# Sheet1.net
KiCad netlist of a schematic drawn in Altium Designer
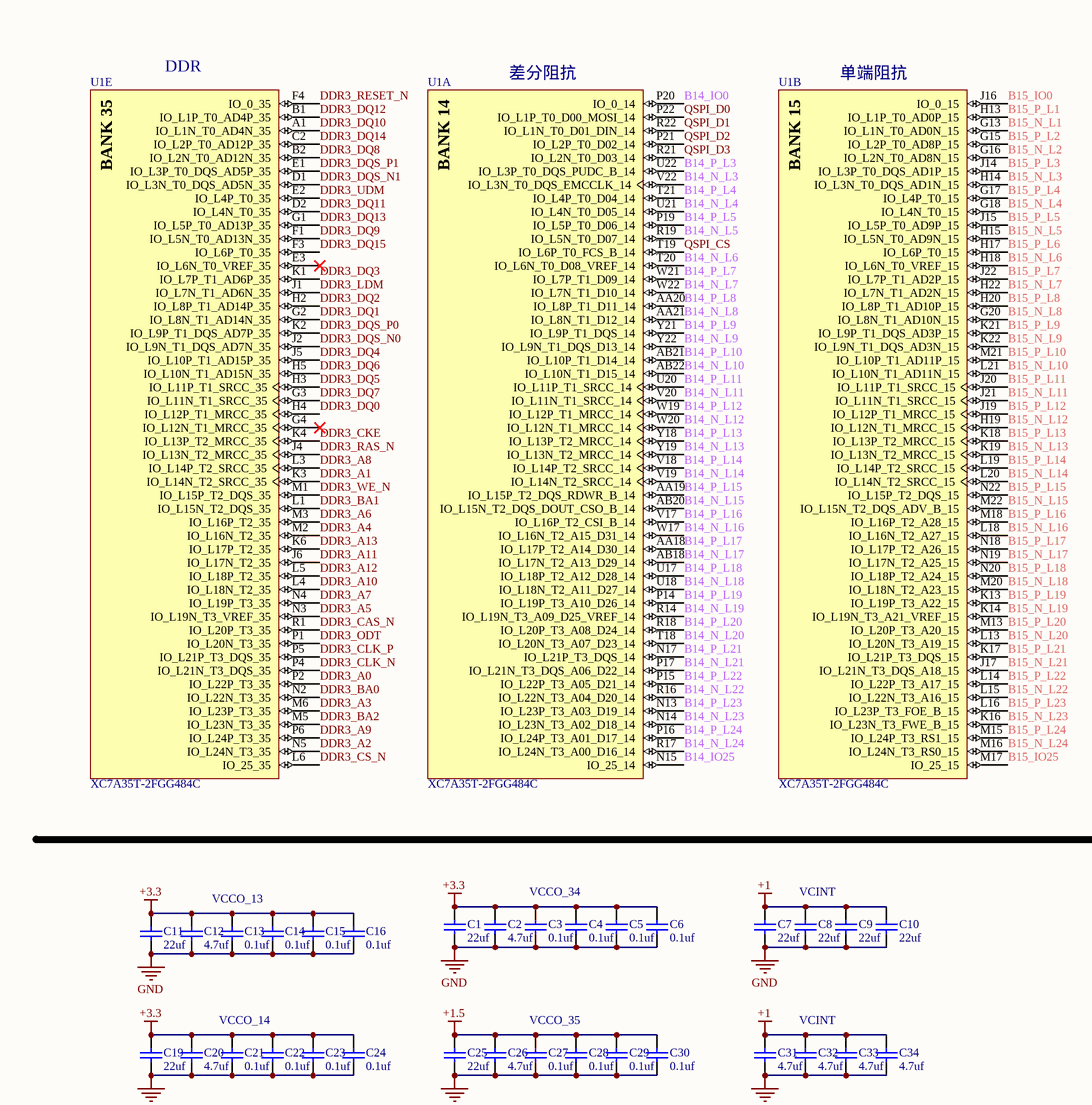
[diagram p0: Sheet1.SchDoc, top left]
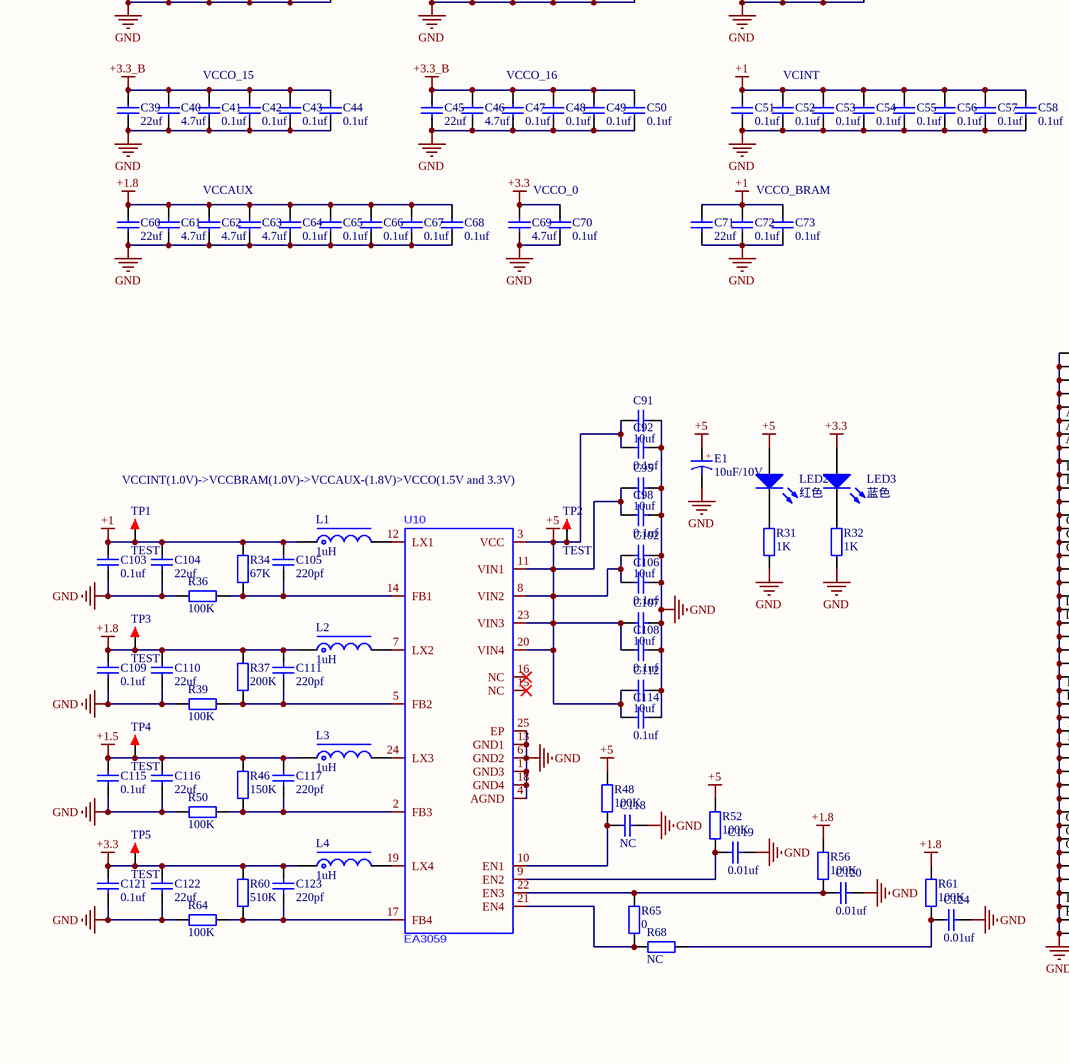
[diagram p1: Sheet1.SchDoc, bottom left]
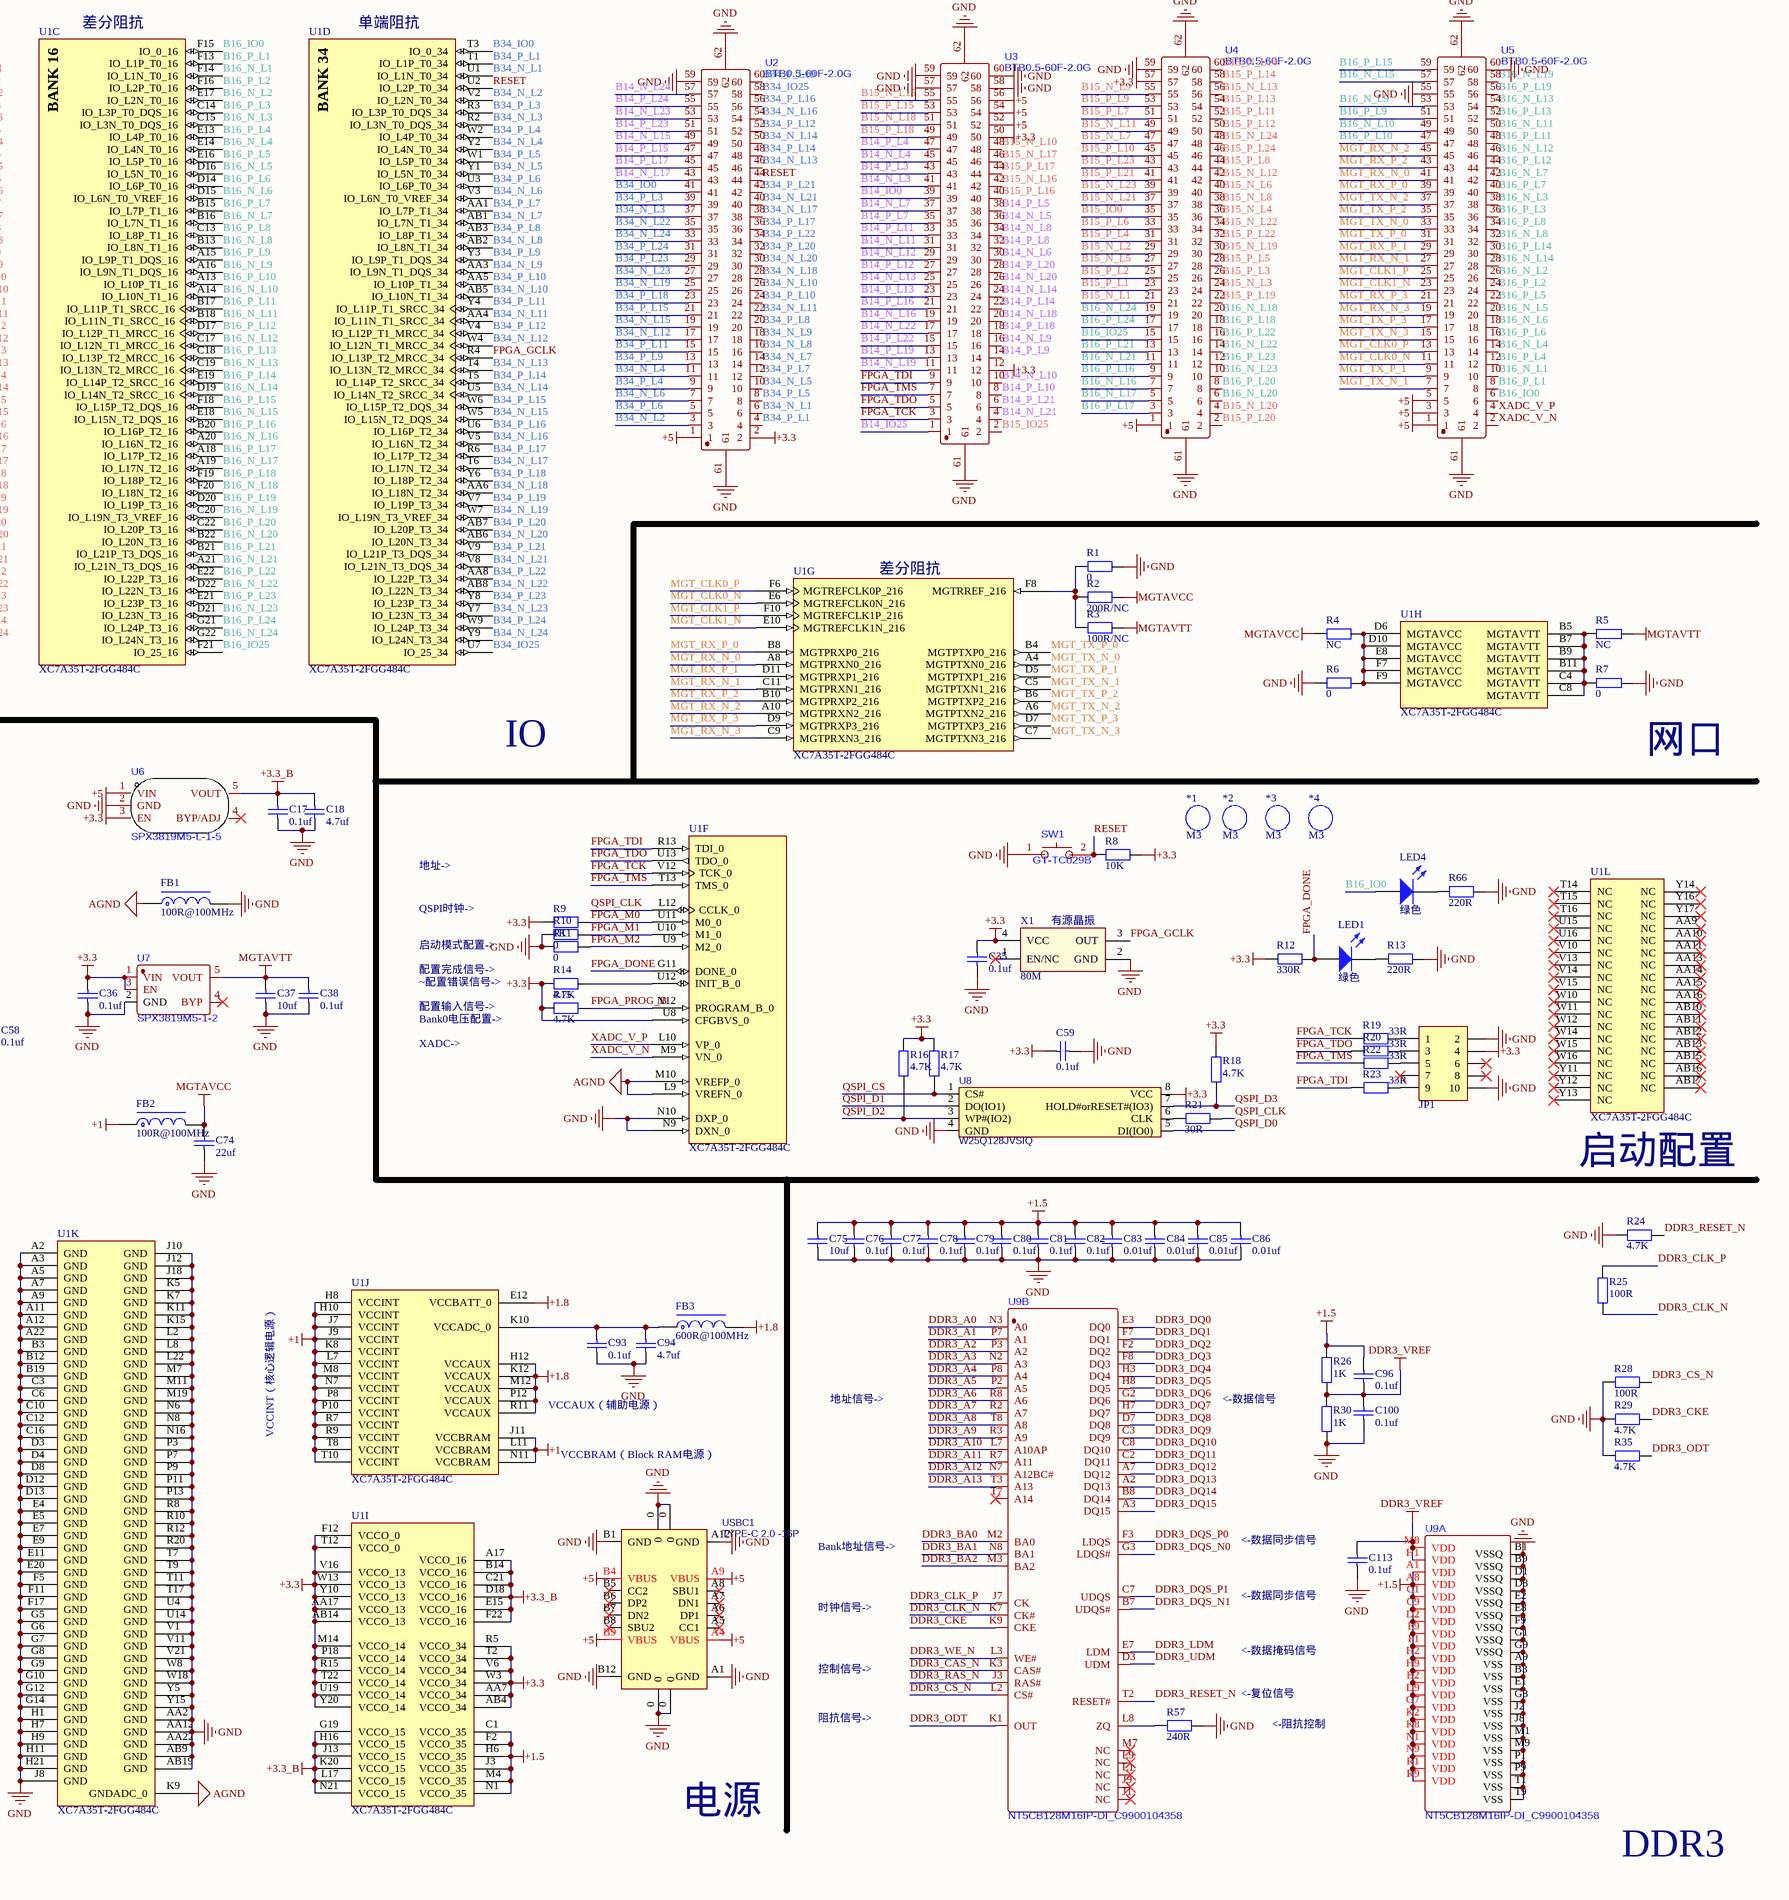
[diagram p2: Sheet1.SchDoc, bottom right]

(export (version "E")
  (design (tool "Eeschema 10.0.6"))
  (components
    (comp (ref "*1")
      (value "M3")
      (footprint "PCB1:M3 125X200")
      (description "铜柱孔")
      (libsource (lib "xc7a35t") (part "M3"))
    )
    (comp (ref "*2")
      (value "M3")
      (footprint "PCB1:M3 125X200")
      (description "铜柱孔")
      (libsource (lib "xc7a35t") (part "M3"))
    )
    (comp (ref "*3")
      (value "M3")
      (footprint "PCB1:M3 125X200")
      (description "铜柱孔")
      (libsource (lib "xc7a35t") (part "M3"))
    )
    (comp (ref "*4")
      (value "M3")
      (footprint "PCB1:M3 125X200")
      (description "铜柱孔")
      (libsource (lib "xc7a35t") (part "M3"))
    )
    (comp (ref "C1")
      (value "22uf")
      (footprint "PCB1:C0603_L")
      (description "贴片电容/MLCC电容")
      (libsource (lib "xc7a35t") (part "C"))
    )
    (comp (ref "C2")
      (value "4.7uf")
      (footprint "PCB1:C0402_L")
      (description "贴片电容/MLCC电容")
      (libsource (lib "xc7a35t") (part "C"))
    )
    (comp (ref "C3")
      (value "0.1uf")
      (footprint "PCB1:C0402_L")
      (description "贴片电容/MLCC电容")
      (libsource (lib "xc7a35t") (part "C"))
    )
    (comp (ref "C4")
      (value "0.1uf")
      (footprint "PCB1:C0402_L")
      (description "贴片电容/MLCC电容")
      (libsource (lib "xc7a35t") (part "C"))
    )
    (comp (ref "C5")
      (value "0.1uf")
      (footprint "PCB1:C0402_L")
      (description "贴片电容/MLCC电容")
      (libsource (lib "xc7a35t") (part "C"))
    )
    (comp (ref "C6")
      (value "0.1uf")
      (footprint "PCB1:C0402_L")
      (description "贴片电容/MLCC电容")
      (libsource (lib "xc7a35t") (part "C"))
    )
    (comp (ref "C7")
      (value "22uf")
      (footprint "PCB1:C0603_L")
      (description "贴片电容/MLCC电容")
      (libsource (lib "xc7a35t") (part "C"))
    )
    (comp (ref "C8")
      (value "22uf")
      (footprint "PCB1:C0603_L")
      (description "贴片电容/MLCC电容")
      (libsource (lib "xc7a35t") (part "C"))
    )
    (comp (ref "C9")
      (value "22uf")
      (footprint "PCB1:C0603_L")
      (description "贴片电容/MLCC电容")
      (libsource (lib "xc7a35t") (part "C"))
    )
    (comp (ref "C10")
      (value "22uf")
      (footprint "PCB1:C0603_L")
      (description "贴片电容/MLCC电容")
      (libsource (lib "xc7a35t") (part "C"))
    )
    (comp (ref "C11")
      (value "22uf")
      (footprint "PCB1:C0603_L")
      (description "贴片电容/MLCC电容")
      (libsource (lib "xc7a35t") (part "C"))
    )
    (comp (ref "C12")
      (value "4.7uf")
      (footprint "PCB1:C0402_L")
      (description "贴片电容/MLCC电容")
      (libsource (lib "xc7a35t") (part "C"))
    )
    (comp (ref "C13")
      (value "0.1uf")
      (footprint "PCB1:C0402_L")
      (description "贴片电容/MLCC电容")
      (libsource (lib "xc7a35t") (part "C"))
    )
    (comp (ref "C14")
      (value "0.1uf")
      (footprint "PCB1:C0402_L")
      (description "贴片电容/MLCC电容")
      (libsource (lib "xc7a35t") (part "C"))
    )
    (comp (ref "C15")
      (value "0.1uf")
      (footprint "PCB1:C0402_L")
      (description "贴片电容/MLCC电容")
      (libsource (lib "xc7a35t") (part "C"))
    )
    (comp (ref "C16")
      (value "0.1uf")
      (footprint "PCB1:C0402_L")
      (description "贴片电容/MLCC电容")
      (libsource (lib "xc7a35t") (part "C"))
    )
    (comp (ref "C17")
      (value "0.1uf")
      (footprint "PCB1:C0402_L")
      (description "贴片电容/MLCC电容")
      (libsource (lib "xc7a35t") (part "C"))
    )
    (comp (ref "C18")
      (value "4.7uf")
      (footprint "PCB1:C0402_L")
      (description "贴片电容/MLCC电容")
      (libsource (lib "xc7a35t") (part "C"))
    )
    (comp (ref "C19")
      (value "22uf")
      (footprint "PCB1:C0603_L")
      (description "贴片电容/MLCC电容")
      (libsource (lib "xc7a35t") (part "C"))
    )
    (comp (ref "C20")
      (value "4.7uf")
      (footprint "PCB1:C0402_L")
      (description "贴片电容/MLCC电容")
      (libsource (lib "xc7a35t") (part "C"))
    )
    (comp (ref "C21")
      (value "0.1uf")
      (footprint "PCB1:C0402_L")
      (description "贴片电容/MLCC电容")
      (libsource (lib "xc7a35t") (part "C"))
    )
    (comp (ref "C22")
      (value "0.1uf")
      (footprint "PCB1:C0402_L")
      (description "贴片电容/MLCC电容")
      (libsource (lib "xc7a35t") (part "C"))
    )
    (comp (ref "C23")
      (value "0.1uf")
      (footprint "PCB1:C0402_L")
      (description "贴片电容/MLCC电容")
      (libsource (lib "xc7a35t") (part "C"))
    )
    (comp (ref "C24")
      (value "0.1uf")
      (footprint "PCB1:C0402_L")
      (description "贴片电容/MLCC电容")
      (libsource (lib "xc7a35t") (part "C"))
    )
    (comp (ref "C25")
      (value "22uf")
      (footprint "PCB1:C0603_L")
      (description "贴片电容/MLCC电容")
      (libsource (lib "xc7a35t") (part "C"))
    )
    (comp (ref "C26")
      (value "4.7uf")
      (footprint "PCB1:C0402_L")
      (description "贴片电容/MLCC电容")
      (libsource (lib "xc7a35t") (part "C"))
    )
    (comp (ref "C27")
      (value "0.1uf")
      (footprint "PCB1:C0402_L")
      (description "贴片电容/MLCC电容")
      (libsource (lib "xc7a35t") (part "C"))
    )
    (comp (ref "C28")
      (value "0.1uf")
      (footprint "PCB1:C0402_L")
      (description "贴片电容/MLCC电容")
      (libsource (lib "xc7a35t") (part "C"))
    )
    (comp (ref "C29")
      (value "0.1uf")
      (footprint "PCB1:C0402_L")
      (description "贴片电容/MLCC电容")
      (libsource (lib "xc7a35t") (part "C"))
    )
    (comp (ref "C30")
      (value "0.1uf")
      (footprint "PCB1:C0402_L")
      (description "贴片电容/MLCC电容")
      (libsource (lib "xc7a35t") (part "C"))
    )
    (comp (ref "C31")
      (value "4.7uf")
      (footprint "PCB1:C0402_L")
      (description "贴片电容/MLCC电容")
      (libsource (lib "xc7a35t") (part "C"))
    )
    (comp (ref "C32")
      (value "4.7uf")
      (footprint "PCB1:C0402_L")
      (description "贴片电容/MLCC电容")
      (libsource (lib "xc7a35t") (part "C"))
    )
    (comp (ref "C33")
      (value "4.7uf")
      (footprint "PCB1:C0402_L")
      (description "贴片电容/MLCC电容")
      (libsource (lib "xc7a35t") (part "C"))
    )
    (comp (ref "C34")
      (value "4.7uf")
      (footprint "PCB1:C0402_L")
      (description "贴片电容/MLCC电容")
      (libsource (lib "xc7a35t") (part "C"))
    )
    (comp (ref "C35")
      (value "0.1uf")
      (footprint "PCB1:C0402_L")
      (description "贴片电容/MLCC电容")
      (libsource (lib "xc7a35t") (part "C"))
    )
    (comp (ref "C36")
      (value "0.1uf")
      (footprint "PCB1:C0402_L")
      (description "贴片电容/MLCC电容")
      (libsource (lib "xc7a35t") (part "C"))
    )
    (comp (ref "C37")
      (value "10uf")
      (footprint "PCB1:C0603_L")
      (description "贴片电容/MLCC电容")
      (libsource (lib "xc7a35t") (part "C"))
    )
    (comp (ref "C38")
      (value "0.1uf")
      (footprint "PCB1:C0402_L")
      (description "贴片电容/MLCC电容")
      (libsource (lib "xc7a35t") (part "C"))
    )
    (comp (ref "C39")
      (value "22uf")
      (footprint "PCB1:C0603_L")
      (description "贴片电容/MLCC电容")
      (libsource (lib "xc7a35t") (part "C"))
    )
    (comp (ref "C40")
      (value "4.7uf")
      (footprint "PCB1:C0402_L")
      (description "贴片电容/MLCC电容")
      (libsource (lib "xc7a35t") (part "C"))
    )
    (comp (ref "C41")
      (value "0.1uf")
      (footprint "PCB1:C0402_L")
      (description "贴片电容/MLCC电容")
      (libsource (lib "xc7a35t") (part "C"))
    )
    (comp (ref "C42")
      (value "0.1uf")
      (footprint "PCB1:C0402_L")
      (description "贴片电容/MLCC电容")
      (libsource (lib "xc7a35t") (part "C"))
    )
    (comp (ref "C43")
      (value "0.1uf")
      (footprint "PCB1:C0402_L")
      (description "贴片电容/MLCC电容")
      (libsource (lib "xc7a35t") (part "C"))
    )
    (comp (ref "C44")
      (value "0.1uf")
      (footprint "PCB1:C0402_L")
      (description "贴片电容/MLCC电容")
      (libsource (lib "xc7a35t") (part "C"))
    )
    (comp (ref "C45")
      (value "22uf")
      (footprint "PCB1:C0603_L")
      (description "贴片电容/MLCC电容")
      (libsource (lib "xc7a35t") (part "C"))
    )
    (comp (ref "C46")
      (value "4.7uf")
      (footprint "PCB1:C0402_L")
      (description "贴片电容/MLCC电容")
      (libsource (lib "xc7a35t") (part "C"))
    )
    (comp (ref "C47")
      (value "0.1uf")
      (footprint "PCB1:C0402_L")
      (description "贴片电容/MLCC电容")
      (libsource (lib "xc7a35t") (part "C"))
    )
    (comp (ref "C48")
      (value "0.1uf")
      (footprint "PCB1:C0402_L")
      (description "贴片电容/MLCC电容")
      (libsource (lib "xc7a35t") (part "C"))
    )
    (comp (ref "C49")
      (value "0.1uf")
      (footprint "PCB1:C0402_L")
      (description "贴片电容/MLCC电容")
      (libsource (lib "xc7a35t") (part "C"))
    )
    (comp (ref "C50")
      (value "0.1uf")
      (footprint "PCB1:C0402_L")
      (description "贴片电容/MLCC电容")
      (libsource (lib "xc7a35t") (part "C"))
    )
    (comp (ref "C51")
      (value "0.1uf")
      (footprint "PCB1:C0402_L")
      (description "贴片电容/MLCC电容")
      (libsource (lib "xc7a35t") (part "C"))
    )
    (comp (ref "C52")
      (value "0.1uf")
      (footprint "PCB1:C0402_L")
      (description "贴片电容/MLCC电容")
      (libsource (lib "xc7a35t") (part "C"))
    )
    (comp (ref "C53")
      (value "0.1uf")
      (footprint "PCB1:C0402_L")
      (description "贴片电容/MLCC电容")
      (libsource (lib "xc7a35t") (part "C"))
    )
    (comp (ref "C54")
      (value "0.1uf")
      (footprint "PCB1:C0402_L")
      (description "贴片电容/MLCC电容")
      (libsource (lib "xc7a35t") (part "C"))
    )
    (comp (ref "C55")
      (value "0.1uf")
      (footprint "PCB1:C0402_L")
      (description "贴片电容/MLCC电容")
      (libsource (lib "xc7a35t") (part "C"))
    )
    (comp (ref "C56")
      (value "0.1uf")
      (footprint "PCB1:C0402_L")
      (description "贴片电容/MLCC电容")
      (libsource (lib "xc7a35t") (part "C"))
    )
    (comp (ref "C57")
      (value "0.1uf")
      (footprint "PCB1:C0402_L")
      (description "贴片电容/MLCC电容")
      (libsource (lib "xc7a35t") (part "C"))
    )
    (comp (ref "C58")
      (value "0.1uf")
      (footprint "PCB1:C0402_L")
      (description "贴片电容/MLCC电容")
      (libsource (lib "xc7a35t") (part "C"))
    )
    (comp (ref "C59")
      (value "0.1uf")
      (footprint "PCB1:C0402_L")
      (description "贴片电容/MLCC电容")
      (libsource (lib "xc7a35t") (part "C"))
    )
    (comp (ref "C60")
      (value "22uf")
      (footprint "PCB1:C0603_L")
      (description "贴片电容/MLCC电容")
      (libsource (lib "xc7a35t") (part "C"))
    )
    (comp (ref "C61")
      (value "4.7uf")
      (footprint "PCB1:C0402_L")
      (description "贴片电容/MLCC电容")
      (libsource (lib "xc7a35t") (part "C"))
    )
    (comp (ref "C62")
      (value "4.7uf")
      (footprint "PCB1:C0402_L")
      (description "贴片电容/MLCC电容")
      (libsource (lib "xc7a35t") (part "C"))
    )
    (comp (ref "C63")
      (value "4.7uf")
      (footprint "PCB1:C0402_L")
      (description "贴片电容/MLCC电容")
      (libsource (lib "xc7a35t") (part "C"))
    )
    (comp (ref "C64")
      (value "0.1uf")
      (footprint "PCB1:C0402_L")
      (description "贴片电容/MLCC电容")
      (libsource (lib "xc7a35t") (part "C"))
    )
    (comp (ref "C65")
      (value "0.1uf")
      (footprint "PCB1:C0402_L")
      (description "贴片电容/MLCC电容")
      (libsource (lib "xc7a35t") (part "C"))
    )
    (comp (ref "C66")
      (value "0.1uf")
      (footprint "PCB1:C0402_L")
      (description "贴片电容/MLCC电容")
      (libsource (lib "xc7a35t") (part "C"))
    )
    (comp (ref "C67")
      (value "0.1uf")
      (footprint "PCB1:C0402_L")
      (description "贴片电容/MLCC电容")
      (libsource (lib "xc7a35t") (part "C"))
    )
    (comp (ref "C68")
      (value "0.1uf")
      (footprint "PCB1:C0402_L")
      (description "贴片电容/MLCC电容")
      (libsource (lib "xc7a35t") (part "C"))
    )
    (comp (ref "C69")
      (value "4.7uf")
      (footprint "PCB1:C0402_L")
      (description "贴片电容/MLCC电容")
      (libsource (lib "xc7a35t") (part "C"))
    )
    (comp (ref "C70")
      (value "0.1uf")
      (footprint "PCB1:C0402_L")
      (description "贴片电容/MLCC电容")
      (libsource (lib "xc7a35t") (part "C"))
    )
    (comp (ref "C71")
      (value "22uf")
      (footprint "PCB1:C0603_L")
      (description "贴片电容/MLCC电容")
      (libsource (lib "xc7a35t") (part "C"))
    )
    (comp (ref "C72")
      (value "0.1uf")
      (footprint "PCB1:C0402_L")
      (description "贴片电容/MLCC电容")
      (libsource (lib "xc7a35t") (part "C"))
    )
    (comp (ref "C73")
      (value "0.1uf")
      (footprint "PCB1:C0402_L")
      (description "贴片电容/MLCC电容")
      (libsource (lib "xc7a35t") (part "C"))
    )
    (comp (ref "C74")
      (value "22uf")
      (footprint "PCB1:C0603_L")
      (description "贴片电容/MLCC电容")
      (libsource (lib "xc7a35t") (part "C"))
    )
    (comp (ref "C75")
      (value "10uf")
      (footprint "PCB1:C0603_L")
      (description "贴片电容/MLCC电容")
      (libsource (lib "xc7a35t") (part "C"))
    )
    (comp (ref "C76")
      (value "0.1uf")
      (footprint "PCB1:C0402_L")
      (description "贴片电容/MLCC电容")
      (libsource (lib "xc7a35t") (part "C"))
    )
    (comp (ref "C77")
      (value "0.1uf")
      (footprint "PCB1:C0402_L")
      (description "贴片电容/MLCC电容")
      (libsource (lib "xc7a35t") (part "C"))
    )
    (comp (ref "C78")
      (value "0.1uf")
      (footprint "PCB1:C0402_L")
      (description "贴片电容/MLCC电容")
      (libsource (lib "xc7a35t") (part "C"))
    )
    (comp (ref "C79")
      (value "0.1uf")
      (footprint "PCB1:C0402_L")
      (description "贴片电容/MLCC电容")
      (libsource (lib "xc7a35t") (part "C"))
    )
    (comp (ref "C80")
      (value "0.1uf")
      (footprint "PCB1:C0402_L")
      (description "贴片电容/MLCC电容")
      (libsource (lib "xc7a35t") (part "C"))
    )
    (comp (ref "C81")
      (value "0.1uf")
      (footprint "PCB1:C0402_L")
      (description "贴片电容/MLCC电容")
      (libsource (lib "xc7a35t") (part "C"))
    )
    (comp (ref "C82")
      (value "0.1uf")
      (footprint "PCB1:C0402_L")
      (description "贴片电容/MLCC电容")
      (libsource (lib "xc7a35t") (part "C"))
    )
    (comp (ref "C83")
      (value "0.01uf")
      (footprint "PCB1:C0402_L")
      (description "贴片电容/MLCC电容")
      (libsource (lib "xc7a35t") (part "C"))
    )
    (comp (ref "C84")
      (value "0.01uf")
      (footprint "PCB1:C0402_L")
      (description "贴片电容/MLCC电容")
      (libsource (lib "xc7a35t") (part "C"))
    )
    (comp (ref "C85")
      (value "0.01uf")
      (footprint "PCB1:C0402_L")
      (description "贴片电容/MLCC电容")
      (libsource (lib "xc7a35t") (part "C"))
    )
    (comp (ref "C86")
      (value "0.01uf")
      (footprint "PCB1:C0402_L")
      (description "贴片电容/MLCC电容")
      (libsource (lib "xc7a35t") (part "C"))
    )
    (comp (ref "C91")
      (value "10uf")
      (footprint "PCB1:C0603_L")
      (description "贴片电容/MLCC电容")
      (libsource (lib "xc7a35t") (part "C"))
    )
    (comp (ref "C92")
      (value "0.1uf")
      (footprint "PCB1:C0402_L")
      (description "贴片电容/MLCC电容")
      (libsource (lib "xc7a35t") (part "C"))
    )
    (comp (ref "C93")
      (value "0.1uf")
      (footprint "PCB1:C0402_L")
      (description "贴片电容/MLCC电容")
      (libsource (lib "xc7a35t") (part "C"))
    )
    (comp (ref "C94")
      (value "4.7uf")
      (footprint "PCB1:C0402_L")
      (description "贴片电容/MLCC电容")
      (libsource (lib "xc7a35t") (part "C"))
    )
    (comp (ref "C95")
      (value "10uf")
      (footprint "PCB1:C0603_L")
      (description "贴片电容/MLCC电容")
      (libsource (lib "xc7a35t") (part "C"))
    )
    (comp (ref "C96")
      (value "0.1uf")
      (footprint "PCB1:C0402_L")
      (description "贴片电容/MLCC电容")
      (libsource (lib "xc7a35t") (part "C"))
    )
    (comp (ref "C98")
      (value "0.1uf")
      (footprint "PCB1:C0402_L")
      (description "贴片电容/MLCC电容")
      (libsource (lib "xc7a35t") (part "C"))
    )
    (comp (ref "C100")
      (value "0.1uf")
      (footprint "PCB1:C0402_L")
      (description "贴片电容/MLCC电容")
      (libsource (lib "xc7a35t") (part "C"))
    )
    (comp (ref "C102")
      (value "10uf")
      (footprint "PCB1:C0603_L")
      (description "贴片电容/MLCC电容")
      (libsource (lib "xc7a35t") (part "C"))
    )
    (comp (ref "C103")
      (value "0.1uf")
      (footprint "PCB1:C0402_L")
      (description "贴片电容/MLCC电容")
      (libsource (lib "xc7a35t") (part "C"))
    )
    (comp (ref "C104")
      (value "22uf")
      (footprint "PCB1:C0603_L")
      (description "贴片电容/MLCC电容")
      (libsource (lib "xc7a35t") (part "C"))
    )
    (comp (ref "C105")
      (value "220pf")
      (footprint "PCB1:C0402_L")
      (description "贴片电容/MLCC电容")
      (libsource (lib "xc7a35t") (part "C"))
    )
    (comp (ref "C106")
      (value "0.1uf")
      (footprint "PCB1:C0402_L")
      (description "贴片电容/MLCC电容")
      (libsource (lib "xc7a35t") (part "C"))
    )
    (comp (ref "C107")
      (value "10uf")
      (footprint "PCB1:C0603_L")
      (description "贴片电容/MLCC电容")
      (libsource (lib "xc7a35t") (part "C"))
    )
    (comp (ref "C108")
      (value "0.1uf")
      (footprint "PCB1:C0402_L")
      (description "贴片电容/MLCC电容")
      (libsource (lib "xc7a35t") (part "C"))
    )
    (comp (ref "C109")
      (value "0.1uf")
      (footprint "PCB1:C0402_L")
      (description "贴片电容/MLCC电容")
      (libsource (lib "xc7a35t") (part "C"))
    )
    (comp (ref "C110")
      (value "22uf")
      (footprint "PCB1:C0603_L")
      (description "贴片电容/MLCC电容")
      (libsource (lib "xc7a35t") (part "C"))
    )
    (comp (ref "C111")
      (value "220pf")
      (footprint "PCB1:C0402_L")
      (description "贴片电容/MLCC电容")
      (libsource (lib "xc7a35t") (part "C"))
    )
    (comp (ref "C112")
      (value "10uf")
      (footprint "PCB1:C0603_L")
      (description "贴片电容/MLCC电容")
      (libsource (lib "xc7a35t") (part "C"))
    )
    (comp (ref "C113")
      (value "0.1uf")
      (footprint "PCB1:C0402_L")
      (description "贴片电容/MLCC电容")
      (libsource (lib "xc7a35t") (part "C"))
    )
    (comp (ref "C114")
      (value "0.1uf")
      (footprint "PCB1:C0402_L")
      (description "贴片电容/MLCC电容")
      (libsource (lib "xc7a35t") (part "C"))
    )
    (comp (ref "C115")
      (value "0.1uf")
      (footprint "PCB1:C0402_L")
      (description "贴片电容/MLCC电容")
      (libsource (lib "xc7a35t") (part "C"))
    )
    (comp (ref "C116")
      (value "22uf")
      (footprint "PCB1:C0603_L")
      (description "贴片电容/MLCC电容")
      (libsource (lib "xc7a35t") (part "C"))
    )
    (comp (ref "C117")
      (value "220pf")
      (footprint "PCB1:C0402_L")
      (description "贴片电容/MLCC电容")
      (libsource (lib "xc7a35t") (part "C"))
    )
    (comp (ref "C118")
      (value "NC")
      (footprint "PCB1:C0402_L")
      (description "贴片电容/MLCC电容")
      (libsource (lib "xc7a35t") (part "C"))
    )
    (comp (ref "C119")
      (value "0.01uf")
      (footprint "PCB1:C0402_L")
      (description "贴片电容/MLCC电容")
      (libsource (lib "xc7a35t") (part "C"))
    )
    (comp (ref "C120")
      (value "0.01uf")
      (footprint "PCB1:C0402_L")
      (description "贴片电容/MLCC电容")
      (libsource (lib "xc7a35t") (part "C"))
    )
    (comp (ref "C121")
      (value "0.1uf")
      (footprint "PCB1:C0402_L")
      (description "贴片电容/MLCC电容")
      (libsource (lib "xc7a35t") (part "C"))
    )
    (comp (ref "C122")
      (value "22uf")
      (footprint "PCB1:C0603_L")
      (description "贴片电容/MLCC电容")
      (libsource (lib "xc7a35t") (part "C"))
    )
    (comp (ref "C123")
      (value "220pf")
      (footprint "PCB1:C0402_L")
      (description "贴片电容/MLCC电容")
      (libsource (lib "xc7a35t") (part "C"))
    )
    (comp (ref "C124")
      (value "0.01uf")
      (footprint "PCB1:C0402_L")
      (description "贴片电容/MLCC电容")
      (libsource (lib "xc7a35t") (part "C"))
    )
    (comp (ref "E1")
      (value "10uF/10V")
      (footprint "PCB1:CE D(6.3*7.7)")
      (description "贴片电解电容")
      (libsource (lib "xc7a35t") (part "CE_SMD"))
    )
    (comp (ref "FB1")
      (value "100R@100MHz")
      (footprint "PCB1:FB0603")
      (description "贴片磁珠")
      (libsource (lib "xc7a35t") (part "FB"))
    )
    (comp (ref "FB2")
      (value "100R@100MHz")
      (footprint "PCB1:FB0603")
      (description "贴片磁珠")
      (libsource (lib "xc7a35t") (part "FB"))
    )
    (comp (ref "FB3")
      (value "600R@100MHz")
      (footprint "PCB1:FB0603")
      (description "贴片磁珠")
      (libsource (lib "xc7a35t") (part "FB"))
    )
    (comp (ref "JP1")
      (value "Header 5X2")
      (footprint "PCB1:PHD2.0-LI-2x5P")
      (description "5*2P接插件")
      (libsource (lib "xc7a35t") (part "Header 5X2"))
    )
    (comp (ref "L1")
      (value "1uH")
      (footprint "PCB1:CD43")
      (description "CD系列贴片线绕功率电感")
      (libsource (lib "xc7a35t") (part "L-SMD"))
    )
    (comp (ref "L2")
      (value "1uH")
      (footprint "PCB1:CD43")
      (description "CD系列贴片线绕功率电感")
      (libsource (lib "xc7a35t") (part "L-SMD"))
    )
    (comp (ref "L3")
      (value "1uH")
      (footprint "PCB1:CD43")
      (description "CD系列贴片线绕功率电感")
      (libsource (lib "xc7a35t") (part "L-SMD"))
    )
    (comp (ref "L4")
      (value "1uH")
      (footprint "PCB1:CD43")
      (description "CD系列贴片线绕功率电感")
      (libsource (lib "xc7a35t") (part "L-SMD"))
    )
    (comp (ref "LED1")
      (value "绿色")
      (footprint "PCB1:LED0805_G")
      (description "贴片LED")
      (libsource (lib "xc7a35t") (part "LED"))
    )
    (comp (ref "LED2")
      (value "红色")
      (footprint "PCB1:LED0805_G")
      (description "贴片LED")
      (libsource (lib "xc7a35t") (part "LED"))
    )
    (comp (ref "LED3")
      (value "蓝色")
      (footprint "PCB1:LED0805_G")
      (description "贴片LED")
      (libsource (lib "xc7a35t") (part "LED"))
    )
    (comp (ref "LED4")
      (value "绿色")
      (footprint "PCB1:LED0805_G")
      (description "贴片LED")
      (libsource (lib "xc7a35t") (part "LED"))
    )
    (comp (ref "R1")
      (value "0")
      (footprint "PCB1:R0402_L")
      (description "贴片电阻")
      (libsource (lib "xc7a35t") (part "R"))
    )
    (comp (ref "R2")
      (value "200R/NC")
      (footprint "PCB1:R0402_L")
      (description "贴片电阻")
      (libsource (lib "xc7a35t") (part "R"))
    )
    (comp (ref "R3")
      (value "100R/NC")
      (footprint "PCB1:R0402_L")
      (description "贴片电阻")
      (libsource (lib "xc7a35t") (part "R"))
    )
    (comp (ref "R4")
      (value "NC")
      (footprint "PCB1:R0603_L")
      (description "贴片电阻")
      (libsource (lib "xc7a35t") (part "R"))
    )
    (comp (ref "R5")
      (value "NC")
      (footprint "PCB1:R0603_L")
      (description "贴片电阻")
      (libsource (lib "xc7a35t") (part "R"))
    )
    (comp (ref "R6")
      (value "0")
      (footprint "PCB1:R0603_L")
      (description "贴片电阻")
      (libsource (lib "xc7a35t") (part "R"))
    )
    (comp (ref "R7")
      (value "0")
      (footprint "PCB1:R0603_L")
      (description "贴片电阻")
      (libsource (lib "xc7a35t") (part "R"))
    )
    (comp (ref "R8")
      (value "10K")
      (footprint "PCB1:R0402_L")
      (description "贴片电阻")
      (libsource (lib "xc7a35t") (part "R"))
    )
    (comp (ref "R9")
      (value "1K")
      (footprint "PCB1:R0402_L")
      (description "贴片电阻")
      (libsource (lib "xc7a35t") (part "R"))
    )
    (comp (ref "R10")
      (value "0")
      (footprint "PCB1:R0402_L")
      (description "贴片电阻")
      (libsource (lib "xc7a35t") (part "R"))
    )
    (comp (ref "R11")
      (value "0")
      (footprint "PCB1:R0402_L")
      (description "贴片电阻")
      (libsource (lib "xc7a35t") (part "R"))
    )
    (comp (ref "R12")
      (value "330R")
      (footprint "PCB1:R0402_L")
      (description "贴片电阻")
      (libsource (lib "xc7a35t") (part "R"))
    )
    (comp (ref "R13")
      (value "220R")
      (footprint "PCB1:R0402_L")
      (description "贴片电阻")
      (libsource (lib "xc7a35t") (part "R"))
    )
    (comp (ref "R14")
      (value "4.7K")
      (footprint "PCB1:R0402_L")
      (description "贴片电阻")
      (libsource (lib "xc7a35t") (part "R"))
    )
    (comp (ref "R15")
      (value "4.7K")
      (footprint "PCB1:R0402_L")
      (description "贴片电阻")
      (libsource (lib "xc7a35t") (part "R"))
    )
    (comp (ref "R16")
      (value "4.7K")
      (footprint "PCB1:R0402_L")
      (description "贴片电阻")
      (libsource (lib "xc7a35t") (part "R"))
    )
    (comp (ref "R17")
      (value "4.7K")
      (footprint "PCB1:R0402_L")
      (description "贴片电阻")
      (libsource (lib "xc7a35t") (part "R"))
    )
    (comp (ref "R18")
      (value "4.7K")
      (footprint "PCB1:R0402_L")
      (description "贴片电阻")
      (libsource (lib "xc7a35t") (part "R"))
    )
    (comp (ref "R19")
      (value "33R")
      (footprint "PCB1:R0402_L")
      (description "贴片电阻")
      (libsource (lib "xc7a35t") (part "R"))
    )
    (comp (ref "R20")
      (value "33R")
      (footprint "PCB1:R0402_L")
      (description "贴片电阻")
      (libsource (lib "xc7a35t") (part "R"))
    )
    (comp (ref "R21")
      (value "30R")
      (footprint "PCB1:R0402_L")
      (description "贴片电阻")
      (libsource (lib "xc7a35t") (part "R"))
    )
    (comp (ref "R22")
      (value "33R")
      (footprint "PCB1:R0402_L")
      (description "贴片电阻")
      (libsource (lib "xc7a35t") (part "R"))
    )
    (comp (ref "R23")
      (value "33R")
      (footprint "PCB1:R0402_L")
      (description "贴片电阻")
      (libsource (lib "xc7a35t") (part "R"))
    )
    (comp (ref "R24")
      (value "4.7K")
      (footprint "PCB1:R0402_L")
      (description "贴片电阻")
      (libsource (lib "xc7a35t") (part "R"))
    )
    (comp (ref "R25")
      (value "100R")
      (footprint "PCB1:R0402_L")
      (description "贴片电阻")
      (libsource (lib "xc7a35t") (part "R"))
    )
    (comp (ref "R26")
      (value "1K")
      (footprint "PCB1:R0402_L")
      (description "贴片电阻")
      (libsource (lib "xc7a35t") (part "R"))
    )
    (comp (ref "R28")
      (value "100R")
      (footprint "PCB1:R0402_L")
      (description "贴片电阻")
      (libsource (lib "xc7a35t") (part "R"))
    )
    (comp (ref "R29")
      (value "4.7K")
      (footprint "PCB1:R0402_L")
      (description "贴片电阻")
      (libsource (lib "xc7a35t") (part "R"))
    )
    (comp (ref "R30")
      (value "1K")
      (footprint "PCB1:R0402_L")
      (description "贴片电阻")
      (libsource (lib "xc7a35t") (part "R"))
    )
    (comp (ref "R31")
      (value "1K")
      (footprint "PCB1:R0402_L")
      (description "贴片电阻")
      (libsource (lib "xc7a35t") (part "R"))
    )
    (comp (ref "R32")
      (value "1K")
      (footprint "PCB1:R0402_L")
      (description "贴片电阻")
      (libsource (lib "xc7a35t") (part "R"))
    )
    (comp (ref "R34")
      (value "67K")
      (footprint "PCB1:R0402_L")
      (description "贴片电阻")
      (libsource (lib "xc7a35t") (part "R"))
    )
    (comp (ref "R35")
      (value "4.7K")
      (footprint "PCB1:R0402_L")
      (description "贴片电阻")
      (libsource (lib "xc7a35t") (part "R"))
    )
    (comp (ref "R36")
      (value "100K")
      (footprint "PCB1:R0402_L")
      (description "贴片电阻")
      (libsource (lib "xc7a35t") (part "R"))
    )
    (comp (ref "R37")
      (value "200K")
      (footprint "PCB1:R0402_L")
      (description "贴片电阻")
      (libsource (lib "xc7a35t") (part "R"))
    )
    (comp (ref "R39")
      (value "100K")
      (footprint "PCB1:R0402_L")
      (description "贴片电阻")
      (libsource (lib "xc7a35t") (part "R"))
    )
    (comp (ref "R46")
      (value "150K")
      (footprint "PCB1:R0402_L")
      (description "贴片电阻")
      (libsource (lib "xc7a35t") (part "R"))
    )
    (comp (ref "R48")
      (value "100K")
      (footprint "PCB1:R0402_L")
      (description "贴片电阻")
      (libsource (lib "xc7a35t") (part "R"))
    )
    (comp (ref "R50")
      (value "100K")
      (footprint "PCB1:R0402_L")
      (description "贴片电阻")
      (libsource (lib "xc7a35t") (part "R"))
    )
    (comp (ref "R52")
      (value "100K")
      (footprint "PCB1:R0402_L")
      (description "贴片电阻")
      (libsource (lib "xc7a35t") (part "R"))
    )
    (comp (ref "R56")
      (value "100K")
      (footprint "PCB1:R0402_L")
      (description "贴片电阻")
      (libsource (lib "xc7a35t") (part "R"))
    )
    (comp (ref "R57")
      (value "240R")
      (footprint "PCB1:R0402_L")
      (description "贴片电阻")
      (libsource (lib "xc7a35t") (part "R"))
    )
    (comp (ref "R60")
      (value "510K")
      (footprint "PCB1:R0402_L")
      (description "贴片电阻")
      (libsource (lib "xc7a35t") (part "R"))
    )
    (comp (ref "R61")
      (value "100K")
      (footprint "PCB1:R0402_L")
      (description "贴片电阻")
      (libsource (lib "xc7a35t") (part "R"))
    )
    (comp (ref "R64")
      (value "100K")
      (footprint "PCB1:R0402_L")
      (description "贴片电阻")
      (libsource (lib "xc7a35t") (part "R"))
    )
    (comp (ref "R65")
      (value "0")
      (footprint "PCB1:R0402_L")
      (description "贴片电阻")
      (libsource (lib "xc7a35t") (part "R"))
    )
    (comp (ref "R66")
      (value "220R")
      (footprint "PCB1:R0402_L")
      (description "贴片电阻")
      (libsource (lib "xc7a35t") (part "R"))
    )
    (comp (ref "R68")
      (value "NC")
      (footprint "PCB1:R0402_L")
      (description "贴片电阻")
      (libsource (lib "xc7a35t") (part "R"))
    )
    (comp (ref "SW1")
      (value "GT-TC029B")
      (footprint "PCB1:SW-SMD_L3.9-W2.9-P4.15-LS5.0")
      (libsource (lib "xc7a35t") (part "GT-TC029B-H020-L1N"))
    )
    (comp (ref "TP1")
      (value "TEST")
      (footprint "PCB1:TEST 1.6")
      (description "测试点")
      (libsource (lib "xc7a35t") (part "TEST"))
    )
    (comp (ref "TP2")
      (value "TEST")
      (footprint "PCB1:TEST 1.6")
      (description "测试点")
      (libsource (lib "xc7a35t") (part "TEST"))
    )
    (comp (ref "TP3")
      (value "TEST")
      (footprint "PCB1:TEST 1.6")
      (description "测试点")
      (libsource (lib "xc7a35t") (part "TEST"))
    )
    (comp (ref "TP4")
      (value "TEST")
      (footprint "PCB1:TEST 1.6")
      (description "测试点")
      (libsource (lib "xc7a35t") (part "TEST"))
    )
    (comp (ref "TP5")
      (value "TEST")
      (footprint "PCB1:TEST 1.6")
      (description "测试点")
      (libsource (lib "xc7a35t") (part "TEST"))
    )
    (comp (ref "U1")
      (value "XC7A35T-2FGG484C")
      (footprint "PCB1:FGG484")
      (description "Artix-7 FPGA, 250 User I/Os, 4 GTP, 484-Ball BGA, Speed Grade 2, Commercial Grade, Pb-Free")
      (libsource (lib "xc7a35t") (part "XC7A35T-2FGG484C"))
    )
    (comp (ref "U2")
      (value "BTB0.5-60F-2.0G")
      (footprint "PCB1:CONN-SMD_60P-P0.50_BTB0.5-60F-2.0G")
      (libsource (lib "xc7a35t") (part "BTB0.5-60F-2.0G"))
    )
    (comp (ref "U3")
      (value "BTB0.5-60F-2.0G")
      (footprint "PCB1:CONN-SMD_60P-P0.50_BTB0.5-60F-2.0G")
      (libsource (lib "xc7a35t") (part "BTB0.5-60F-2.0G"))
    )
    (comp (ref "U4")
      (value "BTB0.5-60F-2.0G")
      (footprint "PCB1:CONN-SMD_60P-P0.50_BTB0.5-60F-2.0G")
      (libsource (lib "xc7a35t") (part "BTB0.5-60F-2.0G"))
    )
    (comp (ref "U5")
      (value "BTB0.5-60F-2.0G")
      (footprint "PCB1:CONN-SMD_60P-P0.50_BTB0.5-60F-2.0G")
      (libsource (lib "xc7a35t") (part "BTB0.5-60F-2.0G"))
    )
    (comp (ref "U6")
      (value "SPX3819M5-L-1-5")
      (footprint "PCB1:SPX3819M5-L-1-5")
      (libsource (lib "xc7a35t") (part "SPX3819M5-L-1-5"))
    )
    (comp (ref "U7")
      (value "SPX3819M5-1-2")
      (footprint "PCB1:SOT-23-5_L2.9-W1.6-P0.95-LS2.8-BR")
      (libsource (lib "xc7a35t") (part "SPX3819M5-1-2"))
    )
    (comp (ref "U8")
      (value "W25Q128JVSIQ")
      (footprint "PCB1:SOIC-8W")
      (description "SPI FLASH")
      (libsource (lib "xc7a35t") (part "W25Q128"))
    )
    (comp (ref "U9")
      (value "NT5CB128M16IP-DI_C9900104358")
      (footprint "PCB1:TFBGA-96_L13.0-W8.0-R16-C6-P0.80-TL")
      (libsource (lib "xc7a35t") (part "NT5CB128M16IP-DI_C9900104358"))
    )
    (comp (ref "U10")
      (value "EA3059")
      (footprint "PCB1:QFN24 4X4_M")
      (libsource (lib "xc7a35t") (part "EA3059"))
    )
    (comp (ref "USBC1")
      (value "TYPE-C 2.0 -16P")
      (footprint "PCB1:USB-C-SMD_16P")
      (description "USB2.0_Type-C_16Pin母座")
      (libsource (lib "xc7a35t") (part "USB2.0_Type-C_16Pin"))
    )
    (comp (ref "X1")
      (value "80M")
      (footprint "PCB1:OSC-3225-4P")
      (description "4脚有源晶振(振荡器)")
      (libsource (lib "xc7a35t") (part "XTAL-ACT-4P"))
    )
  )
  (nets
    (net (code "1") (name "+1") (class "Default")
      (node (ref "C10") (pin "1") (pinfunction "1_1") (pintype "passive"))
      (node (ref "C103") (pin "1") (pinfunction "1_1") (pintype "passive"))
      (node (ref "C104") (pin "1") (pinfunction "1_1") (pintype "passive"))
      (node (ref "C105") (pin "1") (pinfunction "1_1") (pintype "passive"))
      (node (ref "C31") (pin "1") (pinfunction "1_1") (pintype "passive"))
      (node (ref "C32") (pin "1") (pinfunction "1_1") (pintype "passive"))
      (node (ref "C33") (pin "1") (pinfunction "1_1") (pintype "passive"))
      (node (ref "C34") (pin "1") (pinfunction "1_1") (pintype "passive"))
      (node (ref "C51") (pin "1") (pinfunction "1_1") (pintype "passive"))
      (node (ref "C52") (pin "1") (pinfunction "1_1") (pintype "passive"))
      (node (ref "C53") (pin "1") (pinfunction "1_1") (pintype "passive"))
      (node (ref "C54") (pin "1") (pinfunction "1_1") (pintype "passive"))
      (node (ref "C55") (pin "1") (pinfunction "1_1") (pintype "passive"))
      (node (ref "C56") (pin "1") (pinfunction "1_1") (pintype "passive"))
      (node (ref "C57") (pin "1") (pinfunction "1_1") (pintype "passive"))
      (node (ref "C58") (pin "1") (pinfunction "1_1") (pintype "passive"))
      (node (ref "C7") (pin "1") (pinfunction "1_1") (pintype "passive"))
      (node (ref "C71") (pin "1") (pinfunction "1_1") (pintype "passive"))
      (node (ref "C72") (pin "1") (pinfunction "1_1") (pintype "passive"))
      (node (ref "C73") (pin "1") (pinfunction "1_1") (pintype "passive"))
      (node (ref "C8") (pin "1") (pinfunction "1_1") (pintype "passive"))
      (node (ref "C9") (pin "1") (pinfunction "1_1") (pintype "passive"))
      (node (ref "FB2") (pin "1") (pinfunction "1_1") (pintype "passive"))
      (node (ref "L1") (pin "1") (pinfunction "1_1") (pintype "passive"))
      (node (ref "R34") (pin "2") (pinfunction "2_2") (pintype "passive"))
      (node (ref "TP1") (pin "1") (pinfunction "1_1") (pintype "passive"))
      (node (ref "U1") (pin "H10") (pinfunction "VCCINT_H10") (pintype "power_in"))
      (node (ref "U1") (pin "H8") (pinfunction "VCCINT_H8") (pintype "power_in"))
      (node (ref "U1") (pin "J11") (pinfunction "VCCBRAM_J11") (pintype "power_in"))
      (node (ref "U1") (pin "J7") (pinfunction "VCCINT_J7") (pintype "power_in"))
      (node (ref "U1") (pin "J9") (pinfunction "VCCINT_J9") (pintype "power_in"))
      (node (ref "U1") (pin "K8") (pinfunction "VCCINT_K8") (pintype "power_in"))
      (node (ref "U1") (pin "L11") (pinfunction "VCCBRAM_L11") (pintype "power_in"))
      (node (ref "U1") (pin "L7") (pinfunction "VCCINT_L7") (pintype "power_in"))
      (node (ref "U1") (pin "M8") (pinfunction "VCCINT_M8") (pintype "power_in"))
      (node (ref "U1") (pin "N11") (pinfunction "VCCBRAM_N11") (pintype "power_in"))
      (node (ref "U1") (pin "N7") (pinfunction "VCCINT_N7") (pintype "power_in"))
      (node (ref "U1") (pin "P10") (pinfunction "VCCINT_P10") (pintype "power_in"))
      (node (ref "U1") (pin "P8") (pinfunction "VCCINT_P8") (pintype "power_in"))
      (node (ref "U1") (pin "R7") (pinfunction "VCCINT_R7") (pintype "power_in"))
      (node (ref "U1") (pin "R9") (pinfunction "VCCINT_R9") (pintype "power_in"))
      (node (ref "U1") (pin "T10") (pinfunction "VCCINT_T10") (pintype "power_in"))
      (node (ref "U1") (pin "T8") (pinfunction "VCCINT_T8") (pintype "power_in"))
    )
    (net (code "2") (name "+1.5") (class "Default")
      (node (ref "C115") (pin "1") (pinfunction "1_1") (pintype "passive"))
      (node (ref "C116") (pin "1") (pinfunction "1_1") (pintype "passive"))
      (node (ref "C117") (pin "1") (pinfunction "1_1") (pintype "passive"))
      (node (ref "C25") (pin "1") (pinfunction "1_1") (pintype "passive"))
      (node (ref "C26") (pin "1") (pinfunction "1_1") (pintype "passive"))
      (node (ref "C27") (pin "1") (pinfunction "1_1") (pintype "passive"))
      (node (ref "C28") (pin "1") (pinfunction "1_1") (pintype "passive"))
      (node (ref "C29") (pin "1") (pinfunction "1_1") (pintype "passive"))
      (node (ref "C30") (pin "1") (pinfunction "1_1") (pintype "passive"))
      (node (ref "C75") (pin "1") (pinfunction "1_1") (pintype "passive"))
      (node (ref "C76") (pin "2") (pinfunction "2_2") (pintype "passive"))
      (node (ref "C77") (pin "2") (pinfunction "2_2") (pintype "passive"))
      (node (ref "C78") (pin "2") (pinfunction "2_2") (pintype "passive"))
      (node (ref "C79") (pin "2") (pinfunction "2_2") (pintype "passive"))
      (node (ref "C80") (pin "2") (pinfunction "2_2") (pintype "passive"))
      (node (ref "C81") (pin "2") (pinfunction "2_2") (pintype "passive"))
      (node (ref "C82") (pin "2") (pinfunction "2_2") (pintype "passive"))
      (node (ref "C83") (pin "2") (pinfunction "2_2") (pintype "passive"))
      (node (ref "C84") (pin "2") (pinfunction "2_2") (pintype "passive"))
      (node (ref "C85") (pin "2") (pinfunction "2_2") (pintype "passive"))
      (node (ref "C86") (pin "2") (pinfunction "2_2") (pintype "passive"))
      (node (ref "C96") (pin "2") (pinfunction "2_2") (pintype "passive"))
      (node (ref "L3") (pin "1") (pinfunction "1_1") (pintype "passive"))
      (node (ref "R26") (pin "2") (pinfunction "2_2") (pintype "passive"))
      (node (ref "R46") (pin "2") (pinfunction "2_2") (pintype "passive"))
      (node (ref "TP4") (pin "1") (pinfunction "1_1") (pintype "passive"))
      (node (ref "U1") (pin "C1") (pinfunction "VCCO_35_C1") (pintype "power_in"))
      (node (ref "U1") (pin "F2") (pinfunction "VCCO_35_F2") (pintype "power_in"))
      (node (ref "U1") (pin "H6") (pinfunction "VCCO_35_H6") (pintype "power_in"))
      (node (ref "U1") (pin "J3") (pinfunction "VCCO_35_J3") (pintype "power_in"))
      (node (ref "U1") (pin "M4") (pinfunction "VCCO_35_M4") (pintype "power_in"))
      (node (ref "U1") (pin "N1") (pinfunction "VCCO_35_N1") (pintype "power_in"))
      (node (ref "U9") (pin "A1") (pinfunction "VDD_A1") (pintype "passive"))
      (node (ref "U9") (pin "A8") (pinfunction "VDD_A8") (pintype "passive"))
      (node (ref "U9") (pin "B2") (pinfunction "VDD_B2") (pintype "passive"))
      (node (ref "U9") (pin "C1") (pinfunction "VDD_C1") (pintype "passive"))
      (node (ref "U9") (pin "C9") (pinfunction "VDD_C9") (pintype "passive"))
      (node (ref "U9") (pin "D2") (pinfunction "VDD_D2") (pintype "passive"))
      (node (ref "U9") (pin "D9") (pinfunction "VDD_D9") (pintype "passive"))
      (node (ref "U9") (pin "E9") (pinfunction "VDD_E9") (pintype "passive"))
      (node (ref "U9") (pin "F1") (pinfunction "VDD_F1") (pintype "passive"))
      (node (ref "U9") (pin "G7") (pinfunction "VDD_G7") (pintype "passive"))
      (node (ref "U9") (pin "H2") (pinfunction "VDD_H2") (pintype "passive"))
      (node (ref "U9") (pin "H9") (pinfunction "VDD_H9") (pintype "passive"))
      (node (ref "U9") (pin "K2") (pinfunction "VDD_K2") (pintype "passive"))
      (node (ref "U9") (pin "K8") (pinfunction "VDD_K8") (pintype "passive"))
      (node (ref "U9") (pin "N1") (pinfunction "VDD_N1") (pintype "passive"))
      (node (ref "U9") (pin "N9") (pinfunction "VDD_N9") (pintype "passive"))
      (node (ref "U9") (pin "R1") (pinfunction "VDD_R1") (pintype "passive"))
      (node (ref "U9") (pin "R9") (pinfunction "VDD_R9") (pintype "passive"))
    )
    (net (code "3") (name "+1.8") (class "Default")
      (node (ref "C109") (pin "1") (pinfunction "1_1") (pintype "passive"))
      (node (ref "C110") (pin "1") (pinfunction "1_1") (pintype "passive"))
      (node (ref "C111") (pin "1") (pinfunction "1_1") (pintype "passive"))
      (node (ref "C60") (pin "1") (pinfunction "1_1") (pintype "passive"))
      (node (ref "C61") (pin "1") (pinfunction "1_1") (pintype "passive"))
      (node (ref "C62") (pin "1") (pinfunction "1_1") (pintype "passive"))
      (node (ref "C63") (pin "1") (pinfunction "1_1") (pintype "passive"))
      (node (ref "C64") (pin "1") (pinfunction "1_1") (pintype "passive"))
      (node (ref "C65") (pin "1") (pinfunction "1_1") (pintype "passive"))
      (node (ref "C66") (pin "1") (pinfunction "1_1") (pintype "passive"))
      (node (ref "C67") (pin "1") (pinfunction "1_1") (pintype "passive"))
      (node (ref "C68") (pin "1") (pinfunction "1_1") (pintype "passive"))
      (node (ref "FB3") (pin "2") (pinfunction "2_2") (pintype "passive"))
      (node (ref "L2") (pin "1") (pinfunction "1_1") (pintype "passive"))
      (node (ref "R37") (pin "2") (pinfunction "2_2") (pintype "passive"))
      (node (ref "R56") (pin "2") (pinfunction "2_2") (pintype "passive"))
      (node (ref "R61") (pin "2") (pinfunction "2_2") (pintype "passive"))
      (node (ref "TP3") (pin "1") (pinfunction "1_1") (pintype "passive"))
      (node (ref "U1") (pin "E12") (pinfunction "VCCBATT_0_E12") (pintype "power_in"))
      (node (ref "U1") (pin "H12") (pinfunction "VCCAUX_H12") (pintype "power_in"))
      (node (ref "U1") (pin "K12") (pinfunction "VCCAUX_K12") (pintype "power_in"))
      (node (ref "U1") (pin "M12") (pinfunction "VCCAUX_M12") (pintype "power_in"))
      (node (ref "U1") (pin "P12") (pinfunction "VCCAUX_P12") (pintype "power_in"))
      (node (ref "U1") (pin "R11") (pinfunction "VCCAUX_R11") (pintype "power_in"))
    )
    (net (code "4") (name "+3.3") (class "Default")
      (node (ref "C1") (pin "1") (pinfunction "1_1") (pintype "passive"))
      (node (ref "C11") (pin "1") (pinfunction "1_1") (pintype "passive"))
      (node (ref "C12") (pin "1") (pinfunction "1_1") (pintype "passive"))
      (node (ref "C121") (pin "1") (pinfunction "1_1") (pintype "passive"))
      (node (ref "C122") (pin "1") (pinfunction "1_1") (pintype "passive"))
      (node (ref "C123") (pin "1") (pinfunction "1_1") (pintype "passive"))
      (node (ref "C13") (pin "1") (pinfunction "1_1") (pintype "passive"))
      (node (ref "C14") (pin "1") (pinfunction "1_1") (pintype "passive"))
      (node (ref "C15") (pin "1") (pinfunction "1_1") (pintype "passive"))
      (node (ref "C16") (pin "1") (pinfunction "1_1") (pintype "passive"))
      (node (ref "C19") (pin "1") (pinfunction "1_1") (pintype "passive"))
      (node (ref "C2") (pin "1") (pinfunction "1_1") (pintype "passive"))
      (node (ref "C20") (pin "1") (pinfunction "1_1") (pintype "passive"))
      (node (ref "C21") (pin "1") (pinfunction "1_1") (pintype "passive"))
      (node (ref "C22") (pin "1") (pinfunction "1_1") (pintype "passive"))
      (node (ref "C23") (pin "1") (pinfunction "1_1") (pintype "passive"))
      (node (ref "C24") (pin "1") (pinfunction "1_1") (pintype "passive"))
      (node (ref "C3") (pin "1") (pinfunction "1_1") (pintype "passive"))
      (node (ref "C35") (pin "2") (pinfunction "2_2") (pintype "passive"))
      (node (ref "C36") (pin "2") (pinfunction "2_2") (pintype "passive"))
      (node (ref "C4") (pin "1") (pinfunction "1_1") (pintype "passive"))
      (node (ref "C5") (pin "1") (pinfunction "1_1") (pintype "passive"))
      (node (ref "C59") (pin "1") (pinfunction "1_1") (pintype "passive"))
      (node (ref "C6") (pin "1") (pinfunction "1_1") (pintype "passive"))
      (node (ref "C69") (pin "1") (pinfunction "1_1") (pintype "passive"))
      (node (ref "C70") (pin "1") (pinfunction "1_1") (pintype "passive"))
      (node (ref "JP1") (pin "4") (pinfunction "4_4") (pintype "passive"))
      (node (ref "L4") (pin "1") (pinfunction "1_1") (pintype "passive"))
      (node (ref "LED3") (pin "1") (pinfunction "A_1") (pintype "passive"))
      (node (ref "R12") (pin "1") (pinfunction "1_1") (pintype "passive"))
      (node (ref "R14") (pin "1") (pinfunction "1_1") (pintype "passive"))
      (node (ref "R15") (pin "1") (pinfunction "1_1") (pintype "passive"))
      (node (ref "R16") (pin "2") (pinfunction "2_2") (pintype "passive"))
      (node (ref "R17") (pin "2") (pinfunction "2_2") (pintype "passive"))
      (node (ref "R18") (pin "2") (pinfunction "2_2") (pintype "passive"))
      (node (ref "R60") (pin "2") (pinfunction "2_2") (pintype "passive"))
      (node (ref "R8") (pin "2") (pinfunction "2_2") (pintype "passive"))
      (node (ref "R9") (pin "1") (pinfunction "1_1") (pintype "passive"))
      (node (ref "TP5") (pin "1") (pinfunction "1_1") (pintype "passive"))
      (node (ref "U1") (pin "AA17") (pinfunction "VCCO_13_AA17") (pintype "power_in"))
      (node (ref "U1") (pin "AA7") (pinfunction "VCCO_34_AA7") (pintype "power_in"))
      (node (ref "U1") (pin "AB14") (pinfunction "VCCO_13_AB14") (pintype "power_in"))
      (node (ref "U1") (pin "AB4") (pinfunction "VCCO_34_AB4") (pintype "power_in"))
      (node (ref "U1") (pin "F12") (pinfunction "VCCO_0_F12") (pintype "power_in"))
      (node (ref "U1") (pin "M14") (pinfunction "VCCO_14_M14") (pintype "power_in"))
      (node (ref "U1") (pin "P18") (pinfunction "VCCO_14_P18") (pintype "power_in"))
      (node (ref "U1") (pin "R15") (pinfunction "VCCO_14_R15") (pintype "power_in"))
      (node (ref "U1") (pin "R5") (pinfunction "VCCO_34_R5") (pintype "power_in"))
      (node (ref "U1") (pin "T12") (pinfunction "VCCO_0_T12") (pintype "power_in"))
      (node (ref "U1") (pin "T2") (pinfunction "VCCO_34_T2") (pintype "power_in"))
      (node (ref "U1") (pin "T22") (pinfunction "VCCO_14_T22") (pintype "power_in"))
      (node (ref "U1") (pin "U19") (pinfunction "VCCO_14_U19") (pintype "power_in"))
      (node (ref "U1") (pin "U8") (pinfunction "CFGBVS_0_U8") (pintype "input"))
      (node (ref "U1") (pin "V16") (pinfunction "VCCO_13_V16") (pintype "power_in"))
      (node (ref "U1") (pin "V6") (pinfunction "VCCO_34_V6") (pintype "power_in"))
      (node (ref "U1") (pin "W13") (pinfunction "VCCO_13_W13") (pintype "power_in"))
      (node (ref "U1") (pin "W3") (pinfunction "VCCO_34_W3") (pintype "power_in"))
      (node (ref "U1") (pin "Y10") (pinfunction "VCCO_13_Y10") (pintype "power_in"))
      (node (ref "U1") (pin "Y20") (pinfunction "VCCO_14_Y20") (pintype "power_in"))
      (node (ref "U2") (pin "2") (pinfunction "2_2") (pintype "passive"))
      (node (ref "U3") (pin "12") (pinfunction "12_12") (pintype "passive"))
      (node (ref "U3") (pin "50") (pinfunction "50_50") (pintype "passive"))
      (node (ref "U4") (pin "57") (pinfunction "57_57") (pintype "passive"))
      (node (ref "U6") (pin "3") (pinfunction "EN_3") (pintype "passive"))
      (node (ref "U7") (pin "1") (pinfunction "VIN_1") (pintype "passive"))
      (node (ref "U7") (pin "3") (pinfunction "EN_3") (pintype "passive"))
      (node (ref "U8") (pin "8") (pinfunction "VCC_8") (pintype "passive"))
      (node (ref "X1") (pin "4") (pinfunction "VCC_4") (pintype "passive"))
    )
    (net (code "5") (name "+3.3_B") (class "Default")
      (node (ref "C17") (pin "1") (pinfunction "1_1") (pintype "passive"))
      (node (ref "C18") (pin "1") (pinfunction "1_1") (pintype "passive"))
      (node (ref "C39") (pin "1") (pinfunction "1_1") (pintype "passive"))
      (node (ref "C40") (pin "1") (pinfunction "1_1") (pintype "passive"))
      (node (ref "C41") (pin "1") (pinfunction "1_1") (pintype "passive"))
      (node (ref "C42") (pin "1") (pinfunction "1_1") (pintype "passive"))
      (node (ref "C43") (pin "1") (pinfunction "1_1") (pintype "passive"))
      (node (ref "C44") (pin "1") (pinfunction "1_1") (pintype "passive"))
      (node (ref "C45") (pin "1") (pinfunction "1_1") (pintype "passive"))
      (node (ref "C46") (pin "1") (pinfunction "1_1") (pintype "passive"))
      (node (ref "C47") (pin "1") (pinfunction "1_1") (pintype "passive"))
      (node (ref "C48") (pin "1") (pinfunction "1_1") (pintype "passive"))
      (node (ref "C49") (pin "1") (pinfunction "1_1") (pintype "passive"))
      (node (ref "C50") (pin "1") (pinfunction "1_1") (pintype "passive"))
      (node (ref "U1") (pin "A17") (pinfunction "VCCO_16_A17") (pintype "power_in"))
      (node (ref "U1") (pin "B14") (pinfunction "VCCO_16_B14") (pintype "power_in"))
      (node (ref "U1") (pin "C21") (pinfunction "VCCO_16_C21") (pintype "power_in"))
      (node (ref "U1") (pin "D18") (pinfunction "VCCO_16_D18") (pintype "power_in"))
      (node (ref "U1") (pin "E15") (pinfunction "VCCO_16_E15") (pintype "power_in"))
      (node (ref "U1") (pin "F22") (pinfunction "VCCO_16_F22") (pintype "power_in"))
      (node (ref "U1") (pin "G19") (pinfunction "VCCO_15_G19") (pintype "power_in"))
      (node (ref "U1") (pin "H16") (pinfunction "VCCO_15_H16") (pintype "power_in"))
      (node (ref "U1") (pin "J13") (pinfunction "VCCO_15_J13") (pintype "power_in"))
      (node (ref "U1") (pin "K20") (pinfunction "VCCO_15_K20") (pintype "power_in"))
      (node (ref "U1") (pin "L17") (pinfunction "VCCO_15_L17") (pintype "power_in"))
      (node (ref "U1") (pin "N21") (pinfunction "VCCO_15_N21") (pintype "power_in"))
      (node (ref "U6") (pin "5") (pinfunction "VOUT_5") (pintype "passive"))
    )
    (net (code "6") (name "+5") (class "Default")
      (node (ref "C102") (pin "2") (pinfunction "2_2") (pintype "passive"))
      (node (ref "C106") (pin "2") (pinfunction "2_2") (pintype "passive"))
      (node (ref "C107") (pin "2") (pinfunction "2_2") (pintype "passive"))
      (node (ref "C108") (pin "2") (pinfunction "2_2") (pintype "passive"))
      (node (ref "C112") (pin "2") (pinfunction "2_2") (pintype "passive"))
      (node (ref "C114") (pin "2") (pinfunction "2_2") (pintype "passive"))
      (node (ref "C91") (pin "2") (pinfunction "2_2") (pintype "passive"))
      (node (ref "C92") (pin "2") (pinfunction "2_2") (pintype "passive"))
      (node (ref "C95") (pin "2") (pinfunction "2_2") (pintype "passive"))
      (node (ref "C98") (pin "2") (pinfunction "2_2") (pintype "passive"))
      (node (ref "E1") (pin "1") (pinfunction "1_1") (pintype "passive"))
      (node (ref "LED2") (pin "1") (pinfunction "A_1") (pintype "passive"))
      (node (ref "R48") (pin "2") (pinfunction "2_2") (pintype "passive"))
      (node (ref "R52") (pin "2") (pinfunction "2_2") (pintype "passive"))
      (node (ref "TP2") (pin "1") (pinfunction "1_1") (pintype "passive"))
      (node (ref "U10") (pin "11") (pinfunction "VIN1_11") (pintype "passive"))
      (node (ref "U10") (pin "20") (pinfunction "VIN4_20") (pintype "passive"))
      (node (ref "U10") (pin "23") (pinfunction "VIN3_23") (pintype "passive"))
      (node (ref "U10") (pin "3") (pinfunction "VCC_3") (pintype "passive"))
      (node (ref "U10") (pin "8") (pinfunction "VIN2_8") (pintype "passive"))
      (node (ref "U2") (pin "1") (pinfunction "1_1") (pintype "passive"))
      (node (ref "U3") (pin "52") (pinfunction "52_52") (pintype "passive"))
      (node (ref "U3") (pin "54") (pinfunction "54_54") (pintype "passive"))
      (node (ref "U3") (pin "56") (pinfunction "56_56") (pintype "passive"))
      (node (ref "U4") (pin "1") (pinfunction "1_1") (pintype "passive"))
      (node (ref "U5") (pin "1") (pinfunction "1_1") (pintype "passive"))
      (node (ref "U5") (pin "3") (pinfunction "3_3") (pintype "passive"))
      (node (ref "U5") (pin "5") (pinfunction "5_5") (pintype "passive"))
      (node (ref "U6") (pin "1") (pinfunction "VIN_1") (pintype "passive"))
      (node (ref "USBC1") (pin "A4") (pinfunction "VBUS_A4") (pintype "passive"))
      (node (ref "USBC1") (pin "A9") (pinfunction "VBUS_A9") (pintype "passive"))
      (node (ref "USBC1") (pin "B4") (pinfunction "VBUS_B4") (pintype "passive"))
      (node (ref "USBC1") (pin "B9") (pinfunction "VBUS_B9") (pintype "passive"))
    )
    (net (code "7") (name "/B14_IO0") (class "Default")
      (node (ref "U1") (pin "P20") (pinfunction "IO_0_14_P20") (pintype "bidirectional"))
      (node (ref "U3") (pin "39") (pinfunction "39_39") (pintype "passive"))
    )
    (net (code "8") (name "/B14_IO25") (class "Default")
      (node (ref "U1") (pin "N15") (pinfunction "IO_25_14_N15") (pintype "bidirectional"))
      (node (ref "U3") (pin "1") (pinfunction "1_1") (pintype "passive"))
    )
    (net (code "9") (name "/B14_N_L3") (class "Default")
      (node (ref "U1") (pin "V22") (pinfunction "IO_L3N_T0_DQS_EMCCLK_14_V22") (pintype "bidirectional"))
      (node (ref "U3") (pin "41") (pinfunction "41_41") (pintype "passive"))
    )
    (net (code "10") (name "/B14_N_L4") (class "Default")
      (node (ref "U1") (pin "U21") (pinfunction "IO_L4N_T0_D05_14_U21") (pintype "bidirectional"))
      (node (ref "U3") (pin "45") (pinfunction "45_45") (pintype "passive"))
    )
    (net (code "11") (name "/B14_N_L5") (class "Default")
      (node (ref "U1") (pin "R19") (pinfunction "IO_L5N_T0_D07_14_R19") (pintype "bidirectional"))
      (node (ref "U3") (pin "36") (pinfunction "36_36") (pintype "passive"))
    )
    (net (code "12") (name "/B14_N_L6") (class "Default")
      (node (ref "U1") (pin "T20") (pinfunction "IO_L6N_T0_D08_VREF_14_T20") (pintype "bidirectional"))
      (node (ref "U3") (pin "30") (pinfunction "30_30") (pintype "passive"))
    )
    (net (code "13") (name "/B14_N_L7") (class "Default")
      (node (ref "U1") (pin "W22") (pinfunction "IO_L7N_T1_D10_14_W22") (pintype "bidirectional"))
      (node (ref "U3") (pin "37") (pinfunction "37_37") (pintype "passive"))
    )
    (net (code "14") (name "/B14_N_L8") (class "Default")
      (node (ref "U1") (pin "AA21") (pinfunction "IO_L8N_T1_D12_14_AA21") (pintype "bidirectional"))
      (node (ref "U3") (pin "34") (pinfunction "34_34") (pintype "passive"))
    )
    (net (code "15") (name "/B14_N_L9") (class "Default")
      (node (ref "U1") (pin "Y22") (pinfunction "IO_L9N_T1_DQS_D13_14_Y22") (pintype "bidirectional"))
      (node (ref "U3") (pin "16") (pinfunction "16_16") (pintype "passive"))
    )
    (net (code "16") (name "/B14_N_L10") (class "Default")
      (node (ref "U1") (pin "AB22") (pinfunction "IO_L10N_T1_D15_14_AB22") (pintype "bidirectional"))
      (node (ref "U3") (pin "10") (pinfunction "10_10") (pintype "passive"))
    )
    (net (code "17") (name "/B14_N_L11") (class "Default")
      (node (ref "U1") (pin "V20") (pinfunction "IO_L11N_T1_SRCC_14_V20") (pintype "bidirectional"))
      (node (ref "U3") (pin "31") (pinfunction "31_31") (pintype "passive"))
    )
    (net (code "18") (name "/B14_N_L12") (class "Default")
      (node (ref "U1") (pin "W20") (pinfunction "IO_L12N_T1_MRCC_14_W20") (pintype "bidirectional"))
      (node (ref "U3") (pin "29") (pinfunction "29_29") (pintype "passive"))
    )
    (net (code "19") (name "/B14_N_L13") (class "Default")
      (node (ref "U1") (pin "Y19") (pinfunction "IO_L13N_T2_MRCC_14_Y19") (pintype "bidirectional"))
      (node (ref "U3") (pin "25") (pinfunction "25_25") (pintype "passive"))
    )
    (net (code "20") (name "/B14_N_L14") (class "Default")
      (node (ref "U1") (pin "V19") (pinfunction "IO_L14N_T2_SRCC_14_V19") (pintype "bidirectional"))
      (node (ref "U3") (pin "24") (pinfunction "24_24") (pintype "passive"))
    )
    (net (code "21") (name "/B14_N_L15") (class "Default")
      (node (ref "U1") (pin "AB20") (pinfunction "IO_L15N_T2_DQS_DOUT_CSO_B_14_AB20") (pintype "bidirectional"))
      (node (ref "U2") (pin "49") (pinfunction "49_49") (pintype "passive"))
    )
    (net (code "22") (name "/B14_N_L16") (class "Default")
      (node (ref "U1") (pin "W17") (pinfunction "IO_L16N_T2_A15_D31_14_W17") (pintype "bidirectional"))
      (node (ref "U3") (pin "19") (pinfunction "19_19") (pintype "passive"))
    )
    (net (code "23") (name "/B14_N_L17") (class "Default")
      (node (ref "U1") (pin "AB18") (pinfunction "IO_L17N_T2_A13_D29_14_AB18") (pintype "bidirectional"))
      (node (ref "U2") (pin "43") (pinfunction "43_43") (pintype "passive"))
    )
    (net (code "24") (name "/B14_N_L18") (class "Default")
      (node (ref "U1") (pin "U18") (pinfunction "IO_L18N_T2_A11_D27_14_U18") (pintype "bidirectional"))
      (node (ref "U3") (pin "20") (pinfunction "20_20") (pintype "passive"))
    )
    (net (code "25") (name "/B14_N_L19") (class "Default")
      (node (ref "U1") (pin "R14") (pinfunction "IO_L19N_T3_A09_D25_VREF_14_R14") (pintype "bidirectional"))
      (node (ref "U3") (pin "11") (pinfunction "11_11") (pintype "passive"))
    )
    (net (code "26") (name "/B14_N_L20") (class "Default")
      (node (ref "U1") (pin "T18") (pinfunction "IO_L20N_T3_A07_D23_14_T18") (pintype "bidirectional"))
      (node (ref "U3") (pin "26") (pinfunction "26_26") (pintype "passive"))
    )
    (net (code "27") (name "/B14_N_L21") (class "Default")
      (node (ref "U1") (pin "P17") (pinfunction "IO_L21N_T3_DQS_A06_D22_14_P17") (pintype "bidirectional"))
      (node (ref "U3") (pin "4") (pinfunction "4_4") (pintype "passive"))
    )
    (net (code "28") (name "/B14_N_L22") (class "Default")
      (node (ref "U1") (pin "R16") (pinfunction "IO_L22N_T3_A04_D20_14_R16") (pintype "bidirectional"))
      (node (ref "U3") (pin "17") (pinfunction "17_17") (pintype "passive"))
    )
    (net (code "29") (name "/B14_N_L23") (class "Default")
      (node (ref "U1") (pin "N14") (pinfunction "IO_L23N_T3_A02_D18_14_N14") (pintype "bidirectional"))
      (node (ref "U2") (pin "53") (pinfunction "53_53") (pintype "passive"))
    )
    (net (code "30") (name "/B14_N_L24") (class "Default")
      (node (ref "U1") (pin "R17") (pinfunction "IO_L24N_T3_A00_D16_14_R17") (pintype "bidirectional"))
      (node (ref "U2") (pin "57") (pinfunction "57_57") (pintype "passive"))
    )
    (net (code "31") (name "/B14_P_L3") (class "Default")
      (node (ref "U1") (pin "U22") (pinfunction "IO_L3P_T0_DQS_PUDC_B_14_U22") (pintype "bidirectional"))
      (node (ref "U3") (pin "43") (pinfunction "43_43") (pintype "passive"))
    )
    (net (code "32") (name "/B14_P_L4") (class "Default")
      (node (ref "U1") (pin "T21") (pinfunction "IO_L4P_T0_D04_14_T21") (pintype "bidirectional"))
      (node (ref "U3") (pin "47") (pinfunction "47_47") (pintype "passive"))
    )
    (net (code "33") (name "/B14_P_L5") (class "Default")
      (node (ref "U1") (pin "P19") (pinfunction "IO_L5P_T0_D06_14_P19") (pintype "bidirectional"))
      (node (ref "U3") (pin "38") (pinfunction "38_38") (pintype "passive"))
    )
    (net (code "34") (name "/B14_P_L7") (class "Default")
      (node (ref "U1") (pin "W21") (pinfunction "IO_L7P_T1_D09_14_W21") (pintype "bidirectional"))
      (node (ref "U3") (pin "35") (pinfunction "35_35") (pintype "passive"))
    )
    (net (code "35") (name "/B14_P_L8") (class "Default")
      (node (ref "U1") (pin "AA20") (pinfunction "IO_L8P_T1_D11_14_AA20") (pintype "bidirectional"))
      (node (ref "U3") (pin "32") (pinfunction "32_32") (pintype "passive"))
    )
    (net (code "36") (name "/B14_P_L9") (class "Default")
      (node (ref "U1") (pin "Y21") (pinfunction "IO_L9P_T1_DQS_14_Y21") (pintype "bidirectional"))
      (node (ref "U3") (pin "14") (pinfunction "14_14") (pintype "passive"))
    )
    (net (code "37") (name "/B14_P_L10") (class "Default")
      (node (ref "U1") (pin "AB21") (pinfunction "IO_L10P_T1_D14_14_AB21") (pintype "bidirectional"))
      (node (ref "U3") (pin "8") (pinfunction "8_8") (pintype "passive"))
    )
    (net (code "38") (name "/B14_P_L11") (class "Default")
      (node (ref "U1") (pin "U20") (pinfunction "IO_L11P_T1_SRCC_14_U20") (pintype "bidirectional"))
      (node (ref "U3") (pin "33") (pinfunction "33_33") (pintype "passive"))
    )
    (net (code "39") (name "/B14_P_L12") (class "Default")
      (node (ref "U1") (pin "W19") (pinfunction "IO_L12P_T1_MRCC_14_W19") (pintype "bidirectional"))
      (node (ref "U3") (pin "27") (pinfunction "27_27") (pintype "passive"))
    )
    (net (code "40") (name "/B14_P_L13") (class "Default")
      (node (ref "U1") (pin "Y18") (pinfunction "IO_L13P_T2_MRCC_14_Y18") (pintype "bidirectional"))
      (node (ref "U3") (pin "23") (pinfunction "23_23") (pintype "passive"))
    )
    (net (code "41") (name "/B14_P_L14") (class "Default")
      (node (ref "U1") (pin "V18") (pinfunction "IO_L14P_T2_SRCC_14_V18") (pintype "bidirectional"))
      (node (ref "U3") (pin "22") (pinfunction "22_22") (pintype "passive"))
    )
    (net (code "42") (name "/B14_P_L15") (class "Default")
      (node (ref "U1") (pin "AA19") (pinfunction "IO_L15P_T2_DQS_RDWR_B_14_AA19") (pintype "bidirectional"))
      (node (ref "U2") (pin "47") (pinfunction "47_47") (pintype "passive"))
    )
    (net (code "43") (name "/B14_P_L16") (class "Default")
      (node (ref "U1") (pin "V17") (pinfunction "IO_L16P_T2_CSI_B_14_V17") (pintype "bidirectional"))
      (node (ref "U3") (pin "21") (pinfunction "21_21") (pintype "passive"))
    )
    (net (code "44") (name "/B14_P_L17") (class "Default")
      (node (ref "U1") (pin "AA18") (pinfunction "IO_L17P_T2_A14_D30_14_AA18") (pintype "bidirectional"))
      (node (ref "U2") (pin "45") (pinfunction "45_45") (pintype "passive"))
    )
    (net (code "45") (name "/B14_P_L18") (class "Default")
      (node (ref "U1") (pin "U17") (pinfunction "IO_L18P_T2_A12_D28_14_U17") (pintype "bidirectional"))
      (node (ref "U3") (pin "18") (pinfunction "18_18") (pintype "passive"))
    )
    (net (code "46") (name "/B14_P_L19") (class "Default")
      (node (ref "U1") (pin "P14") (pinfunction "IO_L19P_T3_A10_D26_14_P14") (pintype "bidirectional"))
      (node (ref "U3") (pin "13") (pinfunction "13_13") (pintype "passive"))
    )
    (net (code "47") (name "/B14_P_L20") (class "Default")
      (node (ref "U1") (pin "R18") (pinfunction "IO_L20P_T3_A08_D24_14_R18") (pintype "bidirectional"))
      (node (ref "U3") (pin "28") (pinfunction "28_28") (pintype "passive"))
    )
    (net (code "48") (name "/B14_P_L21") (class "Default")
      (node (ref "U1") (pin "N17") (pinfunction "IO_L21P_T3_DQS_14_N17") (pintype "bidirectional"))
      (node (ref "U3") (pin "6") (pinfunction "6_6") (pintype "passive"))
    )
    (net (code "49") (name "/B14_P_L22") (class "Default")
      (node (ref "U1") (pin "P15") (pinfunction "IO_L22P_T3_A05_D21_14_P15") (pintype "bidirectional"))
      (node (ref "U3") (pin "15") (pinfunction "15_15") (pintype "passive"))
    )
    (net (code "50") (name "/B14_P_L23") (class "Default")
      (node (ref "U1") (pin "N13") (pinfunction "IO_L23P_T3_A03_D19_14_N13") (pintype "bidirectional"))
      (node (ref "U2") (pin "51") (pinfunction "51_51") (pintype "passive"))
    )
    (net (code "51") (name "/B14_P_L24") (class "Default")
      (node (ref "U1") (pin "P16") (pinfunction "IO_L24P_T3_A01_D17_14_P16") (pintype "bidirectional"))
      (node (ref "U2") (pin "55") (pinfunction "55_55") (pintype "passive"))
    )
    (net (code "52") (name "/B15_IO0") (class "Default")
      (node (ref "U1") (pin "J16") (pinfunction "IO_0_15_J16") (pintype "bidirectional"))
      (node (ref "U4") (pin "35") (pinfunction "35_35") (pintype "passive"))
    )
    (net (code "53") (name "/B15_IO25") (class "Default")
      (node (ref "U1") (pin "M17") (pinfunction "IO_25_15_M17") (pintype "bidirectional"))
      (node (ref "U3") (pin "2") (pinfunction "2_2") (pintype "passive"))
    )
    (net (code "54") (name "/B15_N_L1") (class "Default")
      (node (ref "U1") (pin "G13") (pinfunction "IO_L1N_T0_AD0N_15_G13") (pintype "bidirectional"))
      (node (ref "U4") (pin "21") (pinfunction "21_21") (pintype "passive"))
    )
    (net (code "55") (name "/B15_N_L2") (class "Default")
      (node (ref "U1") (pin "G16") (pinfunction "IO_L2N_T0_AD8N_15_G16") (pintype "bidirectional"))
      (node (ref "U4") (pin "29") (pinfunction "29_29") (pintype "passive"))
    )
    (net (code "56") (name "/B15_N_L3") (class "Default")
      (node (ref "U1") (pin "H14") (pinfunction "IO_L3N_T0_DQS_AD1N_15_H14") (pintype "bidirectional"))
      (node (ref "U4") (pin "24") (pinfunction "24_24") (pintype "passive"))
    )
    (net (code "57") (name "/B15_N_L4") (class "Default")
      (node (ref "U1") (pin "G18") (pinfunction "IO_L4N_T0_15_G18") (pintype "bidirectional"))
      (node (ref "U4") (pin "36") (pinfunction "36_36") (pintype "passive"))
    )
    (net (code "58") (name "/B15_N_L5") (class "Default")
      (node (ref "U1") (pin "H15") (pinfunction "IO_L5N_T0_AD9N_15_H15") (pintype "bidirectional"))
      (node (ref "U4") (pin "27") (pinfunction "27_27") (pintype "passive"))
    )
    (net (code "59") (name "/B15_N_L6") (class "Default")
      (node (ref "U1") (pin "H18") (pinfunction "IO_L6N_T0_VREF_15_H18") (pintype "bidirectional"))
      (node (ref "U4") (pin "40") (pinfunction "40_40") (pintype "passive"))
    )
    (net (code "60") (name "/B15_N_L7") (class "Default")
      (node (ref "U1") (pin "H22") (pinfunction "IO_L7N_T1_AD2N_15_H22") (pintype "bidirectional"))
      (node (ref "U4") (pin "47") (pinfunction "47_47") (pintype "passive"))
    )
    (net (code "61") (name "/B15_N_L8") (class "Default")
      (node (ref "U1") (pin "G20") (pinfunction "IO_L8N_T1_AD10N_15_G20") (pintype "bidirectional"))
      (node (ref "U4") (pin "38") (pinfunction "38_38") (pintype "passive"))
    )
    (net (code "62") (name "/B15_N_L9") (class "Default")
      (node (ref "U1") (pin "K22") (pinfunction "IO_L9N_T1_DQS_AD3N_15_K22") (pintype "bidirectional"))
      (node (ref "U4") (pin "55") (pinfunction "55_55") (pintype "passive"))
    )
    (net (code "63") (name "/B15_N_L10") (class "Default")
      (node (ref "U1") (pin "L21") (pinfunction "IO_L10N_T1_AD11N_15_L21") (pintype "bidirectional"))
      (node (ref "U3") (pin "48") (pinfunction "48_48") (pintype "passive"))
    )
    (net (code "64") (name "/B15_N_L11") (class "Default")
      (node (ref "U1") (pin "J21") (pinfunction "IO_L11N_T1_SRCC_15_J21") (pintype "bidirectional"))
      (node (ref "U4") (pin "49") (pinfunction "49_49") (pintype "passive"))
    )
    (net (code "65") (name "/B15_N_L12") (class "Default")
      (node (ref "U1") (pin "H19") (pinfunction "IO_L12N_T1_MRCC_15_H19") (pintype "bidirectional"))
      (node (ref "U4") (pin "42") (pinfunction "42_42") (pintype "passive"))
    )
    (net (code "66") (name "/B15_N_L13") (class "Default")
      (node (ref "U1") (pin "K19") (pinfunction "IO_L13N_T2_MRCC_15_K19") (pintype "bidirectional"))
      (node (ref "U4") (pin "56") (pinfunction "56_56") (pintype "passive"))
    )
    (net (code "67") (name "/B15_N_L14") (class "Default")
      (node (ref "U1") (pin "L20") (pinfunction "IO_L14N_T2_SRCC_15_L20") (pintype "bidirectional"))
      (node (ref "U4") (pin "60") (pinfunction "60_60") (pintype "passive"))
    )
    (net (code "68") (name "/B15_N_L15") (class "Default")
      (node (ref "U1") (pin "M22") (pinfunction "IO_L15N_T2_DQS_ADV_B_15_M22") (pintype "bidirectional"))
      (node (ref "U3") (pin "55") (pinfunction "55_55") (pintype "passive"))
    )
    (net (code "69") (name "/B15_N_L16") (class "Default")
      (node (ref "U1") (pin "L18") (pinfunction "IO_L16N_T2_A27_15_L18") (pintype "bidirectional"))
      (node (ref "U3") (pin "42") (pinfunction "42_42") (pintype "passive"))
    )
    (net (code "70") (name "/B15_N_L17") (class "Default")
      (node (ref "U1") (pin "N19") (pinfunction "IO_L17N_T2_A25_15_N19") (pintype "bidirectional"))
      (node (ref "U3") (pin "46") (pinfunction "46_46") (pintype "passive"))
    )
    (net (code "71") (name "/B15_N_L18") (class "Default")
      (node (ref "U1") (pin "M20") (pinfunction "IO_L18N_T2_A23_15_M20") (pintype "bidirectional"))
      (node (ref "U3") (pin "51") (pinfunction "51_51") (pintype "passive"))
    )
    (net (code "72") (name "/B15_N_L19") (class "Default")
      (node (ref "U1") (pin "K14") (pinfunction "IO_L19N_T3_A21_VREF_15_K14") (pintype "bidirectional"))
      (node (ref "U4") (pin "30") (pinfunction "30_30") (pintype "passive"))
    )
    (net (code "73") (name "/B15_N_L20") (class "Default")
      (node (ref "U1") (pin "L13") (pinfunction "IO_L20N_T3_A19_15_L13") (pintype "bidirectional"))
      (node (ref "U4") (pin "4") (pinfunction "4_4") (pintype "passive"))
    )
    (net (code "74") (name "/B15_N_L21") (class "Default")
      (node (ref "U1") (pin "J17") (pinfunction "IO_L21N_T3_DQS_A18_15_J17") (pintype "bidirectional"))
      (node (ref "U4") (pin "37") (pinfunction "37_37") (pintype "passive"))
    )
    (net (code "75") (name "/B15_N_L22") (class "Default")
      (node (ref "U1") (pin "L15") (pinfunction "IO_L22N_T3_A16_15_L15") (pintype "bidirectional"))
      (node (ref "U4") (pin "34") (pinfunction "34_34") (pintype "passive"))
    )
    (net (code "76") (name "/B15_N_L23") (class "Default")
      (node (ref "U1") (pin "K16") (pinfunction "IO_L23N_T3_FWE_B_15_K16") (pintype "bidirectional"))
      (node (ref "U4") (pin "39") (pinfunction "39_39") (pintype "passive"))
    )
    (net (code "77") (name "/B15_N_L24") (class "Default")
      (node (ref "U1") (pin "M16") (pinfunction "IO_L24N_T3_RS0_15_M16") (pintype "bidirectional"))
      (node (ref "U4") (pin "48") (pinfunction "48_48") (pintype "passive"))
    )
    (net (code "78") (name "/B15_P_L1") (class "Default")
      (node (ref "U1") (pin "H13") (pinfunction "IO_L1P_T0_AD0P_15_H13") (pintype "bidirectional"))
      (node (ref "U4") (pin "23") (pinfunction "23_23") (pintype "passive"))
    )
    (net (code "79") (name "/B15_P_L2") (class "Default")
      (node (ref "U1") (pin "G15") (pinfunction "IO_L2P_T0_AD8P_15_G15") (pintype "bidirectional"))
      (node (ref "U4") (pin "25") (pinfunction "25_25") (pintype "passive"))
    )
    (net (code "80") (name "/B15_P_L3") (class "Default")
      (node (ref "U1") (pin "J14") (pinfunction "IO_L3P_T0_DQS_AD1P_15_J14") (pintype "bidirectional"))
      (node (ref "U4") (pin "26") (pinfunction "26_26") (pintype "passive"))
    )
    (net (code "81") (name "/B15_P_L4") (class "Default")
      (node (ref "U1") (pin "G17") (pinfunction "IO_L4P_T0_15_G17") (pintype "bidirectional"))
      (node (ref "U4") (pin "31") (pinfunction "31_31") (pintype "passive"))
    )
    (net (code "82") (name "/B15_P_L5") (class "Default")
      (node (ref "U1") (pin "J15") (pinfunction "IO_L5P_T0_AD9P_15_J15") (pintype "bidirectional"))
      (node (ref "U4") (pin "28") (pinfunction "28_28") (pintype "passive"))
    )
    (net (code "83") (name "/B15_P_L6") (class "Default")
      (node (ref "U1") (pin "H17") (pinfunction "IO_L6P_T0_15_H17") (pintype "bidirectional"))
      (node (ref "U4") (pin "33") (pinfunction "33_33") (pintype "passive"))
    )
    (net (code "84") (name "/B15_P_L7") (class "Default")
      (node (ref "U1") (pin "J22") (pinfunction "IO_L7P_T1_AD2P_15_J22") (pintype "bidirectional"))
      (node (ref "U4") (pin "51") (pinfunction "51_51") (pintype "passive"))
    )
    (net (code "85") (name "/B15_P_L8") (class "Default")
      (node (ref "U1") (pin "H20") (pinfunction "IO_L8P_T1_AD10P_15_H20") (pintype "bidirectional"))
      (node (ref "U4") (pin "44") (pinfunction "44_44") (pintype "passive"))
    )
    (net (code "86") (name "/B15_P_L9") (class "Default")
      (node (ref "U1") (pin "K21") (pinfunction "IO_L9P_T1_DQS_AD3P_15_K21") (pintype "bidirectional"))
      (node (ref "U4") (pin "53") (pinfunction "53_53") (pintype "passive"))
    )
    (net (code "87") (name "/B15_P_L10") (class "Default")
      (node (ref "U1") (pin "M21") (pinfunction "IO_L10P_T1_AD11P_15_M21") (pintype "bidirectional"))
      (node (ref "U4") (pin "45") (pinfunction "45_45") (pintype "passive"))
    )
    (net (code "88") (name "/B15_P_L11") (class "Default")
      (node (ref "U1") (pin "J20") (pinfunction "IO_L11P_T1_SRCC_15_J20") (pintype "bidirectional"))
      (node (ref "U4") (pin "52") (pinfunction "52_52") (pintype "passive"))
    )
    (net (code "89") (name "/B15_P_L12") (class "Default")
      (node (ref "U1") (pin "J19") (pinfunction "IO_L12P_T1_MRCC_15_J19") (pintype "bidirectional"))
      (node (ref "U4") (pin "50") (pinfunction "50_50") (pintype "passive"))
    )
    (net (code "90") (name "/B15_P_L13") (class "Default")
      (node (ref "U1") (pin "K18") (pinfunction "IO_L13P_T2_MRCC_15_K18") (pintype "bidirectional"))
      (node (ref "U4") (pin "54") (pinfunction "54_54") (pintype "passive"))
    )
    (net (code "91") (name "/B15_P_L14") (class "Default")
      (node (ref "U1") (pin "L19") (pinfunction "IO_L14P_T2_SRCC_15_L19") (pintype "bidirectional"))
      (node (ref "U4") (pin "58") (pinfunction "58_58") (pintype "passive"))
    )
    (net (code "92") (name "/B15_P_L15") (class "Default")
      (node (ref "U1") (pin "N22") (pinfunction "IO_L15P_T2_DQS_15_N22") (pintype "bidirectional"))
      (node (ref "U3") (pin "53") (pinfunction "53_53") (pintype "passive"))
    )
    (net (code "93") (name "/B15_P_L16") (class "Default")
      (node (ref "U1") (pin "M18") (pinfunction "IO_L16P_T2_A28_15_M18") (pintype "bidirectional"))
      (node (ref "U3") (pin "40") (pinfunction "40_40") (pintype "passive"))
    )
    (net (code "94") (name "/B15_P_L17") (class "Default")
      (node (ref "U1") (pin "N18") (pinfunction "IO_L17P_T2_A26_15_N18") (pintype "bidirectional"))
      (node (ref "U3") (pin "44") (pinfunction "44_44") (pintype "passive"))
    )
    (net (code "95") (name "/B15_P_L18") (class "Default")
      (node (ref "U1") (pin "N20") (pinfunction "IO_L18P_T2_A24_15_N20") (pintype "bidirectional"))
      (node (ref "U3") (pin "49") (pinfunction "49_49") (pintype "passive"))
    )
    (net (code "96") (name "/B15_P_L19") (class "Default")
      (node (ref "U1") (pin "K13") (pinfunction "IO_L19P_T3_A22_15_K13") (pintype "bidirectional"))
      (node (ref "U4") (pin "22") (pinfunction "22_22") (pintype "passive"))
    )
    (net (code "97") (name "/B15_P_L20") (class "Default")
      (node (ref "U1") (pin "M13") (pinfunction "IO_L20P_T3_A20_15_M13") (pintype "bidirectional"))
      (node (ref "U4") (pin "2") (pinfunction "2_2") (pintype "passive"))
    )
    (net (code "98") (name "/B15_P_L21") (class "Default")
      (node (ref "U1") (pin "K17") (pinfunction "IO_L21P_T3_DQS_15_K17") (pintype "bidirectional"))
      (node (ref "U4") (pin "41") (pinfunction "41_41") (pintype "passive"))
    )
    (net (code "99") (name "/B15_P_L22") (class "Default")
      (node (ref "U1") (pin "L14") (pinfunction "IO_L22P_T3_A17_15_L14") (pintype "bidirectional"))
      (node (ref "U4") (pin "32") (pinfunction "32_32") (pintype "passive"))
    )
    (net (code "100") (name "/B15_P_L23") (class "Default")
      (node (ref "U1") (pin "L16") (pinfunction "IO_L23P_T3_FOE_B_15_L16") (pintype "bidirectional"))
      (node (ref "U4") (pin "43") (pinfunction "43_43") (pintype "passive"))
    )
    (net (code "101") (name "/B15_P_L24") (class "Default")
      (node (ref "U1") (pin "M15") (pinfunction "IO_L24P_T3_RS1_15_M15") (pintype "bidirectional"))
      (node (ref "U4") (pin "46") (pinfunction "46_46") (pintype "passive"))
    )
    (net (code "102") (name "/B16_IO0") (class "Default")
      (node (ref "LED4") (pin "1") (pinfunction "A_1") (pintype "passive"))
      (node (ref "U1") (pin "F15") (pinfunction "IO_0_16_F15") (pintype "bidirectional"))
      (node (ref "U5") (pin "6") (pinfunction "6_6") (pintype "passive"))
    )
    (net (code "103") (name "/B16_IO25") (class "Default")
      (node (ref "U1") (pin "F21") (pinfunction "IO_25_16_F21") (pintype "bidirectional"))
      (node (ref "U4") (pin "15") (pinfunction "15_15") (pintype "passive"))
    )
    (net (code "104") (name "/B16_N_L1") (class "Default")
      (node (ref "U1") (pin "F14") (pinfunction "IO_L1N_T0_16_F14") (pintype "bidirectional"))
      (node (ref "U5") (pin "10") (pinfunction "10_10") (pintype "passive"))
    )
    (net (code "105") (name "/B16_N_L2") (class "Default")
      (node (ref "U1") (pin "E17") (pinfunction "IO_L2N_T0_16_E17") (pintype "bidirectional"))
      (node (ref "U5") (pin "26") (pinfunction "26_26") (pintype "passive"))
    )
    (net (code "106") (name "/B16_N_L3") (class "Default")
      (node (ref "U1") (pin "C15") (pinfunction "IO_L3N_T0_DQS_16_C15") (pintype "bidirectional"))
      (node (ref "U5") (pin "38") (pinfunction "38_38") (pintype "passive"))
    )
    (net (code "107") (name "/B16_N_L4") (class "Default")
      (node (ref "U1") (pin "E14") (pinfunction "IO_L4N_T0_16_E14") (pintype "bidirectional"))
      (node (ref "U5") (pin "14") (pinfunction "14_14") (pintype "passive"))
    )
    (net (code "108") (name "/B16_N_L5") (class "Default")
      (node (ref "U1") (pin "D16") (pinfunction "IO_L5N_T0_16_D16") (pintype "bidirectional"))
      (node (ref "U5") (pin "20") (pinfunction "20_20") (pintype "passive"))
    )
    (net (code "109") (name "/B16_N_L6") (class "Default")
      (node (ref "U1") (pin "D15") (pinfunction "IO_L6N_T0_VREF_16_D15") (pintype "bidirectional"))
      (node (ref "U5") (pin "18") (pinfunction "18_18") (pintype "passive"))
    )
    (net (code "110") (name "/B16_N_L7") (class "Default")
      (node (ref "U1") (pin "B16") (pinfunction "IO_L7N_T1_16_B16") (pintype "bidirectional"))
      (node (ref "U5") (pin "42") (pinfunction "42_42") (pintype "passive"))
    )
    (net (code "111") (name "/B16_N_L8") (class "Default")
      (node (ref "U1") (pin "B13") (pinfunction "IO_L8N_T1_16_B13") (pintype "bidirectional"))
      (node (ref "U5") (pin "32") (pinfunction "32_32") (pintype "passive"))
    )
    (net (code "112") (name "/B16_N_L9") (class "Default")
      (node (ref "U1") (pin "A16") (pinfunction "IO_L9N_T1_DQS_16_A16") (pintype "bidirectional"))
      (node (ref "U5") (pin "53") (pinfunction "53_53") (pintype "passive"))
    )
    (net (code "113") (name "/B16_N_L10") (class "Default")
      (node (ref "U1") (pin "A14") (pinfunction "IO_L10N_T1_16_A14") (pintype "bidirectional"))
      (node (ref "U5") (pin "49") (pinfunction "49_49") (pintype "passive"))
    )
    (net (code "114") (name "/B16_N_L11") (class "Default")
      (node (ref "U1") (pin "B18") (pinfunction "IO_L11N_T1_SRCC_16_B18") (pintype "bidirectional"))
      (node (ref "U5") (pin "50") (pinfunction "50_50") (pintype "passive"))
    )
    (net (code "115") (name "/B16_N_L12") (class "Default")
      (node (ref "U1") (pin "C17") (pinfunction "IO_L12N_T1_MRCC_16_C17") (pintype "bidirectional"))
      (node (ref "U5") (pin "46") (pinfunction "46_46") (pintype "passive"))
    )
    (net (code "116") (name "/B16_N_L13") (class "Default")
      (node (ref "U1") (pin "C19") (pinfunction "IO_L13N_T2_MRCC_16_C19") (pintype "bidirectional"))
      (node (ref "U5") (pin "54") (pinfunction "54_54") (pintype "passive"))
    )
    (net (code "117") (name "/B16_N_L14") (class "Default")
      (node (ref "U1") (pin "D19") (pinfunction "IO_L14N_T2_SRCC_16_D19") (pintype "bidirectional"))
      (node (ref "U5") (pin "28") (pinfunction "28_28") (pintype "passive"))
    )
    (net (code "118") (name "/B16_N_L15") (class "Default")
      (node (ref "U1") (pin "E18") (pinfunction "IO_L15N_T2_DQS_16_E18") (pintype "bidirectional"))
      (node (ref "U5") (pin "57") (pinfunction "57_57") (pintype "passive"))
    )
    (net (code "119") (name "/B16_N_L16") (class "Default")
      (node (ref "U1") (pin "A20") (pinfunction "IO_L16N_T2_16_A20") (pintype "bidirectional"))
      (node (ref "U4") (pin "7") (pinfunction "7_7") (pintype "passive"))
    )
    (net (code "120") (name "/B16_N_L17") (class "Default")
      (node (ref "U1") (pin "A19") (pinfunction "IO_L17N_T2_16_A19") (pintype "bidirectional"))
      (node (ref "U4") (pin "5") (pinfunction "5_5") (pintype "passive"))
    )
    (net (code "121") (name "/B16_N_L18") (class "Default")
      (node (ref "U1") (pin "F20") (pinfunction "IO_L18N_T2_16_F20") (pintype "bidirectional"))
      (node (ref "U4") (pin "20") (pinfunction "20_20") (pintype "passive"))
    )
    (net (code "122") (name "/B16_N_L19") (class "Default")
      (node (ref "U1") (pin "C20") (pinfunction "IO_L19N_T3_VREF_16_C20") (pintype "bidirectional"))
      (node (ref "U5") (pin "58") (pinfunction "58_58") (pintype "passive"))
    )
    (net (code "123") (name "/B16_N_L20") (class "Default")
      (node (ref "U1") (pin "B22") (pinfunction "IO_L20N_T3_16_B22") (pintype "bidirectional"))
      (node (ref "U4") (pin "6") (pinfunction "6_6") (pintype "passive"))
    )
    (net (code "124") (name "/B16_N_L21") (class "Default")
      (node (ref "U1") (pin "A21") (pinfunction "IO_L21N_T3_DQS_16_A21") (pintype "bidirectional"))
      (node (ref "U4") (pin "11") (pinfunction "11_11") (pintype "passive"))
    )
    (net (code "125") (name "/B16_N_L22") (class "Default")
      (node (ref "U1") (pin "D22") (pinfunction "IO_L22N_T3_16_D22") (pintype "bidirectional"))
      (node (ref "U4") (pin "14") (pinfunction "14_14") (pintype "passive"))
    )
    (net (code "126") (name "/B16_N_L23") (class "Default")
      (node (ref "U1") (pin "D21") (pinfunction "IO_L23N_T3_16_D21") (pintype "bidirectional"))
      (node (ref "U4") (pin "10") (pinfunction "10_10") (pintype "passive"))
    )
    (net (code "127") (name "/B16_N_L24") (class "Default")
      (node (ref "U1") (pin "G22") (pinfunction "IO_L24N_T3_16_G22") (pintype "bidirectional"))
      (node (ref "U4") (pin "19") (pinfunction "19_19") (pintype "passive"))
    )
    (net (code "128") (name "/B16_P_L1") (class "Default")
      (node (ref "U1") (pin "F13") (pinfunction "IO_L1P_T0_16_F13") (pintype "bidirectional"))
      (node (ref "U5") (pin "8") (pinfunction "8_8") (pintype "passive"))
    )
    (net (code "129") (name "/B16_P_L2") (class "Default")
      (node (ref "U1") (pin "F16") (pinfunction "IO_L2P_T0_16_F16") (pintype "bidirectional"))
      (node (ref "U5") (pin "24") (pinfunction "24_24") (pintype "passive"))
    )
    (net (code "130") (name "/B16_P_L3") (class "Default")
      (node (ref "U1") (pin "C14") (pinfunction "IO_L3P_T0_DQS_16_C14") (pintype "bidirectional"))
      (node (ref "U5") (pin "36") (pinfunction "36_36") (pintype "passive"))
    )
    (net (code "131") (name "/B16_P_L4") (class "Default")
      (node (ref "U1") (pin "E13") (pinfunction "IO_L4P_T0_16_E13") (pintype "bidirectional"))
      (node (ref "U5") (pin "12") (pinfunction "12_12") (pintype "passive"))
    )
    (net (code "132") (name "/B16_P_L5") (class "Default")
      (node (ref "U1") (pin "E16") (pinfunction "IO_L5P_T0_16_E16") (pintype "bidirectional"))
      (node (ref "U5") (pin "22") (pinfunction "22_22") (pintype "passive"))
    )
    (net (code "133") (name "/B16_P_L6") (class "Default")
      (node (ref "U1") (pin "D14") (pinfunction "IO_L6P_T0_16_D14") (pintype "bidirectional"))
      (node (ref "U5") (pin "16") (pinfunction "16_16") (pintype "passive"))
    )
    (net (code "134") (name "/B16_P_L7") (class "Default")
      (node (ref "U1") (pin "B15") (pinfunction "IO_L7P_T1_16_B15") (pintype "bidirectional"))
      (node (ref "U5") (pin "40") (pinfunction "40_40") (pintype "passive"))
    )
    (net (code "135") (name "/B16_P_L8") (class "Default")
      (node (ref "U1") (pin "C13") (pinfunction "IO_L8P_T1_16_C13") (pintype "bidirectional"))
      (node (ref "U5") (pin "34") (pinfunction "34_34") (pintype "passive"))
    )
    (net (code "136") (name "/B16_P_L9") (class "Default")
      (node (ref "U1") (pin "A15") (pinfunction "IO_L9P_T1_DQS_16_A15") (pintype "bidirectional"))
      (node (ref "U5") (pin "51") (pinfunction "51_51") (pintype "passive"))
    )
    (net (code "137") (name "/B16_P_L10") (class "Default")
      (node (ref "U1") (pin "A13") (pinfunction "IO_L10P_T1_16_A13") (pintype "bidirectional"))
      (node (ref "U5") (pin "47") (pinfunction "47_47") (pintype "passive"))
    )
    (net (code "138") (name "/B16_P_L11") (class "Default")
      (node (ref "U1") (pin "B17") (pinfunction "IO_L11P_T1_SRCC_16_B17") (pintype "bidirectional"))
      (node (ref "U5") (pin "48") (pinfunction "48_48") (pintype "passive"))
    )
    (net (code "139") (name "/B16_P_L12") (class "Default")
      (node (ref "U1") (pin "D17") (pinfunction "IO_L12P_T1_MRCC_16_D17") (pintype "bidirectional"))
      (node (ref "U5") (pin "44") (pinfunction "44_44") (pintype "passive"))
    )
    (net (code "140") (name "/B16_P_L13") (class "Default")
      (node (ref "U1") (pin "C18") (pinfunction "IO_L13P_T2_MRCC_16_C18") (pintype "bidirectional"))
      (node (ref "U5") (pin "52") (pinfunction "52_52") (pintype "passive"))
    )
    (net (code "141") (name "/B16_P_L14") (class "Default")
      (node (ref "U1") (pin "E19") (pinfunction "IO_L14P_T2_SRCC_16_E19") (pintype "bidirectional"))
      (node (ref "U5") (pin "30") (pinfunction "30_30") (pintype "passive"))
    )
    (net (code "142") (name "/B16_P_L15") (class "Default")
      (node (ref "U1") (pin "F18") (pinfunction "IO_L15P_T2_DQS_16_F18") (pintype "bidirectional"))
      (node (ref "U5") (pin "59") (pinfunction "59_59") (pintype "passive"))
    )
    (net (code "143") (name "/B16_P_L16") (class "Default")
      (node (ref "U1") (pin "B20") (pinfunction "IO_L16P_T2_16_B20") (pintype "bidirectional"))
      (node (ref "U4") (pin "9") (pinfunction "9_9") (pintype "passive"))
    )
    (net (code "144") (name "/B16_P_L17") (class "Default")
      (node (ref "U1") (pin "A18") (pinfunction "IO_L17P_T2_16_A18") (pintype "bidirectional"))
      (node (ref "U4") (pin "3") (pinfunction "3_3") (pintype "passive"))
    )
    (net (code "145") (name "/B16_P_L18") (class "Default")
      (node (ref "U1") (pin "F19") (pinfunction "IO_L18P_T2_16_F19") (pintype "bidirectional"))
      (node (ref "U4") (pin "18") (pinfunction "18_18") (pintype "passive"))
    )
    (net (code "146") (name "/B16_P_L19") (class "Default")
      (node (ref "U1") (pin "D20") (pinfunction "IO_L19P_T3_16_D20") (pintype "bidirectional"))
      (node (ref "U5") (pin "56") (pinfunction "56_56") (pintype "passive"))
    )
    (net (code "147") (name "/B16_P_L20") (class "Default")
      (node (ref "U1") (pin "C22") (pinfunction "IO_L20P_T3_16_C22") (pintype "bidirectional"))
      (node (ref "U4") (pin "8") (pinfunction "8_8") (pintype "passive"))
    )
    (net (code "148") (name "/B16_P_L21") (class "Default")
      (node (ref "U1") (pin "B21") (pinfunction "IO_L21P_T3_DQS_16_B21") (pintype "bidirectional"))
      (node (ref "U4") (pin "13") (pinfunction "13_13") (pintype "passive"))
    )
    (net (code "149") (name "/B16_P_L22") (class "Default")
      (node (ref "U1") (pin "E22") (pinfunction "IO_L22P_T3_16_E22") (pintype "bidirectional"))
      (node (ref "U4") (pin "16") (pinfunction "16_16") (pintype "passive"))
    )
    (net (code "150") (name "/B16_P_L23") (class "Default")
      (node (ref "U1") (pin "E21") (pinfunction "IO_L23P_T3_16_E21") (pintype "bidirectional"))
      (node (ref "U4") (pin "12") (pinfunction "12_12") (pintype "passive"))
    )
    (net (code "151") (name "/B16_P_L24") (class "Default")
      (node (ref "U1") (pin "G21") (pinfunction "IO_L24P_T3_16_G21") (pintype "bidirectional"))
      (node (ref "U4") (pin "17") (pinfunction "17_17") (pintype "passive"))
    )
    (net (code "152") (name "/B34_IO0") (class "Default")
      (node (ref "U1") (pin "T3") (pinfunction "IO_0_34_T3") (pintype "bidirectional"))
      (node (ref "U2") (pin "41") (pinfunction "41_41") (pintype "passive"))
    )
    (net (code "153") (name "/B34_IO25") (class "Default")
      (node (ref "U1") (pin "U7") (pinfunction "IO_25_34_U7") (pintype "bidirectional"))
      (node (ref "U2") (pin "58") (pinfunction "58_58") (pintype "passive"))
    )
    (net (code "154") (name "/B34_N_L1") (class "Default")
      (node (ref "U1") (pin "U1") (pinfunction "IO_L1N_T0_34_U1") (pintype "bidirectional"))
      (node (ref "U2") (pin "6") (pinfunction "6_6") (pintype "passive"))
    )
    (net (code "155") (name "/B34_N_L2") (class "Default")
      (node (ref "U1") (pin "V2") (pinfunction "IO_L2N_T0_34_V2") (pintype "bidirectional"))
      (node (ref "U2") (pin "3") (pinfunction "3_3") (pintype "passive"))
    )
    (net (code "156") (name "/B34_N_L3") (class "Default")
      (node (ref "U1") (pin "R2") (pinfunction "IO_L3N_T0_DQS_34_R2") (pintype "bidirectional"))
      (node (ref "U2") (pin "37") (pinfunction "37_37") (pintype "passive"))
    )
    (net (code "157") (name "/B34_N_L4") (class "Default")
      (node (ref "U1") (pin "Y2") (pinfunction "IO_L4N_T0_34_Y2") (pintype "bidirectional"))
      (node (ref "U2") (pin "11") (pinfunction "11_11") (pintype "passive"))
    )
    (net (code "158") (name "/B34_N_L5") (class "Default")
      (node (ref "U1") (pin "Y1") (pinfunction "IO_L5N_T0_34_Y1") (pintype "bidirectional"))
      (node (ref "U2") (pin "10") (pinfunction "10_10") (pintype "passive"))
    )
    (net (code "159") (name "/B34_N_L6") (class "Default")
      (node (ref "U1") (pin "V3") (pinfunction "IO_L6N_T0_VREF_34_V3") (pintype "bidirectional"))
      (node (ref "U2") (pin "7") (pinfunction "7_7") (pintype "passive"))
    )
    (net (code "160") (name "/B34_N_L7") (class "Default")
      (node (ref "U1") (pin "AB1") (pinfunction "IO_L7N_T1_34_AB1") (pintype "bidirectional"))
      (node (ref "U2") (pin "14") (pinfunction "14_14") (pintype "passive"))
    )
    (net (code "161") (name "/B34_N_L8") (class "Default")
      (node (ref "U1") (pin "AB2") (pinfunction "IO_L8N_T1_34_AB2") (pintype "bidirectional"))
      (node (ref "U2") (pin "16") (pinfunction "16_16") (pintype "passive"))
    )
    (net (code "162") (name "/B34_N_L9") (class "Default")
      (node (ref "U1") (pin "AA3") (pinfunction "IO_L9N_T1_DQS_34_AA3") (pintype "bidirectional"))
      (node (ref "U2") (pin "18") (pinfunction "18_18") (pintype "passive"))
    )
    (net (code "163") (name "/B34_N_L10") (class "Default")
      (node (ref "U1") (pin "AB5") (pinfunction "IO_L10N_T1_34_AB5") (pintype "bidirectional"))
      (node (ref "U2") (pin "26") (pinfunction "26_26") (pintype "passive"))
    )
    (net (code "164") (name "/B34_N_L11") (class "Default")
      (node (ref "U1") (pin "AA4") (pinfunction "IO_L11N_T1_SRCC_34_AA4") (pintype "bidirectional"))
      (node (ref "U2") (pin "22") (pinfunction "22_22") (pintype "passive"))
    )
    (net (code "165") (name "/B34_N_L12") (class "Default")
      (node (ref "U1") (pin "W4") (pinfunction "IO_L12N_T1_MRCC_34_W4") (pintype "bidirectional"))
      (node (ref "U2") (pin "17") (pinfunction "17_17") (pintype "passive"))
    )
    (net (code "166") (name "/B34_N_L13") (class "Default")
      (node (ref "U1") (pin "T4") (pinfunction "IO_L13N_T2_MRCC_34_T4") (pintype "bidirectional"))
      (node (ref "U2") (pin "46") (pinfunction "46_46") (pintype "passive"))
    )
    (net (code "167") (name "/B34_N_L14") (class "Default")
      (node (ref "U1") (pin "U5") (pinfunction "IO_L14N_T2_SRCC_34_U5") (pintype "bidirectional"))
      (node (ref "U2") (pin "50") (pinfunction "50_50") (pintype "passive"))
    )
    (net (code "168") (name "/B34_N_L15") (class "Default")
      (node (ref "U1") (pin "W5") (pinfunction "IO_L15N_T2_DQS_34_W5") (pintype "bidirectional"))
      (node (ref "U2") (pin "19") (pinfunction "19_19") (pintype "passive"))
    )
    (net (code "169") (name "/B34_N_L16") (class "Default")
      (node (ref "U1") (pin "V5") (pinfunction "IO_L16N_T2_34_V5") (pintype "bidirectional"))
      (node (ref "U2") (pin "54") (pinfunction "54_54") (pintype "passive"))
    )
    (net (code "170") (name "/B34_N_L17") (class "Default")
      (node (ref "U1") (pin "T6") (pinfunction "IO_L17N_T2_34_T6") (pintype "bidirectional"))
      (node (ref "U2") (pin "38") (pinfunction "38_38") (pintype "passive"))
    )
    (net (code "171") (name "/B34_N_L18") (class "Default")
      (node (ref "U1") (pin "AA6") (pinfunction "IO_L18N_T2_34_AA6") (pintype "bidirectional"))
      (node (ref "U2") (pin "28") (pinfunction "28_28") (pintype "passive"))
    )
    (net (code "172") (name "/B34_N_L19") (class "Default")
      (node (ref "U1") (pin "W7") (pinfunction "IO_L19N_T3_VREF_34_W7") (pintype "bidirectional"))
      (node (ref "U2") (pin "25") (pinfunction "25_25") (pintype "passive"))
    )
    (net (code "173") (name "/B34_N_L20") (class "Default")
      (node (ref "U1") (pin "AB6") (pinfunction "IO_L20N_T3_34_AB6") (pintype "bidirectional"))
      (node (ref "U2") (pin "30") (pinfunction "30_30") (pintype "passive"))
    )
    (net (code "174") (name "/B34_N_L21") (class "Default")
      (node (ref "U1") (pin "V8") (pinfunction "IO_L21N_T3_DQS_34_V8") (pintype "bidirectional"))
      (node (ref "U2") (pin "40") (pinfunction "40_40") (pintype "passive"))
    )
    (net (code "175") (name "/B34_N_L22") (class "Default")
      (node (ref "U1") (pin "AB8") (pinfunction "IO_L22N_T3_34_AB8") (pintype "bidirectional"))
      (node (ref "U2") (pin "35") (pinfunction "35_35") (pintype "passive"))
    )
    (net (code "176") (name "/B34_N_L23") (class "Default")
      (node (ref "U1") (pin "Y7") (pinfunction "IO_L23N_T3_34_Y7") (pintype "bidirectional"))
      (node (ref "U2") (pin "27") (pinfunction "27_27") (pintype "passive"))
    )
    (net (code "177") (name "/B34_N_L24") (class "Default")
      (node (ref "U1") (pin "Y9") (pinfunction "IO_L24N_T3_34_Y9") (pintype "bidirectional"))
      (node (ref "U2") (pin "33") (pinfunction "33_33") (pintype "passive"))
    )
    (net (code "178") (name "/B34_P_L1") (class "Default")
      (node (ref "U1") (pin "T1") (pinfunction "IO_L1P_T0_34_T1") (pintype "bidirectional"))
      (node (ref "U2") (pin "4") (pinfunction "4_4") (pintype "passive"))
    )
    (net (code "179") (name "/B34_P_L3") (class "Default")
      (node (ref "U1") (pin "R3") (pinfunction "IO_L3P_T0_DQS_34_R3") (pintype "bidirectional"))
      (node (ref "U2") (pin "39") (pinfunction "39_39") (pintype "passive"))
    )
    (net (code "180") (name "/B34_P_L4") (class "Default")
      (node (ref "U1") (pin "W2") (pinfunction "IO_L4P_T0_34_W2") (pintype "bidirectional"))
      (node (ref "U2") (pin "9") (pinfunction "9_9") (pintype "passive"))
    )
    (net (code "181") (name "/B34_P_L5") (class "Default")
      (node (ref "U1") (pin "W1") (pinfunction "IO_L5P_T0_34_W1") (pintype "bidirectional"))
      (node (ref "U2") (pin "8") (pinfunction "8_8") (pintype "passive"))
    )
    (net (code "182") (name "/B34_P_L6") (class "Default")
      (node (ref "U1") (pin "U3") (pinfunction "IO_L6P_T0_34_U3") (pintype "bidirectional"))
      (node (ref "U2") (pin "5") (pinfunction "5_5") (pintype "passive"))
    )
    (net (code "183") (name "/B34_P_L7") (class "Default")
      (node (ref "U1") (pin "AA1") (pinfunction "IO_L7P_T1_34_AA1") (pintype "bidirectional"))
      (node (ref "U2") (pin "12") (pinfunction "12_12") (pintype "passive"))
    )
    (net (code "184") (name "/B34_P_L8") (class "Default")
      (node (ref "U1") (pin "AB3") (pinfunction "IO_L8P_T1_34_AB3") (pintype "bidirectional"))
      (node (ref "U2") (pin "20") (pinfunction "20_20") (pintype "passive"))
    )
    (net (code "185") (name "/B34_P_L9") (class "Default")
      (node (ref "U1") (pin "Y3") (pinfunction "IO_L9P_T1_DQS_34_Y3") (pintype "bidirectional"))
      (node (ref "U2") (pin "13") (pinfunction "13_13") (pintype "passive"))
    )
    (net (code "186") (name "/B34_P_L10") (class "Default")
      (node (ref "U1") (pin "AA5") (pinfunction "IO_L10P_T1_34_AA5") (pintype "bidirectional"))
      (node (ref "U2") (pin "24") (pinfunction "24_24") (pintype "passive"))
    )
    (net (code "187") (name "/B34_P_L11") (class "Default")
      (node (ref "U1") (pin "Y4") (pinfunction "IO_L11P_T1_SRCC_34_Y4") (pintype "bidirectional"))
      (node (ref "U2") (pin "15") (pinfunction "15_15") (pintype "passive"))
    )
    (net (code "188") (name "/B34_P_L12") (class "Default")
      (node (ref "U1") (pin "V4") (pinfunction "IO_L12P_T1_MRCC_34_V4") (pintype "bidirectional"))
      (node (ref "U2") (pin "52") (pinfunction "52_52") (pintype "passive"))
    )
    (net (code "189") (name "/B34_P_L14") (class "Default")
      (node (ref "U1") (pin "T5") (pinfunction "IO_L14P_T2_SRCC_34_T5") (pintype "bidirectional"))
      (node (ref "U2") (pin "48") (pinfunction "48_48") (pintype "passive"))
    )
    (net (code "190") (name "/B34_P_L15") (class "Default")
      (node (ref "U1") (pin "W6") (pinfunction "IO_L15P_T2_DQS_34_W6") (pintype "bidirectional"))
      (node (ref "U2") (pin "21") (pinfunction "21_21") (pintype "passive"))
    )
    (net (code "191") (name "/B34_P_L16") (class "Default")
      (node (ref "U1") (pin "U6") (pinfunction "IO_L16P_T2_34_U6") (pintype "bidirectional"))
      (node (ref "U2") (pin "56") (pinfunction "56_56") (pintype "passive"))
    )
    (net (code "192") (name "/B34_P_L17") (class "Default")
      (node (ref "U1") (pin "R6") (pinfunction "IO_L17P_T2_34_R6") (pintype "bidirectional"))
      (node (ref "U2") (pin "36") (pinfunction "36_36") (pintype "passive"))
    )
    (net (code "193") (name "/B34_P_L18") (class "Default")
      (node (ref "U1") (pin "Y6") (pinfunction "IO_L18P_T2_34_Y6") (pintype "bidirectional"))
      (node (ref "U2") (pin "23") (pinfunction "23_23") (pintype "passive"))
    )
    (net (code "194") (name "/B34_P_L19") (class "Default")
      (node (ref "U1") (pin "V7") (pinfunction "IO_L19P_T3_34_V7") (pintype "bidirectional"))
      (node (ref "U2") (pin "60") (pinfunction "60_60") (pintype "passive"))
    )
    (net (code "195") (name "/B34_P_L20") (class "Default")
      (node (ref "U1") (pin "AB7") (pinfunction "IO_L20P_T3_34_AB7") (pintype "bidirectional"))
      (node (ref "U2") (pin "32") (pinfunction "32_32") (pintype "passive"))
    )
    (net (code "196") (name "/B34_P_L21") (class "Default")
      (node (ref "U1") (pin "V9") (pinfunction "IO_L21P_T3_DQS_34_V9") (pintype "bidirectional"))
      (node (ref "U2") (pin "42") (pinfunction "42_42") (pintype "passive"))
    )
    (net (code "197") (name "/B34_P_L22") (class "Default")
      (node (ref "U1") (pin "AA8") (pinfunction "IO_L22P_T3_34_AA8") (pintype "bidirectional"))
      (node (ref "U2") (pin "34") (pinfunction "34_34") (pintype "passive"))
    )
    (net (code "198") (name "/B34_P_L23") (class "Default")
      (node (ref "U1") (pin "Y8") (pinfunction "IO_L23P_T3_34_Y8") (pintype "bidirectional"))
      (node (ref "U2") (pin "29") (pinfunction "29_29") (pintype "passive"))
    )
    (net (code "199") (name "/B34_P_L24") (class "Default")
      (node (ref "U1") (pin "W9") (pinfunction "IO_L24P_T3_34_W9") (pintype "bidirectional"))
      (node (ref "U2") (pin "31") (pinfunction "31_31") (pintype "passive"))
    )
    (net (code "200") (name "/DDR3_A0") (class "Default")
      (node (ref "U1") (pin "P2") (pinfunction "IO_L22P_T3_35_P2") (pintype "bidirectional"))
      (node (ref "U9") (pin "N3") (pinfunction "A0_N3") (pintype "passive"))
    )
    (net (code "201") (name "/DDR3_A1") (class "Default")
      (node (ref "U1") (pin "K3") (pinfunction "IO_L14N_T2_SRCC_35_K3") (pintype "bidirectional"))
      (node (ref "U9") (pin "P7") (pinfunction "A1_P7") (pintype "passive"))
    )
    (net (code "202") (name "/DDR3_A2") (class "Default")
      (node (ref "U1") (pin "N5") (pinfunction "IO_L24N_T3_35_N5") (pintype "bidirectional"))
      (node (ref "U9") (pin "P3") (pinfunction "A2_P3") (pintype "passive"))
    )
    (net (code "203") (name "/DDR3_A3") (class "Default")
      (node (ref "U1") (pin "M6") (pinfunction "IO_L23P_T3_35_M6") (pintype "bidirectional"))
      (node (ref "U9") (pin "N2") (pinfunction "A3_N2") (pintype "passive"))
    )
    (net (code "204") (name "/DDR3_A4") (class "Default")
      (node (ref "U1") (pin "M2") (pinfunction "IO_L16N_T2_35_M2") (pintype "bidirectional"))
      (node (ref "U9") (pin "P8") (pinfunction "A4_P8") (pintype "passive"))
    )
    (net (code "205") (name "/DDR3_A5") (class "Default")
      (node (ref "U1") (pin "N3") (pinfunction "IO_L19N_T3_VREF_35_N3") (pintype "bidirectional"))
      (node (ref "U9") (pin "P2") (pinfunction "A5_P2") (pintype "passive"))
    )
    (net (code "206") (name "/DDR3_A6") (class "Default")
      (node (ref "U1") (pin "M3") (pinfunction "IO_L16P_T2_35_M3") (pintype "bidirectional"))
      (node (ref "U9") (pin "R8") (pinfunction "A6_R8") (pintype "passive"))
    )
    (net (code "207") (name "/DDR3_A7") (class "Default")
      (node (ref "U1") (pin "N4") (pinfunction "IO_L19P_T3_35_N4") (pintype "bidirectional"))
      (node (ref "U9") (pin "R2") (pinfunction "A7_R2") (pintype "passive"))
    )
    (net (code "208") (name "/DDR3_A8") (class "Default")
      (node (ref "U1") (pin "L3") (pinfunction "IO_L14P_T2_SRCC_35_L3") (pintype "bidirectional"))
      (node (ref "U9") (pin "T8") (pinfunction "A8_T8") (pintype "passive"))
    )
    (net (code "209") (name "/DDR3_A9") (class "Default")
      (node (ref "U1") (pin "P6") (pinfunction "IO_L24P_T3_35_P6") (pintype "bidirectional"))
      (node (ref "U9") (pin "R3") (pinfunction "A9_R3") (pintype "passive"))
    )
    (net (code "210") (name "/DDR3_A10") (class "Default")
      (node (ref "U1") (pin "L4") (pinfunction "IO_L18N_T2_35_L4") (pintype "bidirectional"))
      (node (ref "U9") (pin "L7") (pinfunction "A10AP_L7") (pintype "passive"))
    )
    (net (code "211") (name "/DDR3_A11") (class "Default")
      (node (ref "U1") (pin "J6") (pinfunction "IO_L17N_T2_35_J6") (pintype "bidirectional"))
      (node (ref "U9") (pin "R7") (pinfunction "A11_R7") (pintype "passive"))
    )
    (net (code "212") (name "/DDR3_A12") (class "Default")
      (node (ref "U1") (pin "L5") (pinfunction "IO_L18P_T2_35_L5") (pintype "bidirectional"))
      (node (ref "U9") (pin "N7") (pinfunction "A12BC#_N7") (pintype "passive"))
    )
    (net (code "213") (name "/DDR3_A13") (class "Default")
      (node (ref "U1") (pin "K6") (pinfunction "IO_L17P_T2_35_K6") (pintype "bidirectional"))
      (node (ref "U9") (pin "T3") (pinfunction "A13_T3") (pintype "passive"))
    )
    (net (code "214") (name "/DDR3_BA0") (class "Default")
      (node (ref "U1") (pin "N2") (pinfunction "IO_L22N_T3_35_N2") (pintype "bidirectional"))
      (node (ref "U9") (pin "M2") (pinfunction "BA0_M2") (pintype "passive"))
    )
    (net (code "215") (name "/DDR3_BA1") (class "Default")
      (node (ref "U1") (pin "L1") (pinfunction "IO_L15N_T2_DQS_35_L1") (pintype "bidirectional"))
      (node (ref "U9") (pin "N8") (pinfunction "BA1_N8") (pintype "passive"))
    )
    (net (code "216") (name "/DDR3_BA2") (class "Default")
      (node (ref "U1") (pin "M5") (pinfunction "IO_L23N_T3_35_M5") (pintype "bidirectional"))
      (node (ref "U9") (pin "M3") (pinfunction "BA2_M3") (pintype "passive"))
    )
    (net (code "217") (name "/DDR3_CAS_N") (class "Default")
      (node (ref "U1") (pin "R1") (pinfunction "IO_L20P_T3_35_R1") (pintype "bidirectional"))
      (node (ref "U9") (pin "K3") (pinfunction "CAS#_K3") (pintype "passive"))
    )
    (net (code "218") (name "/DDR3_CKE") (class "Default")
      (node (ref "R29") (pin "1") (pinfunction "1_1") (pintype "passive"))
      (node (ref "U1") (pin "K4") (pinfunction "IO_L13P_T2_MRCC_35_K4") (pintype "bidirectional"))
      (node (ref "U9") (pin "K9") (pinfunction "CKE_K9") (pintype "passive"))
    )
    (net (code "219") (name "/DDR3_CLK_N") (class "Default")
      (node (ref "R25") (pin "1") (pinfunction "1_1") (pintype "passive"))
      (node (ref "U1") (pin "P4") (pinfunction "IO_L21N_T3_DQS_35_P4") (pintype "bidirectional"))
      (node (ref "U9") (pin "K7") (pinfunction "CK#_K7") (pintype "passive"))
    )
    (net (code "220") (name "/DDR3_CLK_P") (class "Default")
      (node (ref "R25") (pin "2") (pinfunction "2_2") (pintype "passive"))
      (node (ref "U1") (pin "P5") (pinfunction "IO_L21P_T3_DQS_35_P5") (pintype "bidirectional"))
      (node (ref "U9") (pin "J7") (pinfunction "CK_J7") (pintype "passive"))
    )
    (net (code "221") (name "/DDR3_CS_N") (class "Default")
      (node (ref "R28") (pin "1") (pinfunction "1_1") (pintype "passive"))
      (node (ref "U1") (pin "L6") (pinfunction "IO_25_35_L6") (pintype "bidirectional"))
      (node (ref "U9") (pin "L2") (pinfunction "CS#_L2") (pintype "passive"))
    )
    (net (code "222") (name "/DDR3_DQ0") (class "Default")
      (node (ref "U1") (pin "H4") (pinfunction "IO_L12P_T1_MRCC_35_H4") (pintype "bidirectional"))
      (node (ref "U9") (pin "E3") (pinfunction "DQ0_E3") (pintype "passive"))
    )
    (net (code "223") (name "/DDR3_DQ1") (class "Default")
      (node (ref "U1") (pin "G2") (pinfunction "IO_L8N_T1_AD14N_35_G2") (pintype "bidirectional"))
      (node (ref "U9") (pin "F7") (pinfunction "DQ1_F7") (pintype "passive"))
    )
    (net (code "224") (name "/DDR3_DQ2") (class "Default")
      (node (ref "U1") (pin "H2") (pinfunction "IO_L8P_T1_AD14P_35_H2") (pintype "bidirectional"))
      (node (ref "U9") (pin "F2") (pinfunction "DQ2_F2") (pintype "passive"))
    )
    (net (code "225") (name "/DDR3_DQ3") (class "Default")
      (node (ref "U1") (pin "K1") (pinfunction "IO_L7P_T1_AD6P_35_K1") (pintype "bidirectional"))
      (node (ref "U9") (pin "F8") (pinfunction "DQ3_F8") (pintype "passive"))
    )
    (net (code "226") (name "/DDR3_DQ4") (class "Default")
      (node (ref "U1") (pin "J5") (pinfunction "IO_L10P_T1_AD15P_35_J5") (pintype "bidirectional"))
      (node (ref "U9") (pin "H3") (pinfunction "DQ4_H3") (pintype "passive"))
    )
    (net (code "227") (name "/DDR3_DQ5") (class "Default")
      (node (ref "U1") (pin "H3") (pinfunction "IO_L11P_T1_SRCC_35_H3") (pintype "bidirectional"))
      (node (ref "U9") (pin "H8") (pinfunction "DQ5_H8") (pintype "passive"))
    )
    (net (code "228") (name "/DDR3_DQ6") (class "Default")
      (node (ref "U1") (pin "H5") (pinfunction "IO_L10N_T1_AD15N_35_H5") (pintype "bidirectional"))
      (node (ref "U9") (pin "G2") (pinfunction "DQ6_G2") (pintype "passive"))
    )
    (net (code "229") (name "/DDR3_DQ7") (class "Default")
      (node (ref "U1") (pin "G3") (pinfunction "IO_L11N_T1_SRCC_35_G3") (pintype "bidirectional"))
      (node (ref "U9") (pin "H7") (pinfunction "DQ7_H7") (pintype "passive"))
    )
    (net (code "230") (name "/DDR3_DQ8") (class "Default")
      (node (ref "U1") (pin "B2") (pinfunction "IO_L2N_T0_AD12N_35_B2") (pintype "bidirectional"))
      (node (ref "U9") (pin "D7") (pinfunction "DQ8_D7") (pintype "passive"))
    )
    (net (code "231") (name "/DDR3_DQ9") (class "Default")
      (node (ref "U1") (pin "F1") (pinfunction "IO_L5N_T0_AD13N_35_F1") (pintype "bidirectional"))
      (node (ref "U9") (pin "C3") (pinfunction "DQ9_C3") (pintype "passive"))
    )
    (net (code "232") (name "/DDR3_DQ10") (class "Default")
      (node (ref "U1") (pin "A1") (pinfunction "IO_L1N_T0_AD4N_35_A1") (pintype "bidirectional"))
      (node (ref "U9") (pin "C8") (pinfunction "DQ10_C8") (pintype "passive"))
    )
    (net (code "233") (name "/DDR3_DQ11") (class "Default")
      (node (ref "U1") (pin "D2") (pinfunction "IO_L4N_T0_35_D2") (pintype "bidirectional"))
      (node (ref "U9") (pin "C2") (pinfunction "DQ11_C2") (pintype "passive"))
    )
    (net (code "234") (name "/DDR3_DQ12") (class "Default")
      (node (ref "U1") (pin "B1") (pinfunction "IO_L1P_T0_AD4P_35_B1") (pintype "bidirectional"))
      (node (ref "U9") (pin "A7") (pinfunction "DQ12_A7") (pintype "passive"))
    )
    (net (code "235") (name "/DDR3_DQ13") (class "Default")
      (node (ref "U1") (pin "G1") (pinfunction "IO_L5P_T0_AD13P_35_G1") (pintype "bidirectional"))
      (node (ref "U9") (pin "A2") (pinfunction "DQ13_A2") (pintype "passive"))
    )
    (net (code "236") (name "/DDR3_DQ14") (class "Default")
      (node (ref "U1") (pin "C2") (pinfunction "IO_L2P_T0_AD12P_35_C2") (pintype "bidirectional"))
      (node (ref "U9") (pin "B8") (pinfunction "DQ14_B8") (pintype "passive"))
    )
    (net (code "237") (name "/DDR3_DQ15") (class "Default")
      (node (ref "U1") (pin "F3") (pinfunction "IO_L6P_T0_35_F3") (pintype "bidirectional"))
      (node (ref "U9") (pin "A3") (pinfunction "DQ15_A3") (pintype "passive"))
    )
    (net (code "238") (name "/DDR3_DQS_N0") (class "Default")
      (node (ref "U1") (pin "J2") (pinfunction "IO_L9N_T1_DQS_AD7N_35_J2") (pintype "bidirectional"))
      (node (ref "U9") (pin "G3") (pinfunction "LDQS#_G3") (pintype "passive"))
    )
    (net (code "239") (name "/DDR3_DQS_N1") (class "Default")
      (node (ref "U1") (pin "D1") (pinfunction "IO_L3N_T0_DQS_AD5N_35_D1") (pintype "bidirectional"))
      (node (ref "U9") (pin "B7") (pinfunction "UDQS#_B7") (pintype "passive"))
    )
    (net (code "240") (name "/DDR3_DQS_P0") (class "Default")
      (node (ref "U1") (pin "K2") (pinfunction "IO_L9P_T1_DQS_AD7P_35_K2") (pintype "bidirectional"))
      (node (ref "U9") (pin "F3") (pinfunction "LDQS_F3") (pintype "passive"))
    )
    (net (code "241") (name "/DDR3_DQS_P1") (class "Default")
      (node (ref "U1") (pin "E1") (pinfunction "IO_L3P_T0_DQS_AD5P_35_E1") (pintype "bidirectional"))
      (node (ref "U9") (pin "C7") (pinfunction "UDQS_C7") (pintype "passive"))
    )
    (net (code "242") (name "/DDR3_LDM") (class "Default")
      (node (ref "U1") (pin "J1") (pinfunction "IO_L7N_T1_AD6N_35_J1") (pintype "bidirectional"))
      (node (ref "U9") (pin "E7") (pinfunction "LDM_E7") (pintype "passive"))
    )
    (net (code "243") (name "/DDR3_ODT") (class "Default")
      (node (ref "R35") (pin "1") (pinfunction "1_1") (pintype "passive"))
      (node (ref "U1") (pin "P1") (pinfunction "IO_L20N_T3_35_P1") (pintype "bidirectional"))
      (node (ref "U9") (pin "K1") (pinfunction "OUT_K1") (pintype "passive"))
    )
    (net (code "244") (name "/DDR3_RAS_N") (class "Default")
      (node (ref "U1") (pin "J4") (pinfunction "IO_L13N_T2_MRCC_35_J4") (pintype "bidirectional"))
      (node (ref "U9") (pin "J3") (pinfunction "RAS#_J3") (pintype "passive"))
    )
    (net (code "245") (name "/DDR3_RESET_N") (class "Default")
      (node (ref "R24") (pin "1") (pinfunction "1_1") (pintype "passive"))
      (node (ref "U1") (pin "F4") (pinfunction "IO_0_35_F4") (pintype "bidirectional"))
      (node (ref "U9") (pin "T2") (pinfunction "RESET#_T2") (pintype "passive"))
    )
    (net (code "246") (name "/DDR3_UDM") (class "Default")
      (node (ref "U1") (pin "E2") (pinfunction "IO_L4P_T0_35_E2") (pintype "bidirectional"))
      (node (ref "U9") (pin "D3") (pinfunction "UDM_D3") (pintype "passive"))
    )
    (net (code "247") (name "/DDR3_WE_N") (class "Default")
      (node (ref "U1") (pin "M1") (pinfunction "IO_L15P_T2_DQS_35_M1") (pintype "bidirectional"))
      (node (ref "U9") (pin "L3") (pinfunction "WE#_L3") (pintype "passive"))
    )
    (net (code "248") (name "/FPGA_DONE") (class "Default")
      (node (ref "LED1") (pin "1") (pinfunction "A_1") (pintype "passive"))
      (node (ref "R12") (pin "2") (pinfunction "2_2") (pintype "passive"))
      (node (ref "U1") (pin "G11") (pinfunction "DONE_0_G11") (pintype "bidirectional"))
    )
    (net (code "249") (name "/FPGA_GCLK") (class "Default")
      (node (ref "U1") (pin "R4") (pinfunction "IO_L13P_T2_MRCC_34_R4") (pintype "bidirectional"))
      (node (ref "X1") (pin "3") (pinfunction "OUT_3") (pintype "passive"))
    )
    (net (code "250") (name "/FPGA_M0") (class "Default")
      (node (ref "R9") (pin "2") (pinfunction "2_2") (pintype "passive"))
      (node (ref "U1") (pin "U11") (pinfunction "M0_0_U11") (pintype "input"))
    )
    (net (code "251") (name "/FPGA_M1") (class "Default")
      (node (ref "R10") (pin "2") (pinfunction "2_2") (pintype "passive"))
      (node (ref "U1") (pin "U10") (pinfunction "M1_0_U10") (pintype "input"))
    )
    (net (code "252") (name "/FPGA_M2") (class "Default")
      (node (ref "R11") (pin "2") (pinfunction "2_2") (pintype "passive"))
      (node (ref "U1") (pin "U9") (pinfunction "M2_0_U9") (pintype "input"))
    )
    (net (code "253") (name "/FPGA_PROG_B") (class "Default")
      (node (ref "R15") (pin "2") (pinfunction "2_2") (pintype "passive"))
      (node (ref "U1") (pin "N12") (pinfunction "PROGRAM_B_0_N12") (pintype "input"))
    )
    (net (code "254") (name "/FPGA_TCK") (class "Default")
      (node (ref "R19") (pin "1") (pinfunction "1_1") (pintype "passive"))
      (node (ref "U1") (pin "V12") (pinfunction "TCK_0_V12") (pintype "input"))
      (node (ref "U3") (pin "3") (pinfunction "3_3") (pintype "passive"))
    )
    (net (code "255") (name "/FPGA_TDI") (class "Default")
      (node (ref "R23") (pin "1") (pinfunction "1_1") (pintype "passive"))
      (node (ref "U1") (pin "R13") (pinfunction "TDI_0_R13") (pintype "input"))
      (node (ref "U3") (pin "9") (pinfunction "9_9") (pintype "passive"))
    )
    (net (code "256") (name "/FPGA_TDO") (class "Default")
      (node (ref "R20") (pin "1") (pinfunction "1_1") (pintype "passive"))
      (node (ref "U1") (pin "U13") (pinfunction "TDO_0_U13") (pintype "output"))
      (node (ref "U3") (pin "5") (pinfunction "5_5") (pintype "passive"))
    )
    (net (code "257") (name "/FPGA_TMS") (class "Default")
      (node (ref "R22") (pin "1") (pinfunction "1_1") (pintype "passive"))
      (node (ref "U1") (pin "T13") (pinfunction "TMS_0_T13") (pintype "input"))
      (node (ref "U3") (pin "7") (pinfunction "7_7") (pintype "passive"))
    )
    (net (code "258") (name "/MGT_CLK0_N") (class "Default")
      (node (ref "U1") (pin "E6") (pinfunction "MGTREFCLK0N_216_E6") (pintype "input"))
      (node (ref "U5") (pin "11") (pinfunction "11_11") (pintype "passive"))
    )
    (net (code "259") (name "/MGT_CLK0_P") (class "Default")
      (node (ref "U1") (pin "F6") (pinfunction "MGTREFCLK0P_216_F6") (pintype "input"))
      (node (ref "U5") (pin "13") (pinfunction "13_13") (pintype "passive"))
    )
    (net (code "260") (name "/MGT_CLK1_N") (class "Default")
      (node (ref "U1") (pin "E10") (pinfunction "MGTREFCLK1N_216_E10") (pintype "input"))
      (node (ref "U5") (pin "23") (pinfunction "23_23") (pintype "passive"))
    )
    (net (code "261") (name "/MGT_CLK1_P") (class "Default")
      (node (ref "U1") (pin "F10") (pinfunction "MGTREFCLK1P_216_F10") (pintype "input"))
      (node (ref "U5") (pin "25") (pinfunction "25_25") (pintype "passive"))
    )
    (net (code "262") (name "/MGT_RX_N_0") (class "Default")
      (node (ref "U1") (pin "A8") (pinfunction "MGTPRXN0_216_A8") (pintype "input"))
      (node (ref "U5") (pin "41") (pinfunction "41_41") (pintype "passive"))
    )
    (net (code "263") (name "/MGT_RX_N_1") (class "Default")
      (node (ref "U1") (pin "C11") (pinfunction "MGTPRXN1_216_C11") (pintype "input"))
      (node (ref "U5") (pin "27") (pinfunction "27_27") (pintype "passive"))
    )
    (net (code "264") (name "/MGT_RX_N_2") (class "Default")
      (node (ref "U1") (pin "A10") (pinfunction "MGTPRXN2_216_A10") (pintype "input"))
      (node (ref "U5") (pin "45") (pinfunction "45_45") (pintype "passive"))
    )
    (net (code "265") (name "/MGT_RX_N_3") (class "Default")
      (node (ref "U1") (pin "C9") (pinfunction "MGTPRXN3_216_C9") (pintype "input"))
      (node (ref "U5") (pin "19") (pinfunction "19_19") (pintype "passive"))
    )
    (net (code "266") (name "/MGT_RX_P_0") (class "Default")
      (node (ref "U1") (pin "B8") (pinfunction "MGTPRXP0_216_B8") (pintype "input"))
      (node (ref "U5") (pin "39") (pinfunction "39_39") (pintype "passive"))
    )
    (net (code "267") (name "/MGT_RX_P_1") (class "Default")
      (node (ref "U1") (pin "D11") (pinfunction "MGTPRXP1_216_D11") (pintype "input"))
      (node (ref "U5") (pin "29") (pinfunction "29_29") (pintype "passive"))
    )
    (net (code "268") (name "/MGT_RX_P_2") (class "Default")
      (node (ref "U1") (pin "B10") (pinfunction "MGTPRXP2_216_B10") (pintype "input"))
      (node (ref "U5") (pin "43") (pinfunction "43_43") (pintype "passive"))
    )
    (net (code "269") (name "/MGT_RX_P_3") (class "Default")
      (node (ref "U1") (pin "D9") (pinfunction "MGTPRXP3_216_D9") (pintype "input"))
      (node (ref "U5") (pin "21") (pinfunction "21_21") (pintype "passive"))
    )
    (net (code "270") (name "/MGT_TX_N_0") (class "Default")
      (node (ref "U1") (pin "A4") (pinfunction "MGTPTXN0_216_A4") (pintype "output"))
      (node (ref "U5") (pin "33") (pinfunction "33_33") (pintype "passive"))
    )
    (net (code "271") (name "/MGT_TX_N_1") (class "Default")
      (node (ref "U1") (pin "C5") (pinfunction "MGTPTXN1_216_C5") (pintype "output"))
      (node (ref "U5") (pin "7") (pinfunction "7_7") (pintype "passive"))
    )
    (net (code "272") (name "/MGT_TX_N_2") (class "Default")
      (node (ref "U1") (pin "A6") (pinfunction "MGTPTXN2_216_A6") (pintype "output"))
      (node (ref "U5") (pin "37") (pinfunction "37_37") (pintype "passive"))
    )
    (net (code "273") (name "/MGT_TX_N_3") (class "Default")
      (node (ref "U1") (pin "C7") (pinfunction "MGTPTXN3_216_C7") (pintype "output"))
      (node (ref "U5") (pin "15") (pinfunction "15_15") (pintype "passive"))
    )
    (net (code "274") (name "/MGT_TX_P_0") (class "Default")
      (node (ref "U1") (pin "B4") (pinfunction "MGTPTXP0_216_B4") (pintype "output"))
      (node (ref "U5") (pin "31") (pinfunction "31_31") (pintype "passive"))
    )
    (net (code "275") (name "/MGT_TX_P_1") (class "Default")
      (node (ref "U1") (pin "D5") (pinfunction "MGTPTXP1_216_D5") (pintype "output"))
      (node (ref "U5") (pin "9") (pinfunction "9_9") (pintype "passive"))
    )
    (net (code "276") (name "/MGT_TX_P_2") (class "Default")
      (node (ref "U1") (pin "B6") (pinfunction "MGTPTXP2_216_B6") (pintype "output"))
      (node (ref "U5") (pin "35") (pinfunction "35_35") (pintype "passive"))
    )
    (net (code "277") (name "/MGT_TX_P_3") (class "Default")
      (node (ref "U1") (pin "D7") (pinfunction "MGTPTXP3_216_D7") (pintype "output"))
      (node (ref "U5") (pin "17") (pinfunction "17_17") (pintype "passive"))
    )
    (net (code "278") (name "/QSPI_CLK") (class "Default")
      (node (ref "R21") (pin "2") (pinfunction "2_2") (pintype "passive"))
      (node (ref "U1") (pin "L12") (pinfunction "CCLK_0_L12") (pintype "bidirectional"))
    )
    (net (code "279") (name "/QSPI_CS") (class "Default")
      (node (ref "R17") (pin "1") (pinfunction "1_1") (pintype "passive"))
      (node (ref "U1") (pin "T19") (pinfunction "IO_L6P_T0_FCS_B_14_T19") (pintype "bidirectional"))
      (node (ref "U8") (pin "1") (pinfunction "CS#_1") (pintype "passive"))
    )
    (net (code "280") (name "/QSPI_D0") (class "Default")
      (node (ref "U1") (pin "P22") (pinfunction "IO_L1P_T0_D00_MOSI_14_P22") (pintype "bidirectional"))
      (node (ref "U8") (pin "5") (pinfunction "DI(IO0)_5") (pintype "passive"))
    )
    (net (code "281") (name "/QSPI_D1") (class "Default")
      (node (ref "U1") (pin "R22") (pinfunction "IO_L1N_T0_D01_DIN_14_R22") (pintype "bidirectional"))
      (node (ref "U8") (pin "2") (pinfunction "DO(IO1)_2") (pintype "passive"))
    )
    (net (code "282") (name "/QSPI_D2") (class "Default")
      (node (ref "R16") (pin "1") (pinfunction "1_1") (pintype "passive"))
      (node (ref "U1") (pin "P21") (pinfunction "IO_L2P_T0_D02_14_P21") (pintype "bidirectional"))
      (node (ref "U8") (pin "3") (pinfunction "WP#(IO2)_3") (pintype "passive"))
    )
    (net (code "283") (name "/QSPI_D3") (class "Default")
      (node (ref "R18") (pin "1") (pinfunction "1_1") (pintype "passive"))
      (node (ref "U1") (pin "R21") (pinfunction "IO_L2N_T0_D03_14_R21") (pintype "bidirectional"))
      (node (ref "U8") (pin "7") (pinfunction "HOLD#orRESET#(IO3)_7") (pintype "passive"))
    )
    (net (code "284") (name "/RESET") (class "Default")
      (node (ref "R8") (pin "1") (pinfunction "1_1") (pintype "passive"))
      (node (ref "SW1") (pin "2") (pinfunction "2_2") (pintype "passive"))
      (node (ref "U1") (pin "U2") (pinfunction "IO_L2P_T0_34_U2") (pintype "bidirectional"))
      (node (ref "U2") (pin "44") (pinfunction "44_44") (pintype "passive"))
    )
    (net (code "285") (name "/XADC_V_N") (class "Default")
      (node (ref "U1") (pin "M9") (pinfunction "VN_0_M9") (pintype "input"))
      (node (ref "U5") (pin "2") (pinfunction "2_2") (pintype "passive"))
    )
    (net (code "286") (name "/XADC_V_P") (class "Default")
      (node (ref "U1") (pin "L10") (pinfunction "VP_0_L10") (pintype "input"))
      (node (ref "U5") (pin "4") (pinfunction "4_4") (pintype "passive"))
    )
    (net (code "287") (name "AGND") (class "Default")
      (node (ref "FB1") (pin "1") (pinfunction "1_1") (pintype "passive"))
      (node (ref "U1") (pin "K9") (pinfunction "GNDADC_0_K9") (pintype "power_in"))
      (node (ref "U1") (pin "L9") (pinfunction "VREFN_0_L9") (pintype "input"))
      (node (ref "U1") (pin "M10") (pinfunction "VREFP_0_M10") (pintype "input"))
    )
    (net (code "288") (name "DDR3_VREF") (class "Default")
      (node (ref "C100") (pin "2") (pinfunction "2_2") (pintype "passive"))
      (node (ref "C113") (pin "2") (pinfunction "2_2") (pintype "passive"))
      (node (ref "C96") (pin "1") (pinfunction "1_1") (pintype "passive"))
      (node (ref "R26") (pin "1") (pinfunction "1_1") (pintype "passive"))
      (node (ref "R30") (pin "2") (pinfunction "2_2") (pintype "passive"))
      (node (ref "U9") (pin "H1") (pinfunction "VDD_H1") (pintype "passive"))
      (node (ref "U9") (pin "M8") (pinfunction "VDD_M8") (pintype "passive"))
    )
    (net (code "289") (name "GND") (class "Default")
      (node (ref "C1") (pin "2") (pinfunction "2_2") (pintype "passive"))
      (node (ref "C10") (pin "2") (pinfunction "2_2") (pintype "passive"))
      (node (ref "C100") (pin "1") (pinfunction "1_1") (pintype "passive"))
      (node (ref "C102") (pin "1") (pinfunction "1_1") (pintype "passive"))
      (node (ref "C103") (pin "2") (pinfunction "2_2") (pintype "passive"))
      (node (ref "C104") (pin "2") (pinfunction "2_2") (pintype "passive"))
      (node (ref "C106") (pin "1") (pinfunction "1_1") (pintype "passive"))
      (node (ref "C107") (pin "1") (pinfunction "1_1") (pintype "passive"))
      (node (ref "C108") (pin "1") (pinfunction "1_1") (pintype "passive"))
      (node (ref "C109") (pin "2") (pinfunction "2_2") (pintype "passive"))
      (node (ref "C11") (pin "2") (pinfunction "2_2") (pintype "passive"))
      (node (ref "C110") (pin "2") (pinfunction "2_2") (pintype "passive"))
      (node (ref "C112") (pin "1") (pinfunction "1_1") (pintype "passive"))
      (node (ref "C113") (pin "1") (pinfunction "1_1") (pintype "passive"))
      (node (ref "C114") (pin "1") (pinfunction "1_1") (pintype "passive"))
      (node (ref "C115") (pin "2") (pinfunction "2_2") (pintype "passive"))
      (node (ref "C116") (pin "2") (pinfunction "2_2") (pintype "passive"))
      (node (ref "C118") (pin "1") (pinfunction "1_1") (pintype "passive"))
      (node (ref "C119") (pin "1") (pinfunction "1_1") (pintype "passive"))
      (node (ref "C12") (pin "2") (pinfunction "2_2") (pintype "passive"))
      (node (ref "C120") (pin "1") (pinfunction "1_1") (pintype "passive"))
      (node (ref "C121") (pin "2") (pinfunction "2_2") (pintype "passive"))
      (node (ref "C122") (pin "2") (pinfunction "2_2") (pintype "passive"))
      (node (ref "C124") (pin "1") (pinfunction "1_1") (pintype "passive"))
      (node (ref "C13") (pin "2") (pinfunction "2_2") (pintype "passive"))
      (node (ref "C14") (pin "2") (pinfunction "2_2") (pintype "passive"))
      (node (ref "C15") (pin "2") (pinfunction "2_2") (pintype "passive"))
      (node (ref "C16") (pin "2") (pinfunction "2_2") (pintype "passive"))
      (node (ref "C17") (pin "2") (pinfunction "2_2") (pintype "passive"))
      (node (ref "C18") (pin "2") (pinfunction "2_2") (pintype "passive"))
      (node (ref "C19") (pin "2") (pinfunction "2_2") (pintype "passive"))
      (node (ref "C2") (pin "2") (pinfunction "2_2") (pintype "passive"))
      (node (ref "C20") (pin "2") (pinfunction "2_2") (pintype "passive"))
      (node (ref "C21") (pin "2") (pinfunction "2_2") (pintype "passive"))
      (node (ref "C22") (pin "2") (pinfunction "2_2") (pintype "passive"))
      (node (ref "C23") (pin "2") (pinfunction "2_2") (pintype "passive"))
      (node (ref "C24") (pin "2") (pinfunction "2_2") (pintype "passive"))
      (node (ref "C25") (pin "2") (pinfunction "2_2") (pintype "passive"))
      (node (ref "C26") (pin "2") (pinfunction "2_2") (pintype "passive"))
      (node (ref "C27") (pin "2") (pinfunction "2_2") (pintype "passive"))
      (node (ref "C28") (pin "2") (pinfunction "2_2") (pintype "passive"))
      (node (ref "C29") (pin "2") (pinfunction "2_2") (pintype "passive"))
      (node (ref "C3") (pin "2") (pinfunction "2_2") (pintype "passive"))
      (node (ref "C30") (pin "2") (pinfunction "2_2") (pintype "passive"))
      (node (ref "C31") (pin "2") (pinfunction "2_2") (pintype "passive"))
      (node (ref "C32") (pin "2") (pinfunction "2_2") (pintype "passive"))
      (node (ref "C33") (pin "2") (pinfunction "2_2") (pintype "passive"))
      (node (ref "C34") (pin "2") (pinfunction "2_2") (pintype "passive"))
      (node (ref "C35") (pin "1") (pinfunction "1_1") (pintype "passive"))
      (node (ref "C36") (pin "1") (pinfunction "1_1") (pintype "passive"))
      (node (ref "C37") (pin "2") (pinfunction "2_2") (pintype "passive"))
      (node (ref "C38") (pin "1") (pinfunction "1_1") (pintype "passive"))
      (node (ref "C39") (pin "2") (pinfunction "2_2") (pintype "passive"))
      (node (ref "C4") (pin "2") (pinfunction "2_2") (pintype "passive"))
      (node (ref "C40") (pin "2") (pinfunction "2_2") (pintype "passive"))
      (node (ref "C41") (pin "2") (pinfunction "2_2") (pintype "passive"))
      (node (ref "C42") (pin "2") (pinfunction "2_2") (pintype "passive"))
      (node (ref "C43") (pin "2") (pinfunction "2_2") (pintype "passive"))
      (node (ref "C44") (pin "2") (pinfunction "2_2") (pintype "passive"))
      (node (ref "C45") (pin "2") (pinfunction "2_2") (pintype "passive"))
      (node (ref "C46") (pin "2") (pinfunction "2_2") (pintype "passive"))
      (node (ref "C47") (pin "2") (pinfunction "2_2") (pintype "passive"))
      (node (ref "C48") (pin "2") (pinfunction "2_2") (pintype "passive"))
      (node (ref "C49") (pin "2") (pinfunction "2_2") (pintype "passive"))
      (node (ref "C5") (pin "2") (pinfunction "2_2") (pintype "passive"))
      (node (ref "C50") (pin "2") (pinfunction "2_2") (pintype "passive"))
      (node (ref "C51") (pin "2") (pinfunction "2_2") (pintype "passive"))
      (node (ref "C52") (pin "2") (pinfunction "2_2") (pintype "passive"))
      (node (ref "C53") (pin "2") (pinfunction "2_2") (pintype "passive"))
      (node (ref "C54") (pin "2") (pinfunction "2_2") (pintype "passive"))
      (node (ref "C55") (pin "2") (pinfunction "2_2") (pintype "passive"))
      (node (ref "C56") (pin "2") (pinfunction "2_2") (pintype "passive"))
      (node (ref "C57") (pin "2") (pinfunction "2_2") (pintype "passive"))
      (node (ref "C58") (pin "2") (pinfunction "2_2") (pintype "passive"))
      (node (ref "C59") (pin "2") (pinfunction "2_2") (pintype "passive"))
      (node (ref "C6") (pin "2") (pinfunction "2_2") (pintype "passive"))
      (node (ref "C60") (pin "2") (pinfunction "2_2") (pintype "passive"))
      (node (ref "C61") (pin "2") (pinfunction "2_2") (pintype "passive"))
      (node (ref "C62") (pin "2") (pinfunction "2_2") (pintype "passive"))
      (node (ref "C63") (pin "2") (pinfunction "2_2") (pintype "passive"))
      (node (ref "C64") (pin "2") (pinfunction "2_2") (pintype "passive"))
      (node (ref "C65") (pin "2") (pinfunction "2_2") (pintype "passive"))
      (node (ref "C66") (pin "2") (pinfunction "2_2") (pintype "passive"))
      (node (ref "C67") (pin "2") (pinfunction "2_2") (pintype "passive"))
      (node (ref "C68") (pin "2") (pinfunction "2_2") (pintype "passive"))
      (node (ref "C69") (pin "2") (pinfunction "2_2") (pintype "passive"))
      (node (ref "C7") (pin "2") (pinfunction "2_2") (pintype "passive"))
      (node (ref "C70") (pin "2") (pinfunction "2_2") (pintype "passive"))
      (node (ref "C71") (pin "2") (pinfunction "2_2") (pintype "passive"))
      (node (ref "C72") (pin "2") (pinfunction "2_2") (pintype "passive"))
      (node (ref "C73") (pin "2") (pinfunction "2_2") (pintype "passive"))
      (node (ref "C74") (pin "2") (pinfunction "2_2") (pintype "passive"))
      (node (ref "C75") (pin "2") (pinfunction "2_2") (pintype "passive"))
      (node (ref "C76") (pin "1") (pinfunction "1_1") (pintype "passive"))
      (node (ref "C77") (pin "1") (pinfunction "1_1") (pintype "passive"))
      (node (ref "C78") (pin "1") (pinfunction "1_1") (pintype "passive"))
      (node (ref "C79") (pin "1") (pinfunction "1_1") (pintype "passive"))
      (node (ref "C8") (pin "2") (pinfunction "2_2") (pintype "passive"))
      (node (ref "C80") (pin "1") (pinfunction "1_1") (pintype "passive"))
      (node (ref "C81") (pin "1") (pinfunction "1_1") (pintype "passive"))
      (node (ref "C82") (pin "1") (pinfunction "1_1") (pintype "passive"))
      (node (ref "C83") (pin "1") (pinfunction "1_1") (pintype "passive"))
      (node (ref "C84") (pin "1") (pinfunction "1_1") (pintype "passive"))
      (node (ref "C85") (pin "1") (pinfunction "1_1") (pintype "passive"))
      (node (ref "C86") (pin "1") (pinfunction "1_1") (pintype "passive"))
      (node (ref "C9") (pin "2") (pinfunction "2_2") (pintype "passive"))
      (node (ref "C91") (pin "1") (pinfunction "1_1") (pintype "passive"))
      (node (ref "C92") (pin "1") (pinfunction "1_1") (pintype "passive"))
      (node (ref "C93") (pin "2") (pinfunction "2_2") (pintype "passive"))
      (node (ref "C94") (pin "2") (pinfunction "2_2") (pintype "passive"))
      (node (ref "C95") (pin "1") (pinfunction "1_1") (pintype "passive"))
      (node (ref "C98") (pin "1") (pinfunction "1_1") (pintype "passive"))
      (node (ref "E1") (pin "2") (pinfunction "2_2") (pintype "passive"))
      (node (ref "FB1") (pin "2") (pinfunction "2_2") (pintype "passive"))
      (node (ref "JP1") (pin "10") (pinfunction "10_10") (pintype "passive"))
      (node (ref "JP1") (pin "2") (pinfunction "2_2") (pintype "passive"))
      (node (ref "R1") (pin "1") (pinfunction "1_1") (pintype "passive"))
      (node (ref "R10") (pin "1") (pinfunction "1_1") (pintype "passive"))
      (node (ref "R11") (pin "1") (pinfunction "1_1") (pintype "passive"))
      (node (ref "R13") (pin "2") (pinfunction "2_2") (pintype "passive"))
      (node (ref "R24") (pin "2") (pinfunction "2_2") (pintype "passive"))
      (node (ref "R28") (pin "2") (pinfunction "2_2") (pintype "passive"))
      (node (ref "R29") (pin "2") (pinfunction "2_2") (pintype "passive"))
      (node (ref "R30") (pin "1") (pinfunction "1_1") (pintype "passive"))
      (node (ref "R31") (pin "2") (pinfunction "2_2") (pintype "passive"))
      (node (ref "R32") (pin "2") (pinfunction "2_2") (pintype "passive"))
      (node (ref "R35") (pin "2") (pinfunction "2_2") (pintype "passive"))
      (node (ref "R36") (pin "2") (pinfunction "2_2") (pintype "passive"))
      (node (ref "R39") (pin "2") (pinfunction "2_2") (pintype "passive"))
      (node (ref "R50") (pin "2") (pinfunction "2_2") (pintype "passive"))
      (node (ref "R57") (pin "1") (pinfunction "1_1") (pintype "passive"))
      (node (ref "R6") (pin "1") (pinfunction "1_1") (pintype "passive"))
      (node (ref "R64") (pin "2") (pinfunction "2_2") (pintype "passive"))
      (node (ref "R66") (pin "2") (pinfunction "2_2") (pintype "passive"))
      (node (ref "R7") (pin "1") (pinfunction "1_1") (pintype "passive"))
      (node (ref "SW1") (pin "1") (pinfunction "1_1") (pintype "passive"))
      (node (ref "U1") (pin "A11") (pinfunction "GND_A11") (pintype "power_in"))
      (node (ref "U1") (pin "A12") (pinfunction "GND_A12") (pintype "power_in"))
      (node (ref "U1") (pin "A2") (pinfunction "GND_A2") (pintype "power_in"))
      (node (ref "U1") (pin "A22") (pinfunction "GND_A22") (pintype "power_in"))
      (node (ref "U1") (pin "A3") (pinfunction "GND_A3") (pintype "power_in"))
      (node (ref "U1") (pin "A5") (pinfunction "GND_A5") (pintype "power_in"))
      (node (ref "U1") (pin "A7") (pinfunction "GND_A7") (pintype "power_in"))
      (node (ref "U1") (pin "A9") (pinfunction "GND_A9") (pintype "power_in"))
      (node (ref "U1") (pin "AA12") (pinfunction "GND_AA12") (pintype "power_in"))
      (node (ref "U1") (pin "AA2") (pinfunction "GND_AA2") (pintype "power_in"))
      (node (ref "U1") (pin "AA22") (pinfunction "GND_AA22") (pintype "power_in"))
      (node (ref "U1") (pin "AB19") (pinfunction "GND_AB19") (pintype "power_in"))
      (node (ref "U1") (pin "AB9") (pinfunction "GND_AB9") (pintype "power_in"))
      (node (ref "U1") (pin "B12") (pinfunction "GND_B12") (pintype "power_in"))
      (node (ref "U1") (pin "B19") (pinfunction "GND_B19") (pintype "power_in"))
      (node (ref "U1") (pin "B3") (pinfunction "GND_B3") (pintype "power_in"))
      (node (ref "U1") (pin "C10") (pinfunction "GND_C10") (pintype "power_in"))
      (node (ref "U1") (pin "C12") (pinfunction "GND_C12") (pintype "power_in"))
      (node (ref "U1") (pin "C16") (pinfunction "GND_C16") (pintype "power_in"))
      (node (ref "U1") (pin "C3") (pinfunction "GND_C3") (pintype "power_in"))
      (node (ref "U1") (pin "C6") (pinfunction "GND_C6") (pintype "power_in"))
      (node (ref "U1") (pin "D12") (pinfunction "GND_D12") (pintype "power_in"))
      (node (ref "U1") (pin "D13") (pinfunction "GND_D13") (pintype "power_in"))
      (node (ref "U1") (pin "D3") (pinfunction "GND_D3") (pintype "power_in"))
      (node (ref "U1") (pin "D4") (pinfunction "GND_D4") (pintype "power_in"))
      (node (ref "U1") (pin "D8") (pinfunction "GND_D8") (pintype "power_in"))
      (node (ref "U1") (pin "E11") (pinfunction "GND_E11") (pintype "power_in"))
      (node (ref "U1") (pin "E20") (pinfunction "GND_E20") (pintype "power_in"))
      (node (ref "U1") (pin "E4") (pinfunction "GND_E4") (pintype "power_in"))
      (node (ref "U1") (pin "E5") (pinfunction "GND_E5") (pintype "power_in"))
      (node (ref "U1") (pin "E7") (pinfunction "GND_E7") (pintype "power_in"))
      (node (ref "U1") (pin "E9") (pinfunction "GND_E9") (pintype "power_in"))
      (node (ref "U1") (pin "F11") (pinfunction "GND_F11") (pintype "power_in"))
      (node (ref "U1") (pin "F17") (pinfunction "GND_F17") (pintype "power_in"))
      (node (ref "U1") (pin "F5") (pinfunction "GND_F5") (pintype "power_in"))
      (node (ref "U1") (pin "G10") (pinfunction "GND_G10") (pintype "power_in"))
      (node (ref "U1") (pin "G12") (pinfunction "GND_G12") (pintype "power_in"))
      (node (ref "U1") (pin "G14") (pinfunction "GND_G14") (pintype "power_in"))
      (node (ref "U1") (pin "G5") (pinfunction "GND_G5") (pintype "power_in"))
      (node (ref "U1") (pin "G6") (pinfunction "GND_G6") (pintype "power_in"))
      (node (ref "U1") (pin "G7") (pinfunction "GND_G7") (pintype "power_in"))
      (node (ref "U1") (pin "G8") (pinfunction "GND_G8") (pintype "power_in"))
      (node (ref "U1") (pin "G9") (pinfunction "GND_G9") (pintype "power_in"))
      (node (ref "U1") (pin "H1") (pinfunction "GND_H1") (pintype "power_in"))
      (node (ref "U1") (pin "H11") (pinfunction "GND_H11") (pintype "power_in"))
      (node (ref "U1") (pin "H21") (pinfunction "GND_H21") (pintype "power_in"))
      (node (ref "U1") (pin "H7") (pinfunction "GND_H7") (pintype "power_in"))
      (node (ref "U1") (pin "H9") (pinfunction "GND_H9") (pintype "power_in"))
      (node (ref "U1") (pin "J10") (pinfunction "GND_J10") (pintype "power_in"))
      (node (ref "U1") (pin "J12") (pinfunction "GND_J12") (pintype "power_in"))
      (node (ref "U1") (pin "J18") (pinfunction "GND_J18") (pintype "power_in"))
      (node (ref "U1") (pin "J8") (pinfunction "GND_J8") (pintype "power_in"))
      (node (ref "U1") (pin "K11") (pinfunction "GND_K11") (pintype "power_in"))
      (node (ref "U1") (pin "K15") (pinfunction "GND_K15") (pintype "power_in"))
      (node (ref "U1") (pin "K5") (pinfunction "GND_K5") (pintype "power_in"))
      (node (ref "U1") (pin "K7") (pinfunction "GND_K7") (pintype "power_in"))
      (node (ref "U1") (pin "L2") (pinfunction "GND_L2") (pintype "power_in"))
      (node (ref "U1") (pin "L22") (pinfunction "GND_L22") (pintype "power_in"))
      (node (ref "U1") (pin "L8") (pinfunction "GND_L8") (pintype "power_in"))
      (node (ref "U1") (pin "M11") (pinfunction "GND_M11") (pintype "power_in"))
      (node (ref "U1") (pin "M19") (pinfunction "GND_M19") (pintype "power_in"))
      (node (ref "U1") (pin "M7") (pinfunction "GND_M7") (pintype "power_in"))
      (node (ref "U1") (pin "N10") (pinfunction "DXP_0_N10") (pintype "input"))
      (node (ref "U1") (pin "N16") (pinfunction "GND_N16") (pintype "power_in"))
      (node (ref "U1") (pin "N6") (pinfunction "GND_N6") (pintype "power_in"))
      (node (ref "U1") (pin "N8") (pinfunction "GND_N8") (pintype "power_in"))
      (node (ref "U1") (pin "N9") (pinfunction "DXN_0_N9") (pintype "input"))
      (node (ref "U1") (pin "P11") (pinfunction "GND_P11") (pintype "power_in"))
      (node (ref "U1") (pin "P13") (pinfunction "GND_P13") (pintype "power_in"))
      (node (ref "U1") (pin "P3") (pinfunction "GND_P3") (pintype "power_in"))
      (node (ref "U1") (pin "P7") (pinfunction "GND_P7") (pintype "power_in"))
      (node (ref "U1") (pin "P9") (pinfunction "GND_P9") (pintype "power_in"))
      (node (ref "U1") (pin "R10") (pinfunction "GND_R10") (pintype "power_in"))
      (node (ref "U1") (pin "R12") (pinfunction "GND_R12") (pintype "power_in"))
      (node (ref "U1") (pin "R20") (pinfunction "GND_R20") (pintype "power_in"))
      (node (ref "U1") (pin "R8") (pinfunction "GND_R8") (pintype "power_in"))
      (node (ref "U1") (pin "T11") (pinfunction "GND_T11") (pintype "power_in"))
      (node (ref "U1") (pin "T17") (pinfunction "GND_T17") (pintype "power_in"))
      (node (ref "U1") (pin "T7") (pinfunction "GND_T7") (pintype "power_in"))
      (node (ref "U1") (pin "T9") (pinfunction "GND_T9") (pintype "power_in"))
      (node (ref "U1") (pin "U14") (pinfunction "GND_U14") (pintype "power_in"))
      (node (ref "U1") (pin "U4") (pinfunction "GND_U4") (pintype "power_in"))
      (node (ref "U1") (pin "V1") (pinfunction "GND_V1") (pintype "power_in"))
      (node (ref "U1") (pin "V11") (pinfunction "GND_V11") (pintype "power_in"))
      (node (ref "U1") (pin "V21") (pinfunction "GND_V21") (pintype "power_in"))
      (node (ref "U1") (pin "W18") (pinfunction "GND_W18") (pintype "power_in"))
      (node (ref "U1") (pin "W8") (pinfunction "GND_W8") (pintype "power_in"))
      (node (ref "U1") (pin "Y15") (pinfunction "GND_Y15") (pintype "power_in"))
      (node (ref "U1") (pin "Y5") (pinfunction "GND_Y5") (pintype "power_in"))
      (node (ref "U10") (pin "1") (pinfunction "GND3_1") (pintype "passive"))
      (node (ref "U10") (pin "13") (pinfunction "GND1_13") (pintype "passive"))
      (node (ref "U10") (pin "18") (pinfunction "GND4_18") (pintype "passive"))
      (node (ref "U10") (pin "25") (pinfunction "EP_25") (pintype "passive"))
      (node (ref "U10") (pin "4") (pinfunction "AGND_4") (pintype "passive"))
      (node (ref "U10") (pin "6") (pinfunction "GND2_6") (pintype "passive"))
      (node (ref "U2") (pin "59") (pinfunction "59_59") (pintype "passive"))
      (node (ref "U2") (pin "61") (pinfunction "61_61") (pintype "passive"))
      (node (ref "U2") (pin "62") (pinfunction "62_62") (pintype "passive"))
      (node (ref "U3") (pin "57") (pinfunction "57_57") (pintype "passive"))
      (node (ref "U3") (pin "58") (pinfunction "58_58") (pintype "passive"))
      (node (ref "U3") (pin "59") (pinfunction "59_59") (pintype "passive"))
      (node (ref "U3") (pin "60") (pinfunction "60_60") (pintype "passive"))
      (node (ref "U3") (pin "61") (pinfunction "61_61") (pintype "passive"))
      (node (ref "U3") (pin "62") (pinfunction "62_62") (pintype "passive"))
      (node (ref "U4") (pin "59") (pinfunction "59_59") (pintype "passive"))
      (node (ref "U4") (pin "61") (pinfunction "61_61") (pintype "passive"))
      (node (ref "U4") (pin "62") (pinfunction "62_62") (pintype "passive"))
      (node (ref "U5") (pin "55") (pinfunction "55_55") (pintype "passive"))
      (node (ref "U5") (pin "60") (pinfunction "60_60") (pintype "passive"))
      (node (ref "U5") (pin "61") (pinfunction "61_61") (pintype "passive"))
      (node (ref "U5") (pin "62") (pinfunction "62_62") (pintype "passive"))
      (node (ref "U6") (pin "2") (pinfunction "GND_2") (pintype "passive"))
      (node (ref "U7") (pin "2") (pinfunction "GND_2") (pintype "passive"))
      (node (ref "U8") (pin "4") (pinfunction "GND_4") (pintype "passive"))
      (node (ref "U9") (pin "A9") (pinfunction "VSS_A9") (pintype "passive"))
      (node (ref "U9") (pin "B1") (pinfunction "VSSQ_B1") (pintype "passive"))
      (node (ref "U9") (pin "B3") (pinfunction "VSS_B3") (pintype "passive"))
      (node (ref "U9") (pin "B9") (pinfunction "VSSQ_B9") (pintype "passive"))
      (node (ref "U9") (pin "D1") (pinfunction "VSSQ_D1") (pintype "passive"))
      (node (ref "U9") (pin "D8") (pinfunction "VSSQ_D8") (pintype "passive"))
      (node (ref "U9") (pin "E1") (pinfunction "VSS_E1") (pintype "passive"))
      (node (ref "U9") (pin "E2") (pinfunction "VSSQ_E2") (pintype "passive"))
      (node (ref "U9") (pin "E8") (pinfunction "VSSQ_E8") (pintype "passive"))
      (node (ref "U9") (pin "F9") (pinfunction "VSSQ_F9") (pintype "passive"))
      (node (ref "U9") (pin "G1") (pinfunction "VSSQ_G1") (pintype "passive"))
      (node (ref "U9") (pin "G8") (pinfunction "VSS_G8") (pintype "passive"))
      (node (ref "U9") (pin "G9") (pinfunction "VSSQ_G9") (pintype "passive"))
      (node (ref "U9") (pin "J2") (pinfunction "VSS_J2") (pintype "passive"))
      (node (ref "U9") (pin "J8") (pinfunction "VSS_J8") (pintype "passive"))
      (node (ref "U9") (pin "M1") (pinfunction "VSS_M1") (pintype "passive"))
      (node (ref "U9") (pin "M9") (pinfunction "VSS_M9") (pintype "passive"))
      (node (ref "U9") (pin "P1") (pinfunction "VSS_P1") (pintype "passive"))
      (node (ref "U9") (pin "P9") (pinfunction "VSS_P9") (pintype "passive"))
      (node (ref "U9") (pin "T1") (pinfunction "VSS_T1") (pintype "passive"))
      (node (ref "U9") (pin "T9") (pinfunction "VSS_T9") (pintype "passive"))
      (node (ref "USBC1") (pin "0") (pinfunction "0_0") (pintype "passive"))
      (node (ref "USBC1") (pin "A1") (pinfunction "GND_A1") (pintype "passive"))
      (node (ref "USBC1") (pin "A12") (pinfunction "GND_A12") (pintype "passive"))
      (node (ref "USBC1") (pin "B1") (pinfunction "GND_B1") (pintype "passive"))
      (node (ref "USBC1") (pin "B12") (pinfunction "GND_B12") (pintype "passive"))
      (node (ref "X1") (pin "2") (pinfunction "GND_2") (pintype "passive"))
    )
    (net (code "290") (name "MGTAVCC") (class "Default")
      (node (ref "C74") (pin "1") (pinfunction "1_1") (pintype "passive"))
      (node (ref "FB2") (pin "2") (pinfunction "2_2") (pintype "passive"))
      (node (ref "R2") (pin "1") (pinfunction "1_1") (pintype "passive"))
      (node (ref "R4") (pin "1") (pinfunction "1_1") (pintype "passive"))
    )
    (net (code "291") (name "MGTAVTT") (class "Default")
      (node (ref "C37") (pin "1") (pinfunction "1_1") (pintype "passive"))
      (node (ref "C38") (pin "2") (pinfunction "2_2") (pintype "passive"))
      (node (ref "R3") (pin "1") (pinfunction "1_1") (pintype "passive"))
      (node (ref "R5") (pin "1") (pinfunction "1_1") (pintype "passive"))
      (node (ref "U7") (pin "5") (pinfunction "VOUT_5") (pintype "passive"))
    )
    (net (code "292") (name "Net-(C124-Pad2)") (class "Default")
      (node (ref "C124") (pin "2") (pinfunction "2_2") (pintype "passive"))
      (node (ref "R61") (pin "1") (pinfunction "1_1") (pintype "passive"))
      (node (ref "R68") (pin "1") (pinfunction "1_1") (pintype "passive"))
    )
    (net (code "293") (name "Net-(JP1-Pad1)") (class "Default")
      (node (ref "JP1") (pin "1") (pinfunction "1_1") (pintype "passive"))
      (node (ref "R19") (pin "2") (pinfunction "2_2") (pintype "passive"))
    )
    (net (code "294") (name "Net-(JP1-Pad3)") (class "Default")
      (node (ref "JP1") (pin "3") (pinfunction "3_3") (pintype "passive"))
      (node (ref "R20") (pin "2") (pinfunction "2_2") (pintype "passive"))
    )
    (net (code "295") (name "Net-(JP1-Pad5)") (class "Default")
      (node (ref "JP1") (pin "5") (pinfunction "5_5") (pintype "passive"))
      (node (ref "R22") (pin "2") (pinfunction "2_2") (pintype "passive"))
    )
    (net (code "296") (name "Net-(JP1-Pad9)") (class "Default")
      (node (ref "JP1") (pin "9") (pinfunction "9_9") (pintype "passive"))
      (node (ref "R23") (pin "2") (pinfunction "2_2") (pintype "passive"))
    )
    (net (code "297") (name "Net-(LED1-K)") (class "Default")
      (node (ref "LED1") (pin "2") (pinfunction "K_2") (pintype "passive"))
      (node (ref "R13") (pin "1") (pinfunction "1_1") (pintype "passive"))
    )
    (net (code "298") (name "Net-(LED2-K)") (class "Default")
      (node (ref "LED2") (pin "2") (pinfunction "K_2") (pintype "passive"))
      (node (ref "R31") (pin "1") (pinfunction "1_1") (pintype "passive"))
    )
    (net (code "299") (name "Net-(LED3-K)") (class "Default")
      (node (ref "LED3") (pin "2") (pinfunction "K_2") (pintype "passive"))
      (node (ref "R32") (pin "1") (pinfunction "1_1") (pintype "passive"))
    )
    (net (code "300") (name "Net-(LED4-K)") (class "Default")
      (node (ref "LED4") (pin "2") (pinfunction "K_2") (pintype "passive"))
      (node (ref "R66") (pin "1") (pinfunction "1_1") (pintype "passive"))
    )
    (net (code "301") (name "Net-(R4-Pad2)") (class "Default")
      (node (ref "R4") (pin "2") (pinfunction "2_2") (pintype "passive"))
      (node (ref "R6") (pin "2") (pinfunction "2_2") (pintype "passive"))
      (node (ref "U1") (pin "D10") (pinfunction "MGTAVCC_D10") (pintype "power_in"))
      (node (ref "U1") (pin "D6") (pinfunction "MGTAVCC_D6") (pintype "power_in"))
      (node (ref "U1") (pin "E8") (pinfunction "MGTAVCC_E8") (pintype "power_in"))
      (node (ref "U1") (pin "F7") (pinfunction "MGTAVCC_F7") (pintype "power_in"))
      (node (ref "U1") (pin "F9") (pinfunction "MGTAVCC_F9") (pintype "power_in"))
    )
    (net (code "302") (name "Net-(R5-Pad2)") (class "Default")
      (node (ref "R5") (pin "2") (pinfunction "2_2") (pintype "passive"))
      (node (ref "R7") (pin "2") (pinfunction "2_2") (pintype "passive"))
      (node (ref "U1") (pin "B11") (pinfunction "MGTAVTT_B11") (pintype "power_in"))
      (node (ref "U1") (pin "B5") (pinfunction "MGTAVTT_B5") (pintype "power_in"))
      (node (ref "U1") (pin "B7") (pinfunction "MGTAVTT_B7") (pintype "power_in"))
      (node (ref "U1") (pin "B9") (pinfunction "MGTAVTT_B9") (pintype "power_in"))
      (node (ref "U1") (pin "C4") (pinfunction "MGTAVTT_C4") (pintype "power_in"))
      (node (ref "U1") (pin "C8") (pinfunction "MGTAVTT_C8") (pintype "power_in"))
    )
    (net (code "303") (name "Net-(U1F-INIT_B_0)") (class "Default")
      (node (ref "R14") (pin "2") (pinfunction "2_2") (pintype "passive"))
      (node (ref "U1") (pin "U12") (pinfunction "INIT_B_0_U12") (pintype "bidirectional"))
    )
    (net (code "304") (name "Net-(U1G-MGTRREF_216)") (class "Default")
      (node (ref "R1") (pin "2") (pinfunction "2_2") (pintype "passive"))
      (node (ref "R2") (pin "2") (pinfunction "2_2") (pintype "passive"))
      (node (ref "R3") (pin "2") (pinfunction "2_2") (pintype "passive"))
      (node (ref "U1") (pin "F8") (pinfunction "MGTRREF_216_F8") (pintype "input"))
    )
    (net (code "305") (name "Net-(U1J-VCCADC_0)") (class "Default")
      (node (ref "C93") (pin "1") (pinfunction "1_1") (pintype "passive"))
      (node (ref "C94") (pin "1") (pinfunction "1_1") (pintype "passive"))
      (node (ref "FB3") (pin "1") (pinfunction "1_1") (pintype "passive"))
      (node (ref "U1") (pin "K10") (pinfunction "VCCADC_0_K10") (pintype "power_in"))
    )
    (net (code "306") (name "Net-(U8-CLK)") (class "Default")
      (node (ref "R21") (pin "1") (pinfunction "1_1") (pintype "passive"))
      (node (ref "U8") (pin "6") (pinfunction "CLK_6") (pintype "passive"))
    )
    (net (code "307") (name "Net-(U9B-ZQ)") (class "Default")
      (node (ref "R57") (pin "2") (pinfunction "2_2") (pintype "passive"))
      (node (ref "U9") (pin "L8") (pinfunction "ZQ_L8") (pintype "passive"))
    )
    (net (code "308") (name "Net-(U10-EN1)") (class "Default")
      (node (ref "C118") (pin "2") (pinfunction "2_2") (pintype "passive"))
      (node (ref "R48") (pin "1") (pinfunction "1_1") (pintype "passive"))
      (node (ref "U10") (pin "10") (pinfunction "EN1_10") (pintype "passive"))
    )
    (net (code "309") (name "Net-(U10-EN2)") (class "Default")
      (node (ref "C119") (pin "2") (pinfunction "2_2") (pintype "passive"))
      (node (ref "R52") (pin "1") (pinfunction "1_1") (pintype "passive"))
      (node (ref "U10") (pin "9") (pinfunction "EN2_9") (pintype "passive"))
    )
    (net (code "310") (name "Net-(U10-EN3)") (class "Default")
      (node (ref "C120") (pin "2") (pinfunction "2_2") (pintype "passive"))
      (node (ref "R56") (pin "1") (pinfunction "1_1") (pintype "passive"))
      (node (ref "R65") (pin "2") (pinfunction "2_2") (pintype "passive"))
      (node (ref "U10") (pin "22") (pinfunction "EN3_22") (pintype "passive"))
    )
    (net (code "311") (name "Net-(U10-EN4)") (class "Default")
      (node (ref "R65") (pin "1") (pinfunction "1_1") (pintype "passive"))
      (node (ref "R68") (pin "2") (pinfunction "2_2") (pintype "passive"))
      (node (ref "U10") (pin "21") (pinfunction "EN4_21") (pintype "passive"))
    )
    (net (code "312") (name "Net-(U10-FB1)") (class "Default")
      (node (ref "C105") (pin "2") (pinfunction "2_2") (pintype "passive"))
      (node (ref "R34") (pin "1") (pinfunction "1_1") (pintype "passive"))
      (node (ref "R36") (pin "1") (pinfunction "1_1") (pintype "passive"))
      (node (ref "U10") (pin "14") (pinfunction "FB1_14") (pintype "passive"))
    )
    (net (code "313") (name "Net-(U10-FB2)") (class "Default")
      (node (ref "C111") (pin "2") (pinfunction "2_2") (pintype "passive"))
      (node (ref "R37") (pin "1") (pinfunction "1_1") (pintype "passive"))
      (node (ref "R39") (pin "1") (pinfunction "1_1") (pintype "passive"))
      (node (ref "U10") (pin "5") (pinfunction "FB2_5") (pintype "passive"))
    )
    (net (code "314") (name "Net-(U10-FB3)") (class "Default")
      (node (ref "C117") (pin "2") (pinfunction "2_2") (pintype "passive"))
      (node (ref "R46") (pin "1") (pinfunction "1_1") (pintype "passive"))
      (node (ref "R50") (pin "1") (pinfunction "1_1") (pintype "passive"))
      (node (ref "U10") (pin "2") (pinfunction "FB3_2") (pintype "passive"))
    )
    (net (code "315") (name "Net-(U10-FB4)") (class "Default")
      (node (ref "C123") (pin "2") (pinfunction "2_2") (pintype "passive"))
      (node (ref "R60") (pin "1") (pinfunction "1_1") (pintype "passive"))
      (node (ref "R64") (pin "1") (pinfunction "1_1") (pintype "passive"))
      (node (ref "U10") (pin "17") (pinfunction "FB4_17") (pintype "passive"))
    )
    (net (code "316") (name "Net-(U10-LX1)") (class "Default")
      (node (ref "L1") (pin "2") (pinfunction "2_2") (pintype "passive"))
      (node (ref "U10") (pin "12") (pinfunction "LX1_12") (pintype "passive"))
    )
    (net (code "317") (name "Net-(U10-LX2)") (class "Default")
      (node (ref "L2") (pin "2") (pinfunction "2_2") (pintype "passive"))
      (node (ref "U10") (pin "7") (pinfunction "LX2_7") (pintype "passive"))
    )
    (net (code "318") (name "Net-(U10-LX3)") (class "Default")
      (node (ref "L3") (pin "2") (pinfunction "2_2") (pintype "passive"))
      (node (ref "U10") (pin "24") (pinfunction "LX3_24") (pintype "passive"))
    )
    (net (code "319") (name "Net-(U10-LX4)") (class "Default")
      (node (ref "L4") (pin "2") (pinfunction "2_2") (pintype "passive"))
      (node (ref "U10") (pin "19") (pinfunction "LX4_19") (pintype "passive"))
    )
    (net (code "320") (name "unconnected-(JP1-Pad6)") (class "Default")
      (node (ref "JP1") (pin "6") (pinfunction "6_6") (pintype "passive+no_connect"))
    )
    (net (code "321") (name "unconnected-(JP1-Pad7)") (class "Default")
      (node (ref "JP1") (pin "7") (pinfunction "7_7") (pintype "passive+no_connect"))
    )
    (net (code "322") (name "unconnected-(JP1-Pad8)") (class "Default")
      (node (ref "JP1") (pin "8") (pinfunction "8_8") (pintype "passive+no_connect"))
    )
    (net (code "323") (name "unconnected-(U1E-IO_L6N_T0_VREF_35-PadE3)") (class "Default")
      (node (ref "U1") (pin "E3") (pinfunction "IO_L6N_T0_VREF_35_E3") (pintype "bidirectional+no_connect"))
    )
    (net (code "324") (name "unconnected-(U1E-IO_L12N_T1_MRCC_35-PadG4)") (class "Default")
      (node (ref "U1") (pin "G4") (pinfunction "IO_L12N_T1_MRCC_35_G4") (pintype "bidirectional+no_connect"))
    )
    (net (code "325") (name "unconnected-(U1L-NC-PadAA9)") (class "Default")
      (node (ref "U1") (pin "AA9") (pinfunction "NC_AA9") (pintype "passive+no_connect"))
    )
    (net (code "326") (name "unconnected-(U1L-NC-PadAA10)") (class "Default")
      (node (ref "U1") (pin "AA10") (pinfunction "NC_AA10") (pintype "passive+no_connect"))
    )
    (net (code "327") (name "unconnected-(U1L-NC-PadAA11)") (class "Default")
      (node (ref "U1") (pin "AA11") (pinfunction "NC_AA11") (pintype "passive+no_connect"))
    )
    (net (code "328") (name "unconnected-(U1L-NC-PadAA13)") (class "Default")
      (node (ref "U1") (pin "AA13") (pinfunction "NC_AA13") (pintype "passive+no_connect"))
    )
    (net (code "329") (name "unconnected-(U1L-NC-PadAA14)") (class "Default")
      (node (ref "U1") (pin "AA14") (pinfunction "NC_AA14") (pintype "passive+no_connect"))
    )
    (net (code "330") (name "unconnected-(U1L-NC-PadAA15)") (class "Default")
      (node (ref "U1") (pin "AA15") (pinfunction "NC_AA15") (pintype "passive+no_connect"))
    )
    (net (code "331") (name "unconnected-(U1L-NC-PadAA16)") (class "Default")
      (node (ref "U1") (pin "AA16") (pinfunction "NC_AA16") (pintype "passive+no_connect"))
    )
    (net (code "332") (name "unconnected-(U1L-NC-PadAB10)") (class "Default")
      (node (ref "U1") (pin "AB10") (pinfunction "NC_AB10") (pintype "passive+no_connect"))
    )
    (net (code "333") (name "unconnected-(U1L-NC-PadAB11)") (class "Default")
      (node (ref "U1") (pin "AB11") (pinfunction "NC_AB11") (pintype "passive+no_connect"))
    )
    (net (code "334") (name "unconnected-(U1L-NC-PadAB12)") (class "Default")
      (node (ref "U1") (pin "AB12") (pinfunction "NC_AB12") (pintype "passive+no_connect"))
    )
    (net (code "335") (name "unconnected-(U1L-NC-PadAB13)") (class "Default")
      (node (ref "U1") (pin "AB13") (pinfunction "NC_AB13") (pintype "passive+no_connect"))
    )
    (net (code "336") (name "unconnected-(U1L-NC-PadAB15)") (class "Default")
      (node (ref "U1") (pin "AB15") (pinfunction "NC_AB15") (pintype "passive+no_connect"))
    )
    (net (code "337") (name "unconnected-(U1L-NC-PadAB16)") (class "Default")
      (node (ref "U1") (pin "AB16") (pinfunction "NC_AB16") (pintype "passive+no_connect"))
    )
    (net (code "338") (name "unconnected-(U1L-NC-PadAB17)") (class "Default")
      (node (ref "U1") (pin "AB17") (pinfunction "NC_AB17") (pintype "passive+no_connect"))
    )
    (net (code "339") (name "unconnected-(U1L-NC-PadT14)") (class "Default")
      (node (ref "U1") (pin "T14") (pinfunction "NC_T14") (pintype "passive+no_connect"))
    )
    (net (code "340") (name "unconnected-(U1L-NC-PadT15)") (class "Default")
      (node (ref "U1") (pin "T15") (pinfunction "NC_T15") (pintype "passive+no_connect"))
    )
    (net (code "341") (name "unconnected-(U1L-NC-PadT16)") (class "Default")
      (node (ref "U1") (pin "T16") (pinfunction "NC_T16") (pintype "passive+no_connect"))
    )
    (net (code "342") (name "unconnected-(U1L-NC-PadU15)") (class "Default")
      (node (ref "U1") (pin "U15") (pinfunction "NC_U15") (pintype "passive+no_connect"))
    )
    (net (code "343") (name "unconnected-(U1L-NC-PadU16)") (class "Default")
      (node (ref "U1") (pin "U16") (pinfunction "NC_U16") (pintype "passive+no_connect"))
    )
    (net (code "344") (name "unconnected-(U1L-NC-PadV10)") (class "Default")
      (node (ref "U1") (pin "V10") (pinfunction "NC_V10") (pintype "passive+no_connect"))
    )
    (net (code "345") (name "unconnected-(U1L-NC-PadV13)") (class "Default")
      (node (ref "U1") (pin "V13") (pinfunction "NC_V13") (pintype "passive+no_connect"))
    )
    (net (code "346") (name "unconnected-(U1L-NC-PadV14)") (class "Default")
      (node (ref "U1") (pin "V14") (pinfunction "NC_V14") (pintype "passive+no_connect"))
    )
    (net (code "347") (name "unconnected-(U1L-NC-PadV15)") (class "Default")
      (node (ref "U1") (pin "V15") (pinfunction "NC_V15") (pintype "passive+no_connect"))
    )
    (net (code "348") (name "unconnected-(U1L-NC-PadW10)") (class "Default")
      (node (ref "U1") (pin "W10") (pinfunction "NC_W10") (pintype "passive+no_connect"))
    )
    (net (code "349") (name "unconnected-(U1L-NC-PadW11)") (class "Default")
      (node (ref "U1") (pin "W11") (pinfunction "NC_W11") (pintype "passive+no_connect"))
    )
    (net (code "350") (name "unconnected-(U1L-NC-PadW12)") (class "Default")
      (node (ref "U1") (pin "W12") (pinfunction "NC_W12") (pintype "passive+no_connect"))
    )
    (net (code "351") (name "unconnected-(U1L-NC-PadW14)") (class "Default")
      (node (ref "U1") (pin "W14") (pinfunction "NC_W14") (pintype "passive+no_connect"))
    )
    (net (code "352") (name "unconnected-(U1L-NC-PadW15)") (class "Default")
      (node (ref "U1") (pin "W15") (pinfunction "NC_W15") (pintype "passive+no_connect"))
    )
    (net (code "353") (name "unconnected-(U1L-NC-PadW16)") (class "Default")
      (node (ref "U1") (pin "W16") (pinfunction "NC_W16") (pintype "passive+no_connect"))
    )
    (net (code "354") (name "unconnected-(U1L-NC-PadY11)") (class "Default")
      (node (ref "U1") (pin "Y11") (pinfunction "NC_Y11") (pintype "passive+no_connect"))
    )
    (net (code "355") (name "unconnected-(U1L-NC-PadY12)") (class "Default")
      (node (ref "U1") (pin "Y12") (pinfunction "NC_Y12") (pintype "passive+no_connect"))
    )
    (net (code "356") (name "unconnected-(U1L-NC-PadY13)") (class "Default")
      (node (ref "U1") (pin "Y13") (pinfunction "NC_Y13") (pintype "passive+no_connect"))
    )
    (net (code "357") (name "unconnected-(U1L-NC-PadY14)") (class "Default")
      (node (ref "U1") (pin "Y14") (pinfunction "NC_Y14") (pintype "passive+no_connect"))
    )
    (net (code "358") (name "unconnected-(U1L-NC-PadY16)") (class "Default")
      (node (ref "U1") (pin "Y16") (pinfunction "NC_Y16") (pintype "passive+no_connect"))
    )
    (net (code "359") (name "unconnected-(U1L-NC-PadY17)") (class "Default")
      (node (ref "U1") (pin "Y17") (pinfunction "NC_Y17") (pintype "passive+no_connect"))
    )
    (net (code "360") (name "unconnected-(U6-BYP{slash}ADJ-Pad4)") (class "Default")
      (node (ref "U6") (pin "4") (pinfunction "BYP/ADJ_4") (pintype "passive+no_connect"))
    )
    (net (code "361") (name "unconnected-(U7-BYP-Pad4)") (class "Default")
      (node (ref "U7") (pin "4") (pinfunction "BYP_4") (pintype "passive+no_connect"))
    )
    (net (code "362") (name "unconnected-(U9B-A14-PadT7)") (class "Default")
      (node (ref "U9") (pin "T7") (pinfunction "A14_T7") (pintype "passive+no_connect"))
    )
    (net (code "363") (name "unconnected-(U9B-NC-PadJ1)") (class "Default")
      (node (ref "U9") (pin "J1") (pinfunction "NC_J1") (pintype "passive+no_connect"))
    )
    (net (code "364") (name "unconnected-(U9B-NC-PadJ9)") (class "Default")
      (node (ref "U9") (pin "J9") (pinfunction "NC_J9") (pintype "passive+no_connect"))
    )
    (net (code "365") (name "unconnected-(U9B-NC-PadL1)") (class "Default")
      (node (ref "U9") (pin "L1") (pinfunction "NC_L1") (pintype "passive+no_connect"))
    )
    (net (code "366") (name "unconnected-(U9B-NC-PadL9)") (class "Default")
      (node (ref "U9") (pin "L9") (pinfunction "NC_L9") (pintype "passive+no_connect"))
    )
    (net (code "367") (name "unconnected-(U9B-NC-PadM7)") (class "Default")
      (node (ref "U9") (pin "M7") (pinfunction "NC_M7") (pintype "passive+no_connect"))
    )
    (net (code "368") (name "unconnected-(U10-NC-Pad15)") (class "Default")
      (node (ref "U10") (pin "15") (pinfunction "NC_15") (pintype "passive+no_connect"))
    )
    (net (code "369") (name "unconnected-(U10-NC-Pad16)") (class "Default")
      (node (ref "U10") (pin "16") (pinfunction "NC_16") (pintype "passive+no_connect"))
    )
    (net (code "370") (name "unconnected-(USBC1-CC1-PadA5)") (class "Default")
      (node (ref "USBC1") (pin "A5") (pinfunction "CC1_A5") (pintype "passive+no_connect"))
    )
    (net (code "371") (name "unconnected-(USBC1-CC2-PadB5)") (class "Default")
      (node (ref "USBC1") (pin "B5") (pinfunction "CC2_B5") (pintype "passive+no_connect"))
    )
    (net (code "372") (name "unconnected-(USBC1-DN1-PadA7)") (class "Default")
      (node (ref "USBC1") (pin "A7") (pinfunction "DN1_A7") (pintype "passive+no_connect"))
    )
    (net (code "373") (name "unconnected-(USBC1-DN2-PadB7)") (class "Default")
      (node (ref "USBC1") (pin "B7") (pinfunction "DN2_B7") (pintype "passive+no_connect"))
    )
    (net (code "374") (name "unconnected-(USBC1-DP1-PadA6)") (class "Default")
      (node (ref "USBC1") (pin "A6") (pinfunction "DP1_A6") (pintype "passive+no_connect"))
    )
    (net (code "375") (name "unconnected-(USBC1-DP2-PadB6)") (class "Default")
      (node (ref "USBC1") (pin "B6") (pinfunction "DP2_B6") (pintype "passive+no_connect"))
    )
    (net (code "376") (name "unconnected-(USBC1-SBU1-PadA8)") (class "Default")
      (node (ref "USBC1") (pin "A8") (pinfunction "SBU1_A8") (pintype "passive+no_connect"))
    )
    (net (code "377") (name "unconnected-(USBC1-SBU2-PadB8)") (class "Default")
      (node (ref "USBC1") (pin "B8") (pinfunction "SBU2_B8") (pintype "passive+no_connect"))
    )
    (net (code "378") (name "unconnected-(X1-EN{slash}NC-Pad1)") (class "Default")
      (node (ref "X1") (pin "1") (pinfunction "EN/NC_1") (pintype "passive+no_connect"))
    )
  )
)
